# whitherbone.net
KiCad netlist of a schematic drawn in EAGLE
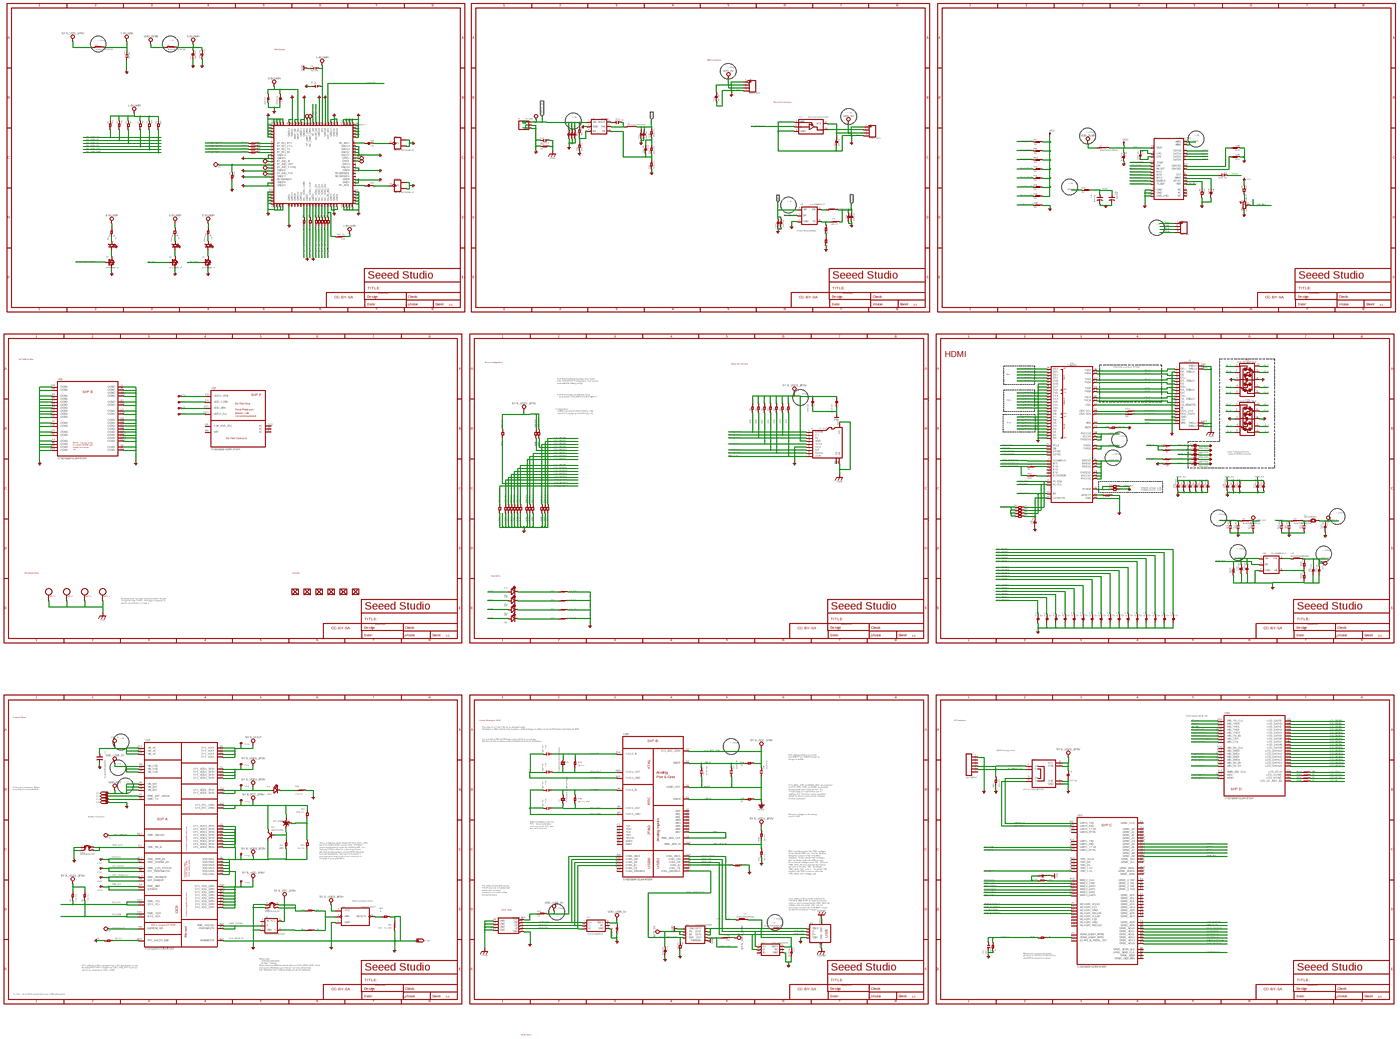
[diagram p0: schematic, sheet 1, overview]
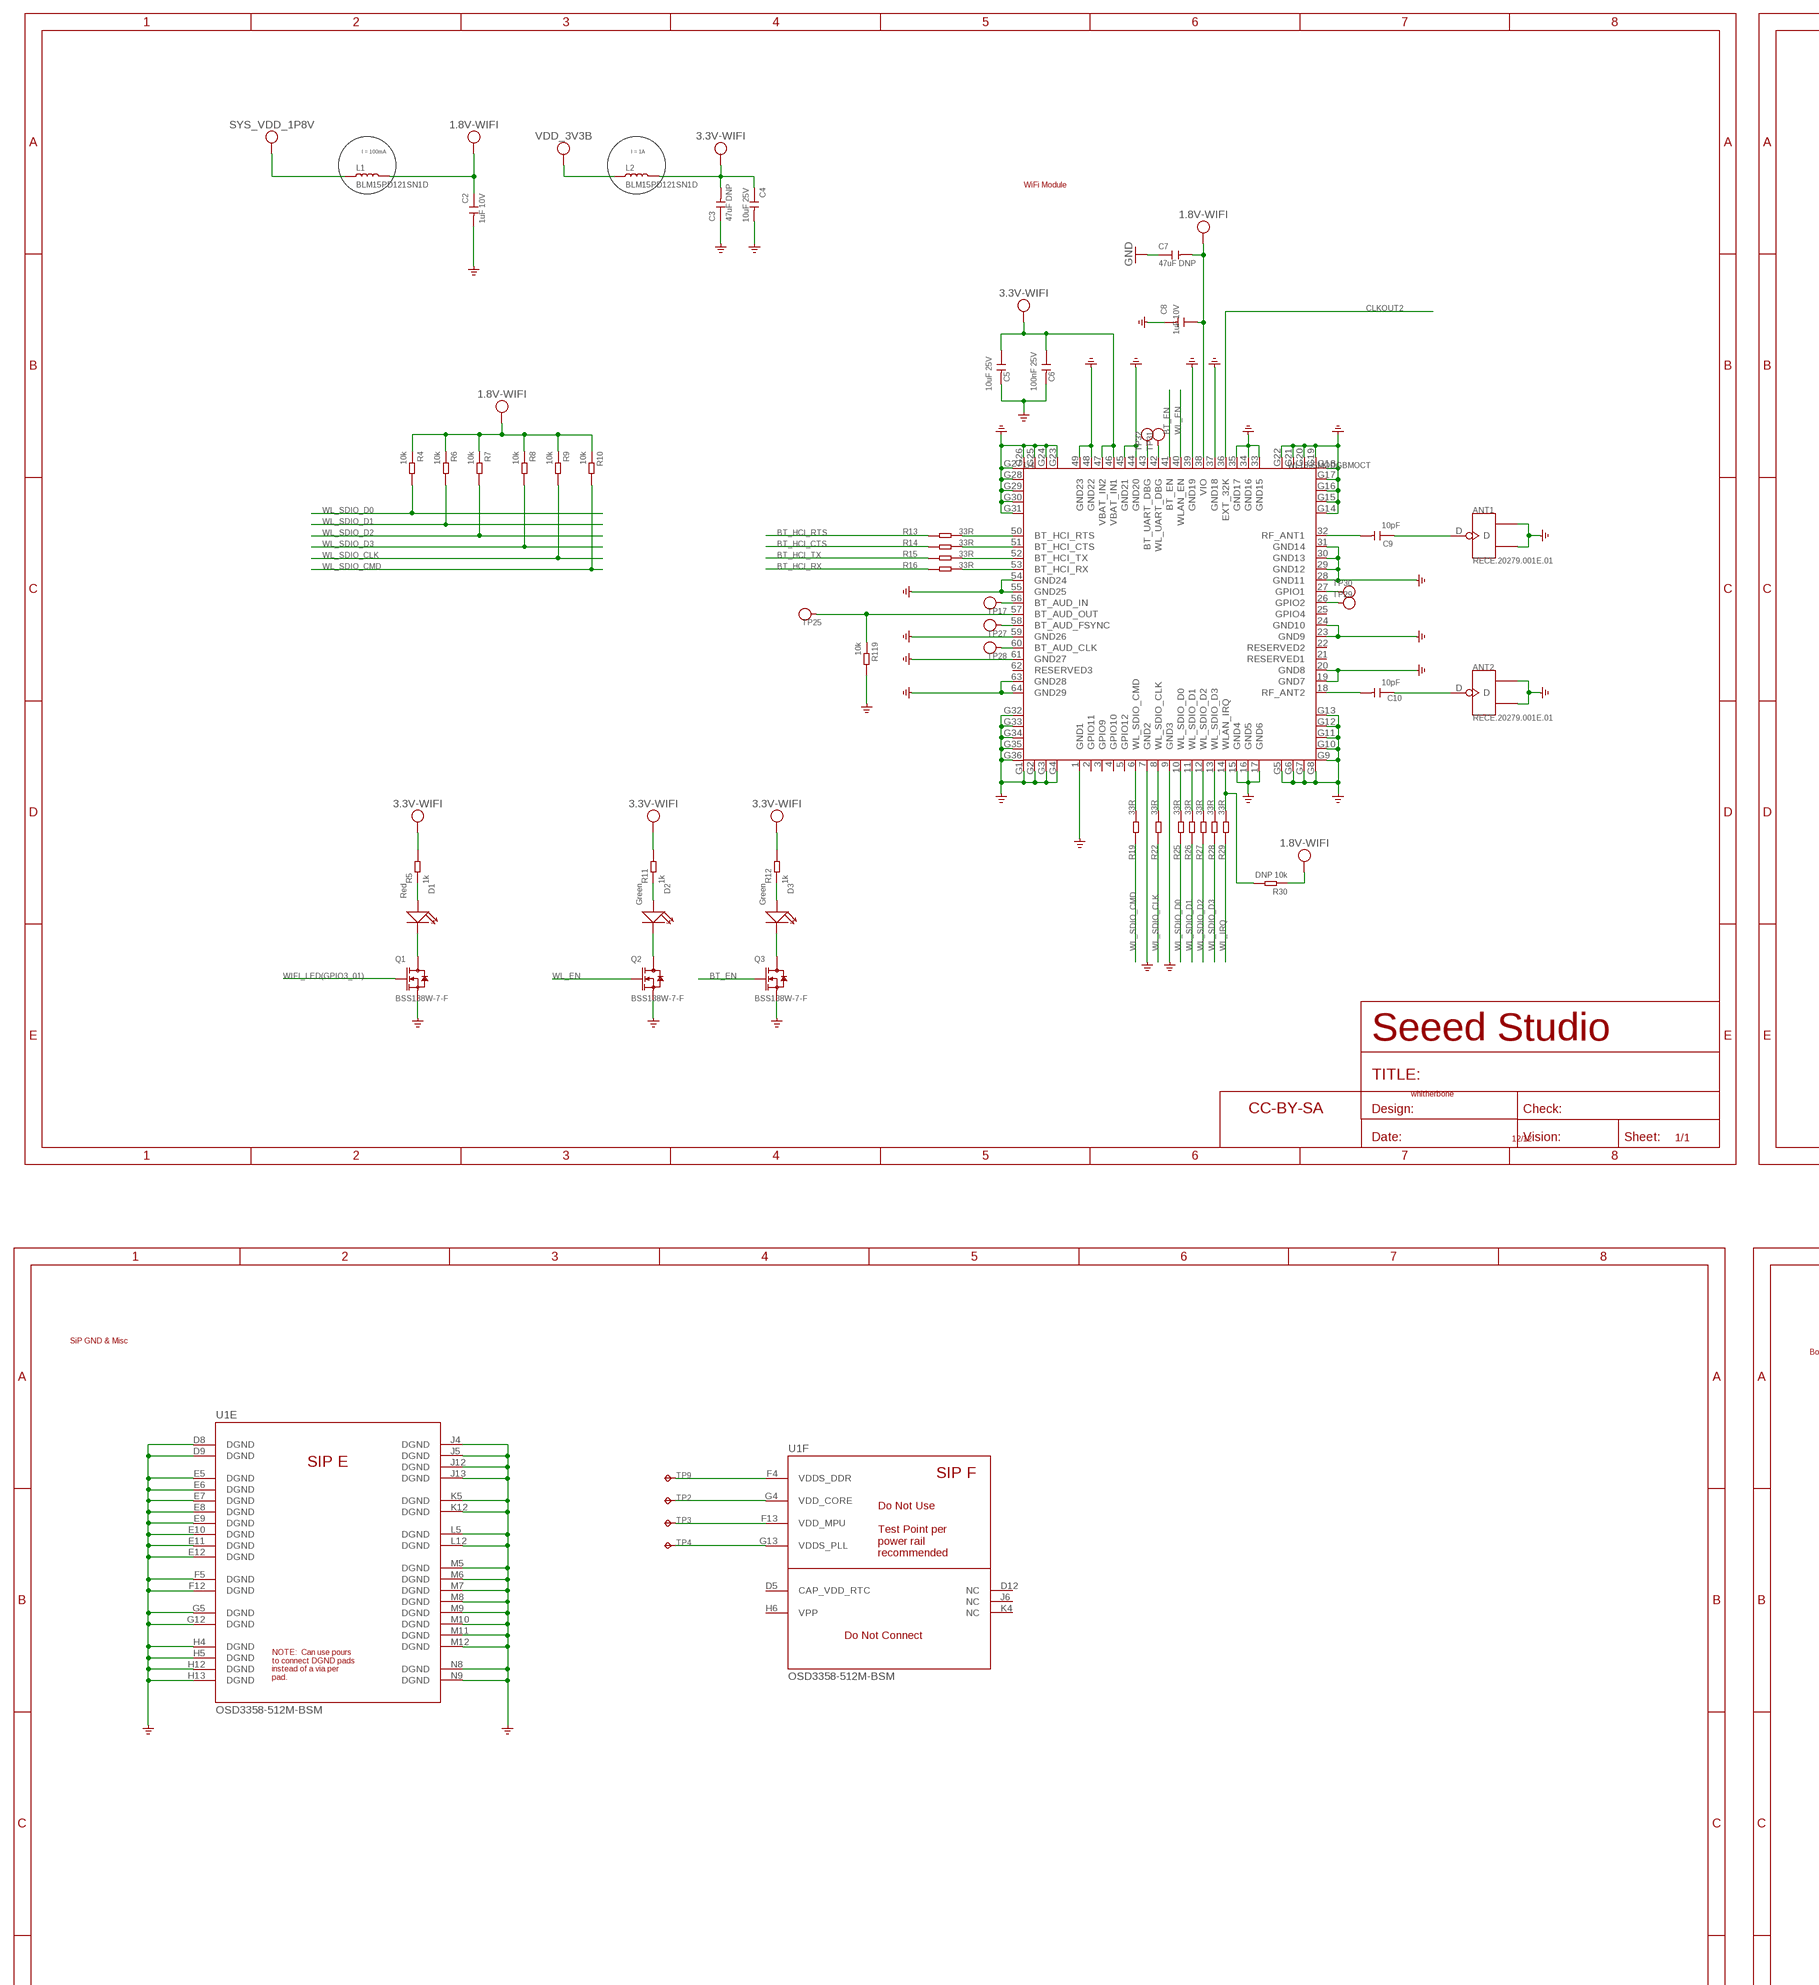
[diagram p1: schematic, sheet 1, part 1 of 8]
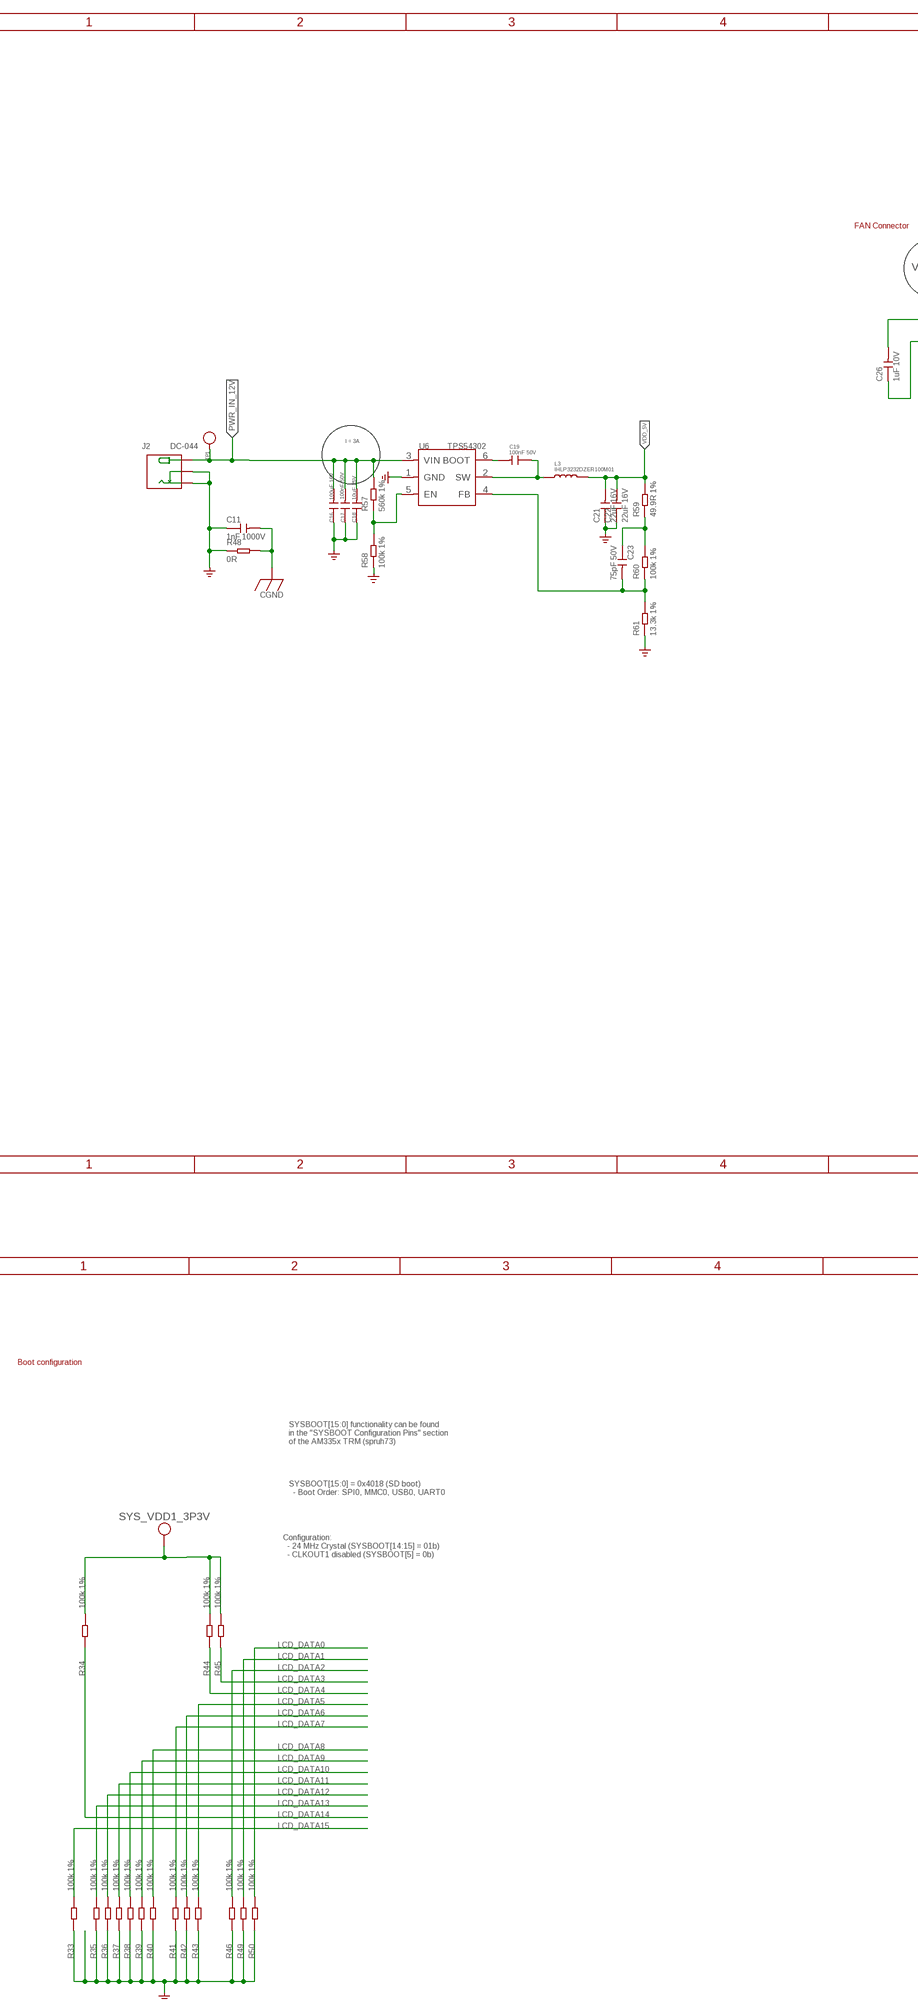
[diagram p2: schematic, sheet 1, part 2 of 8]
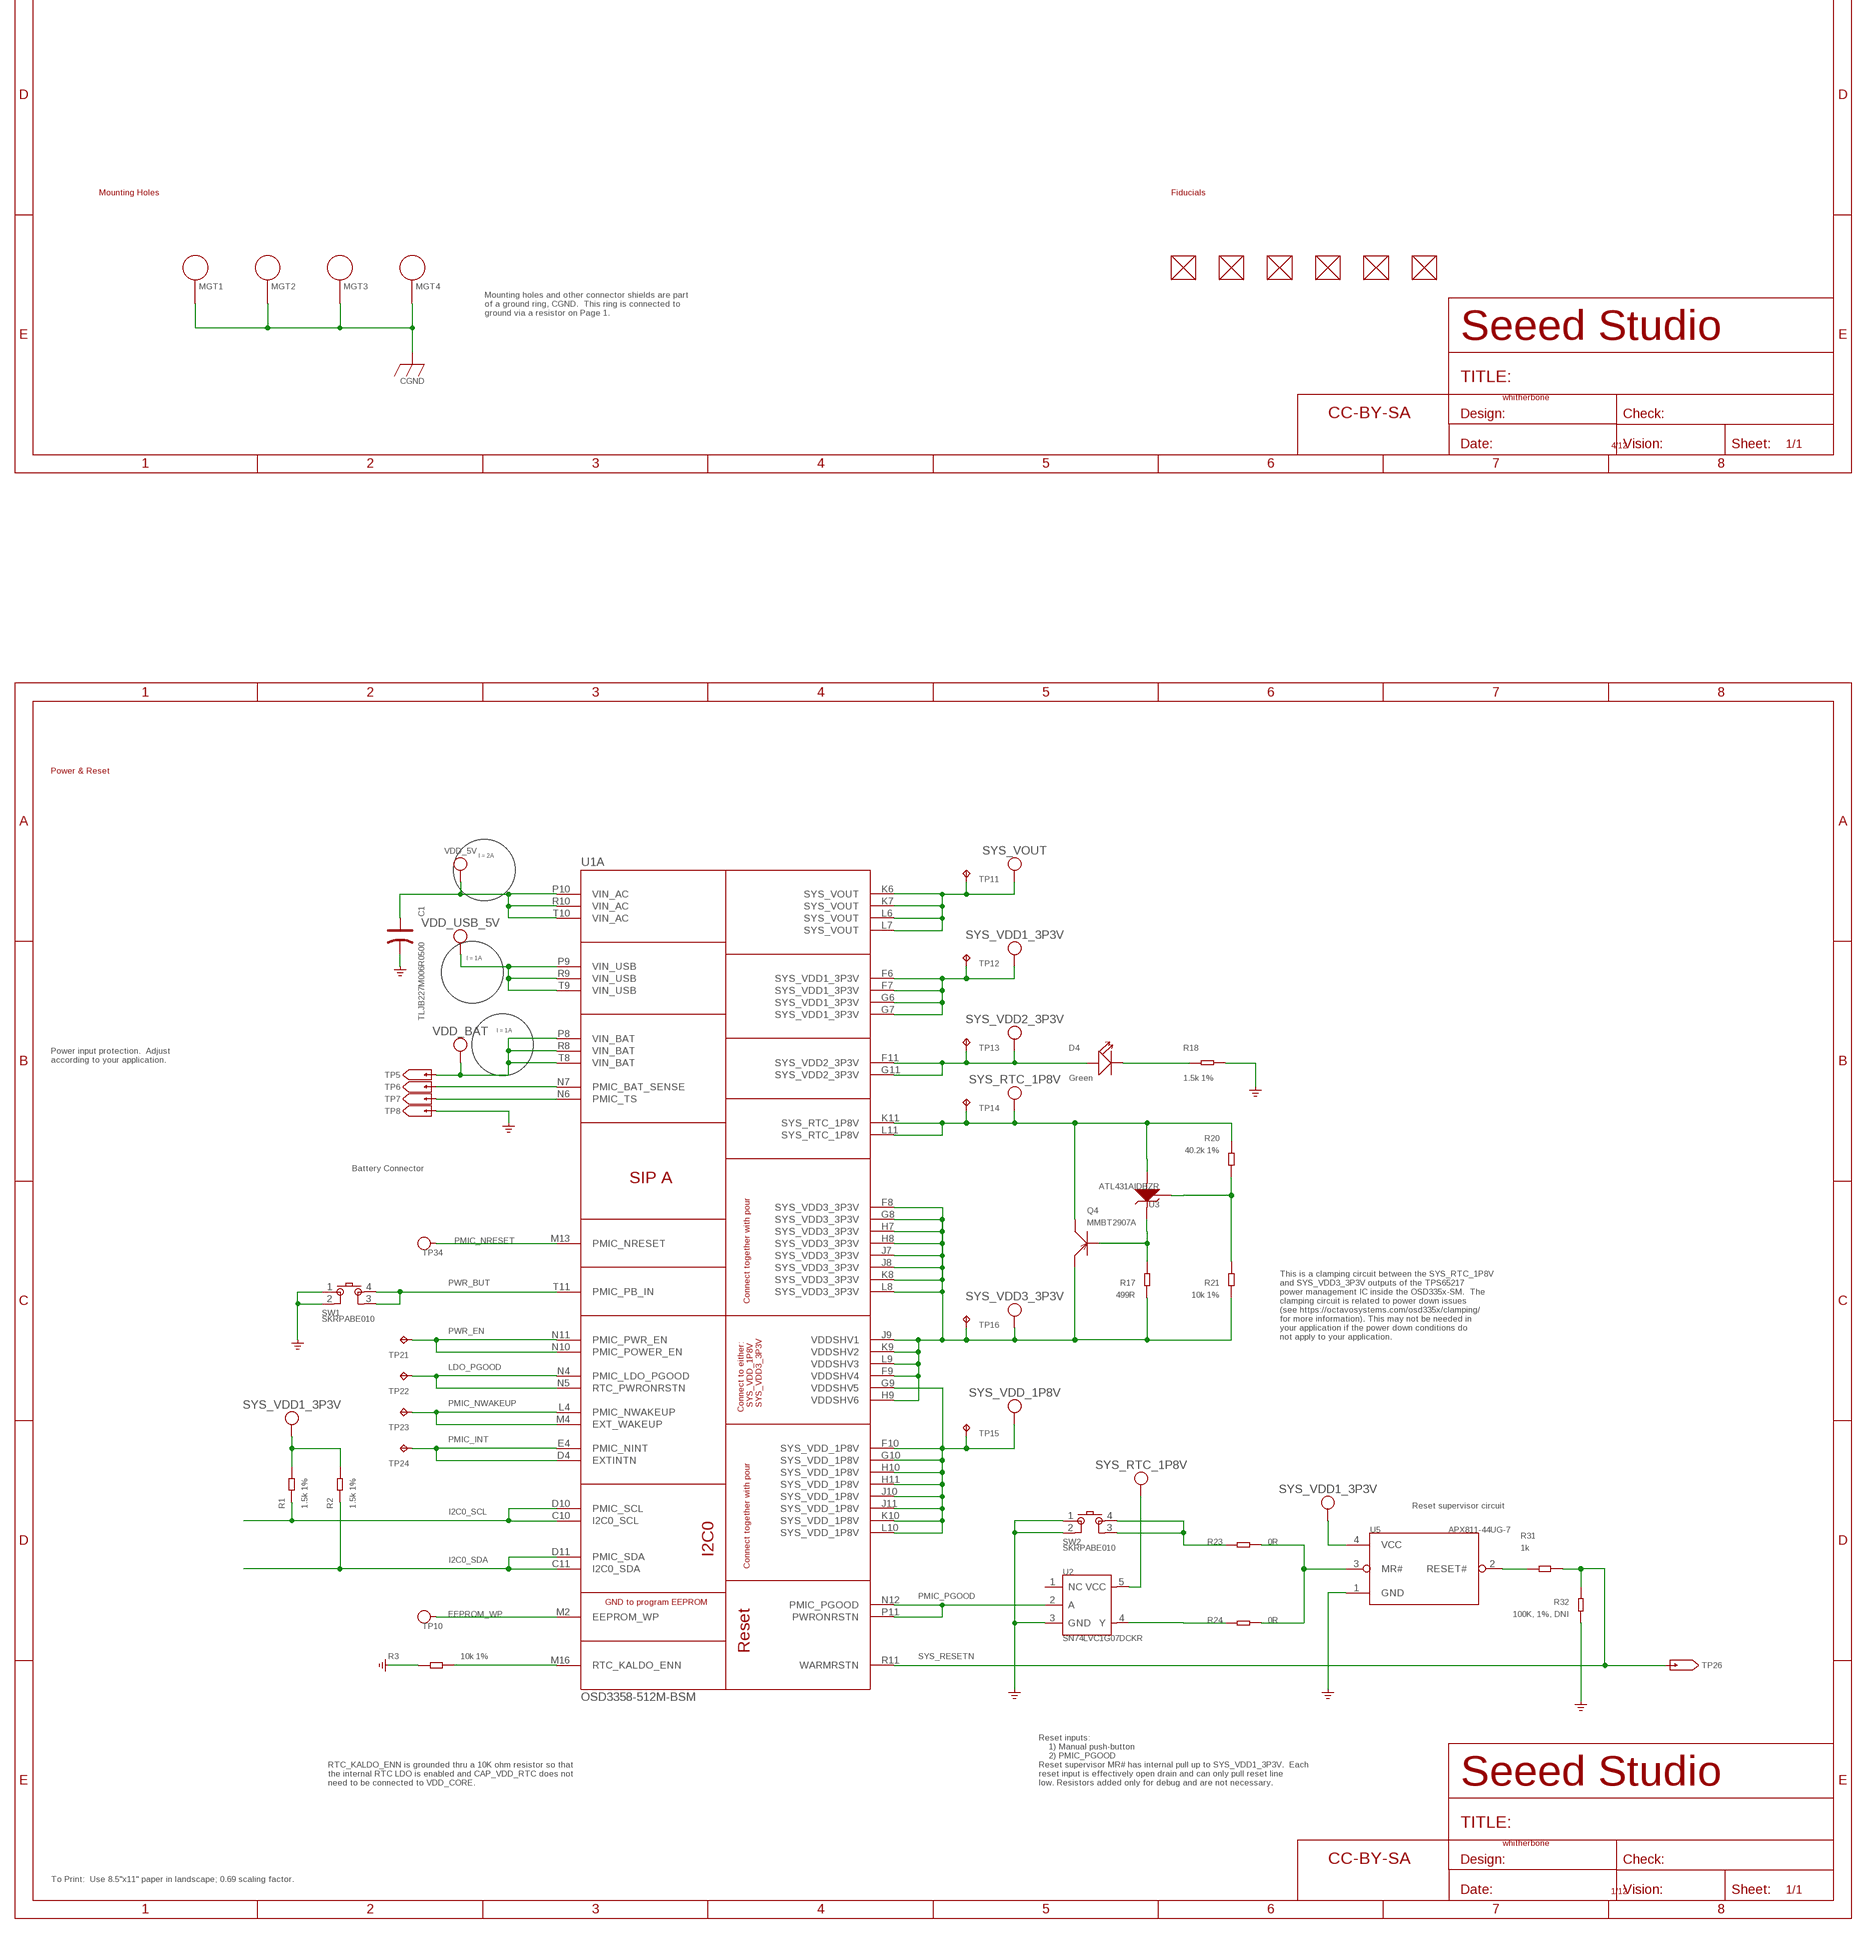
[diagram p3: schematic, sheet 1, part 3 of 8]
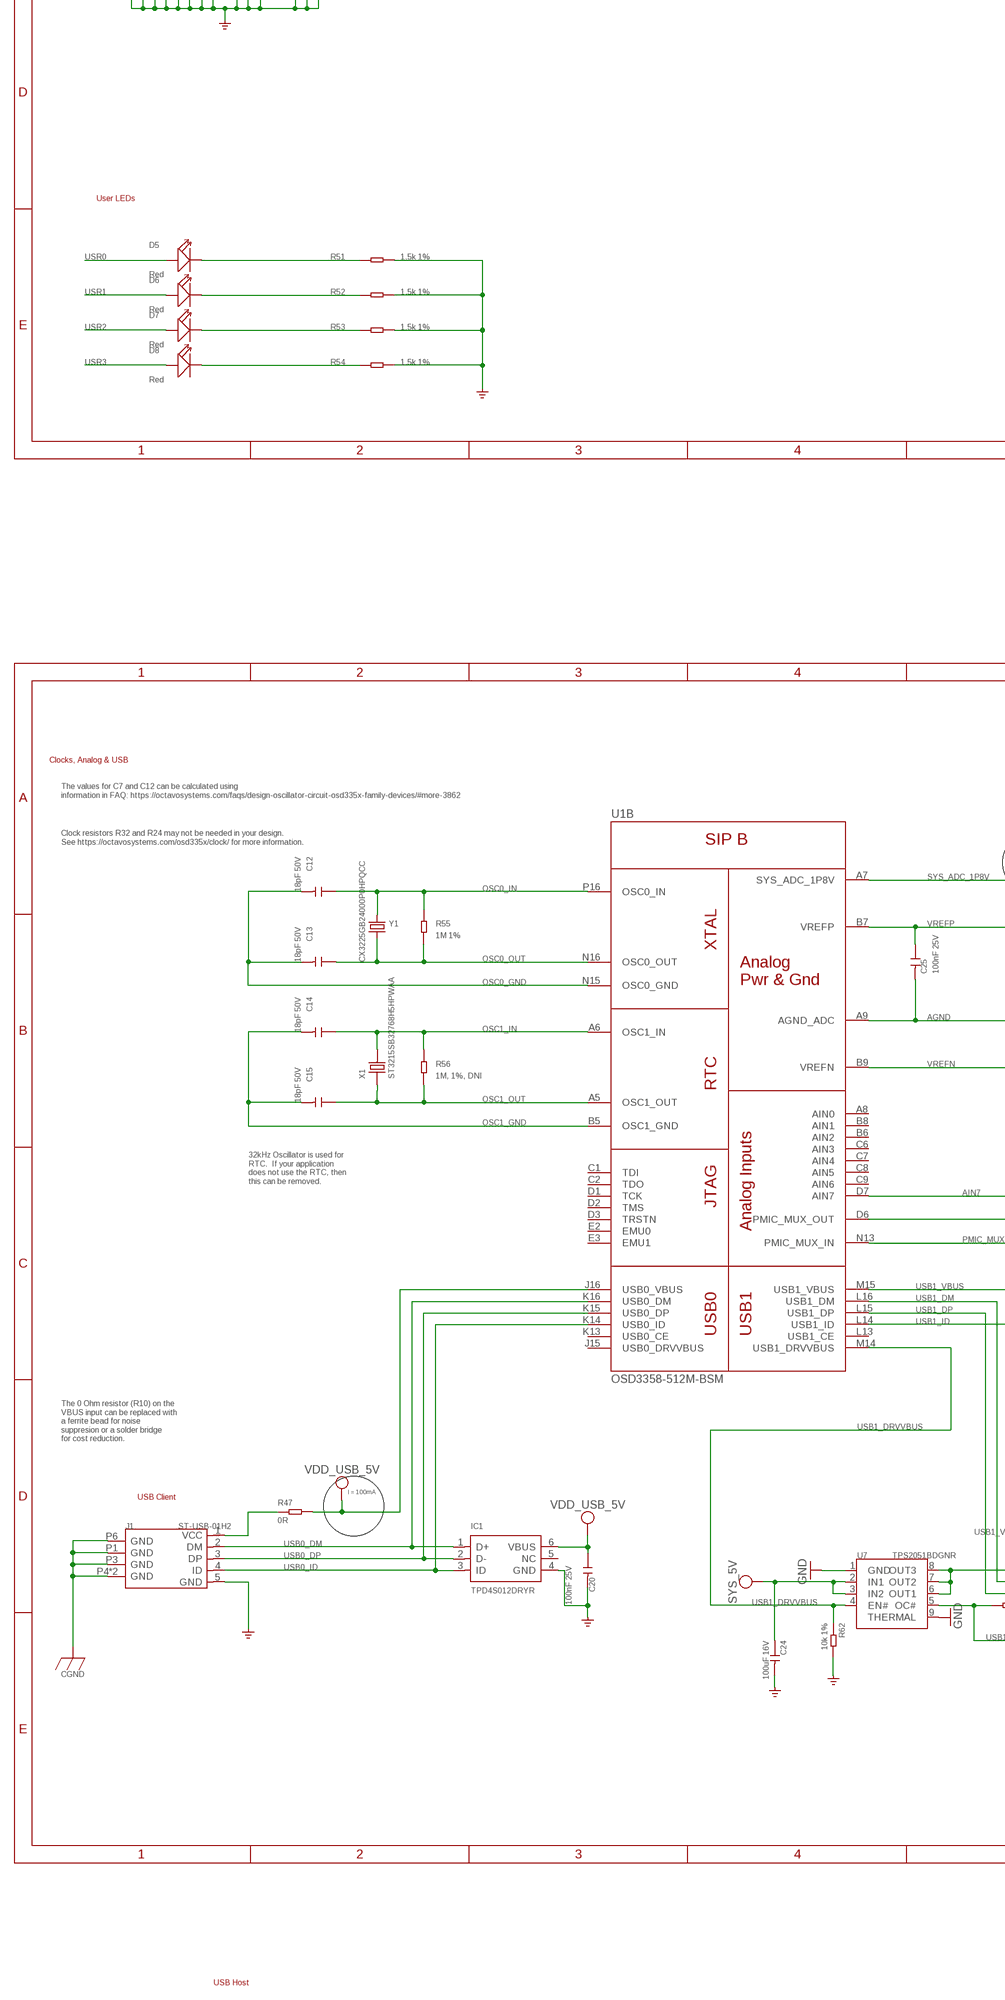
[diagram p4: schematic, sheet 1, part 4 of 8]
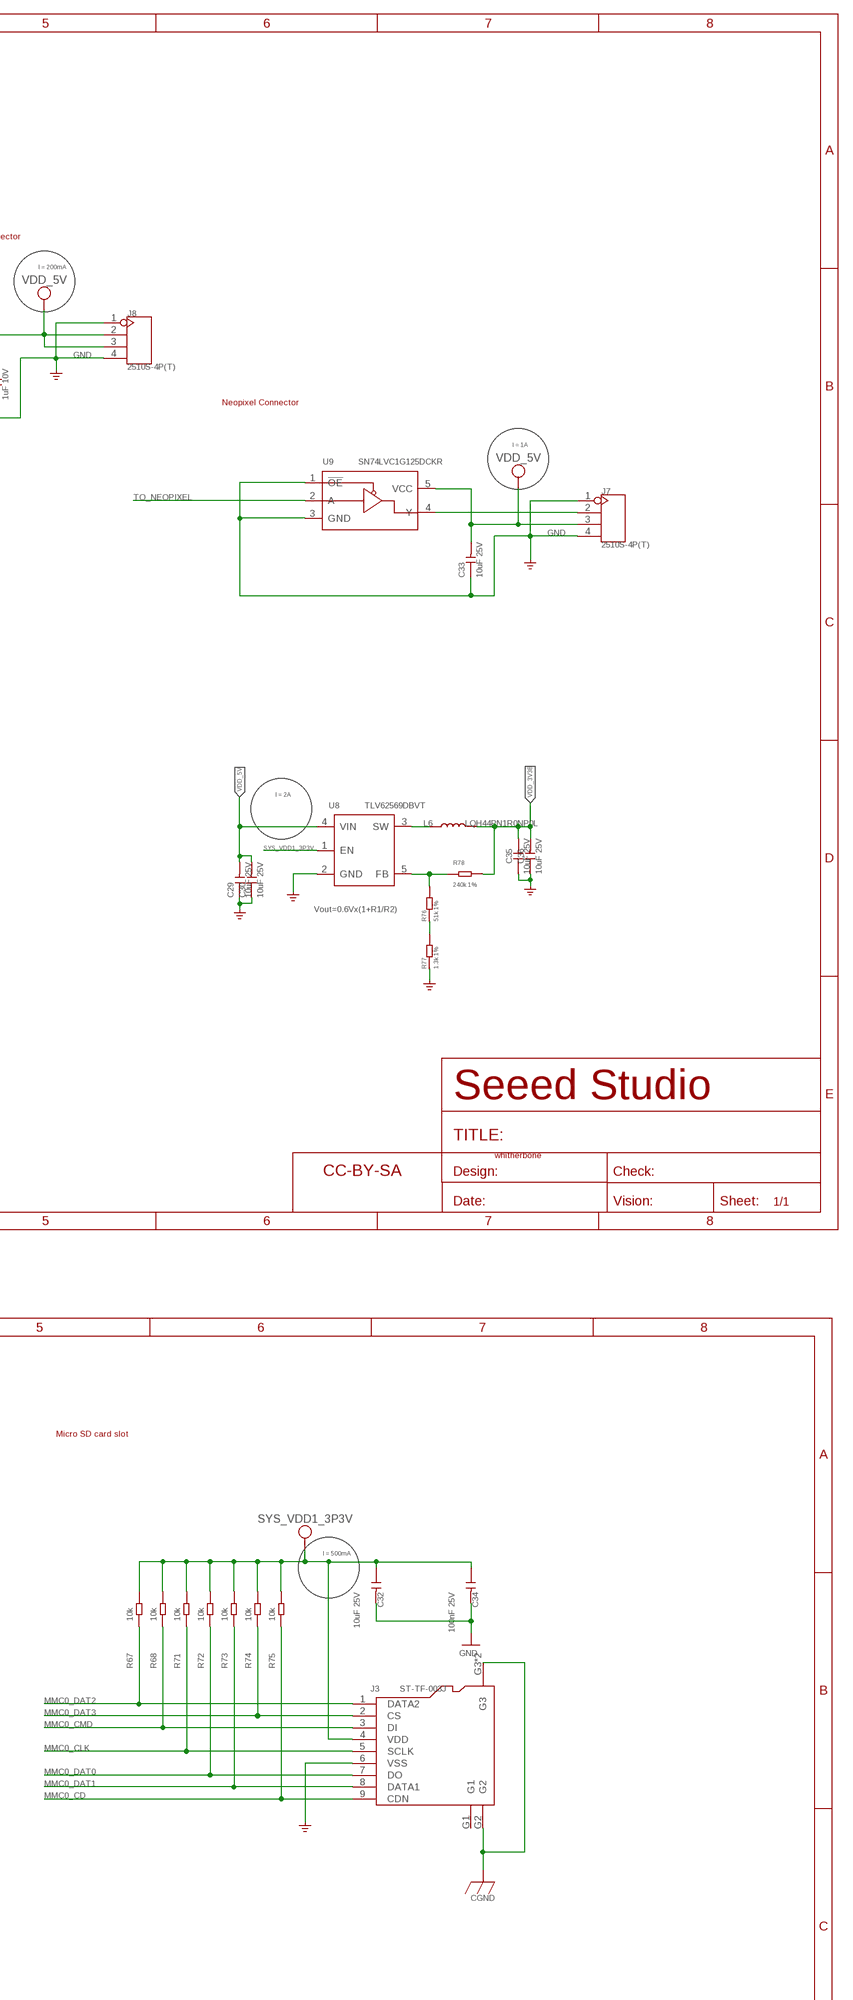
[diagram p5: schematic, sheet 1, part 5 of 8]
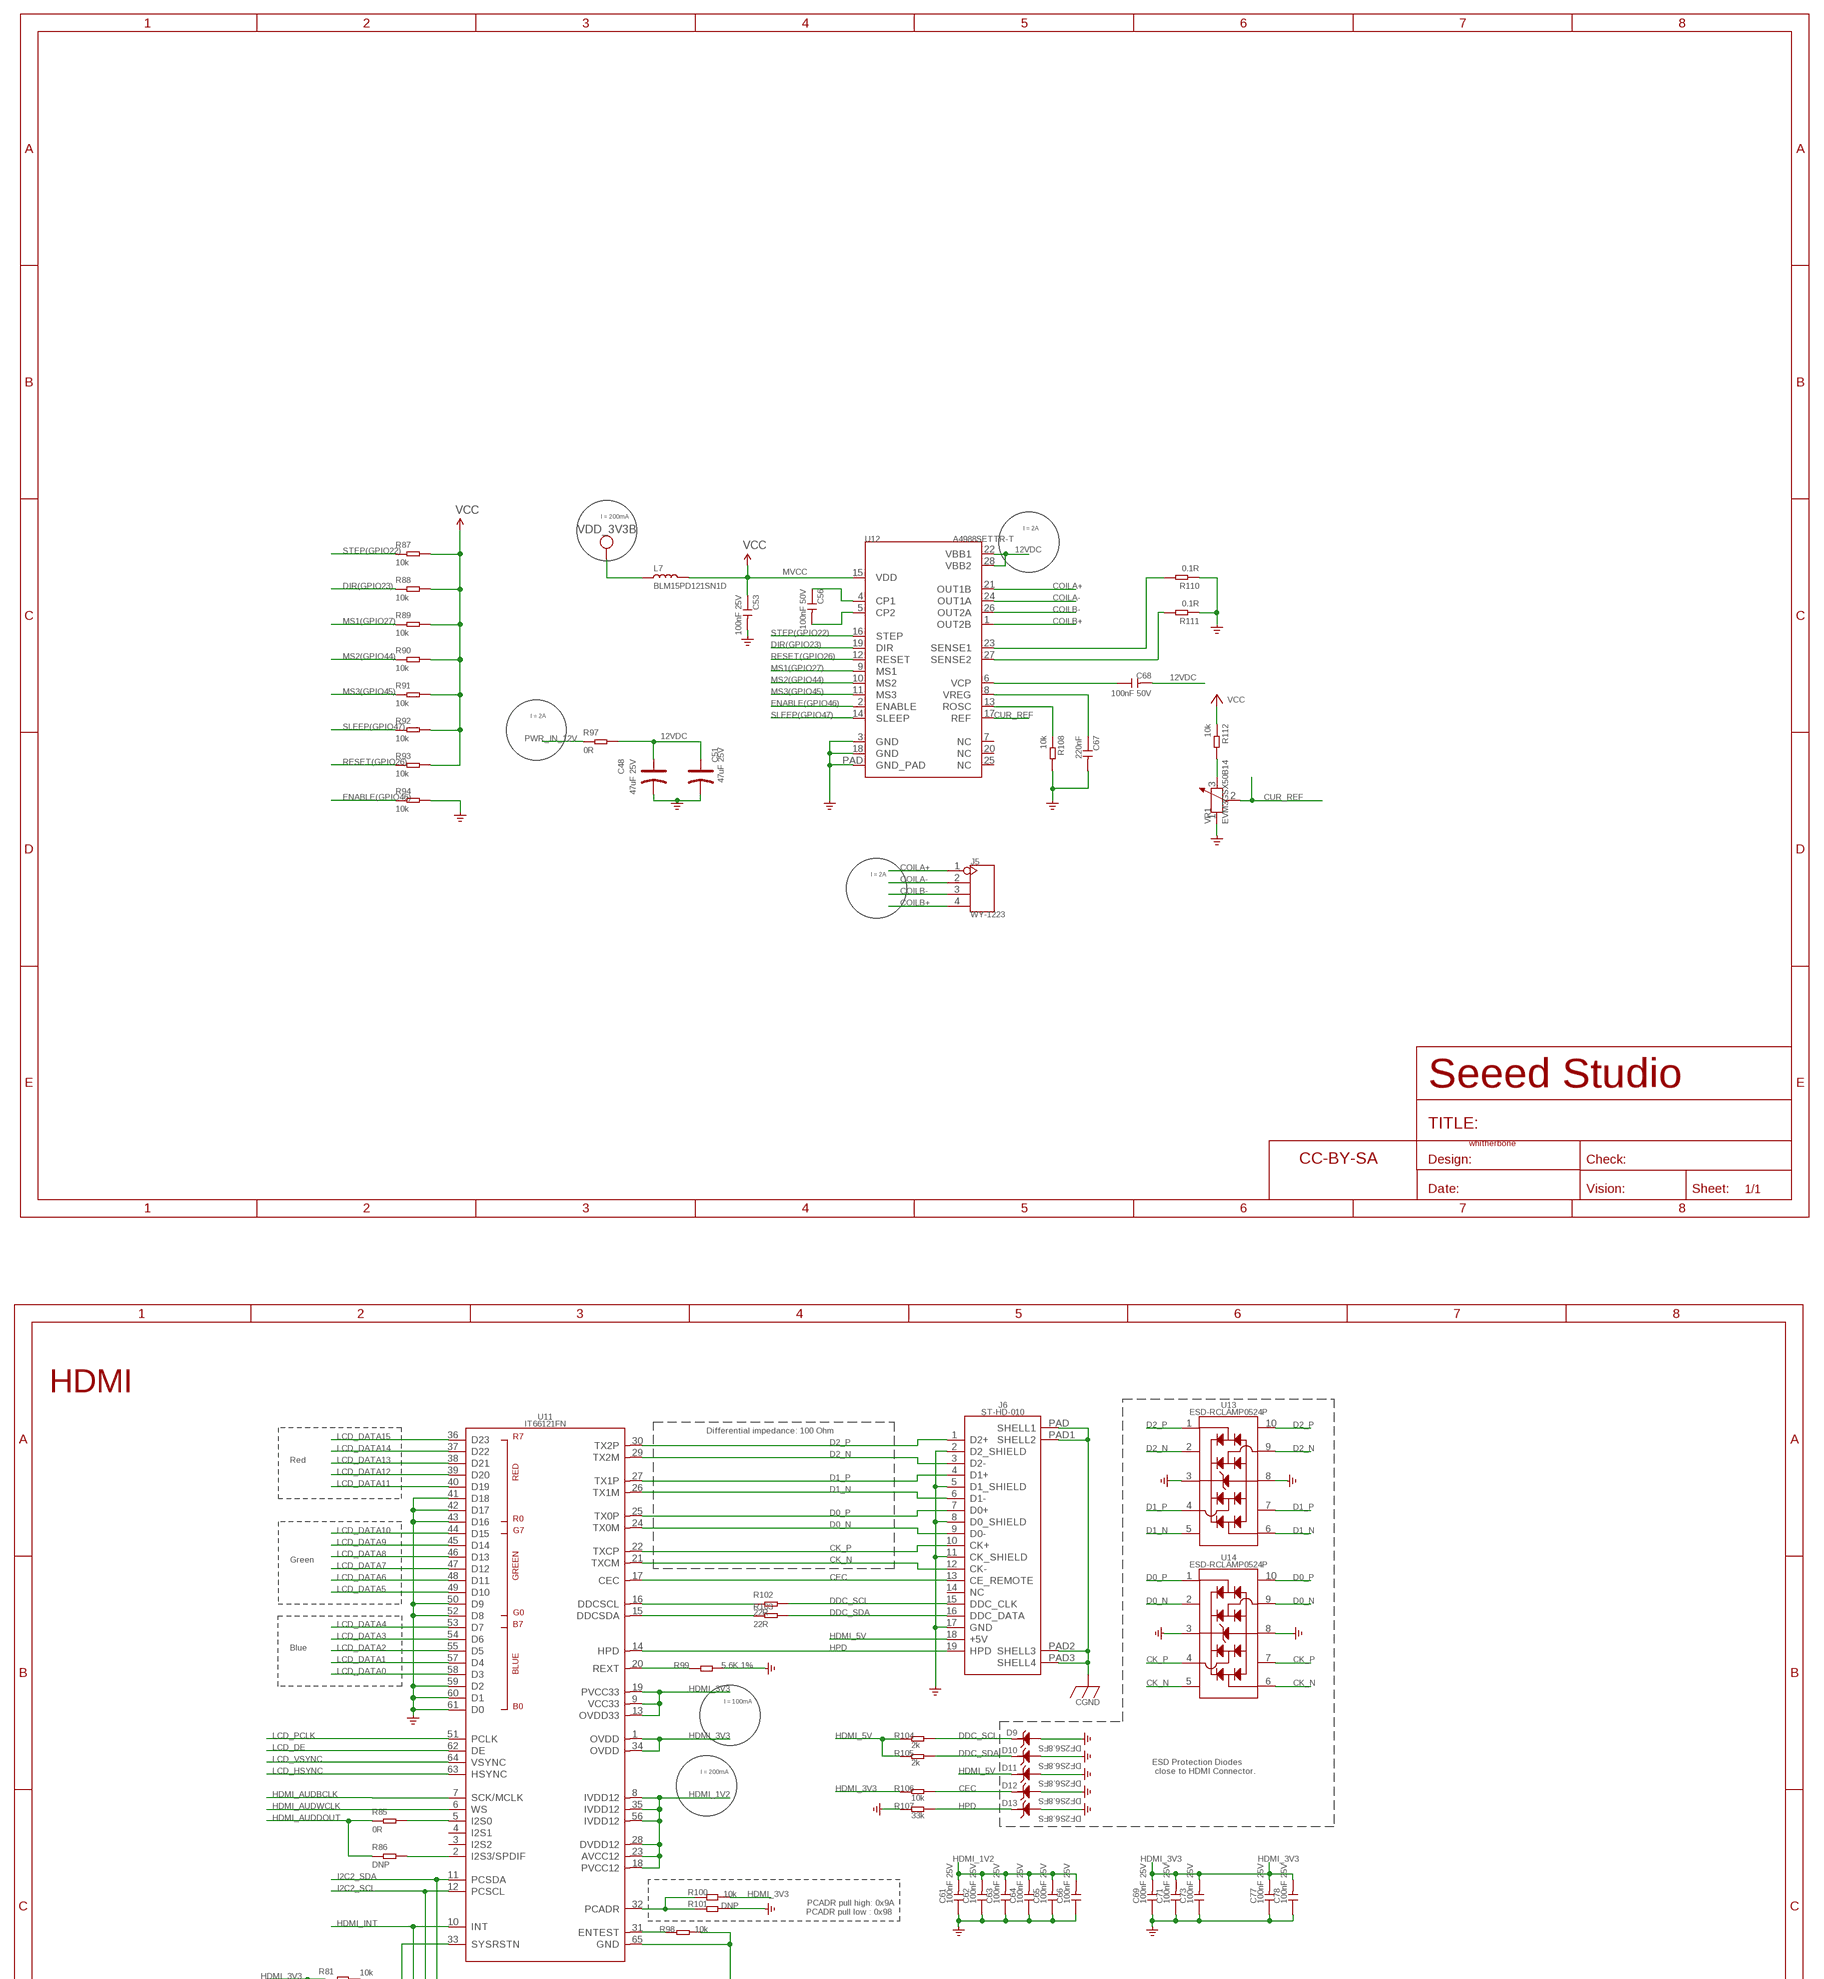
[diagram p6: schematic, sheet 1, part 6 of 8]
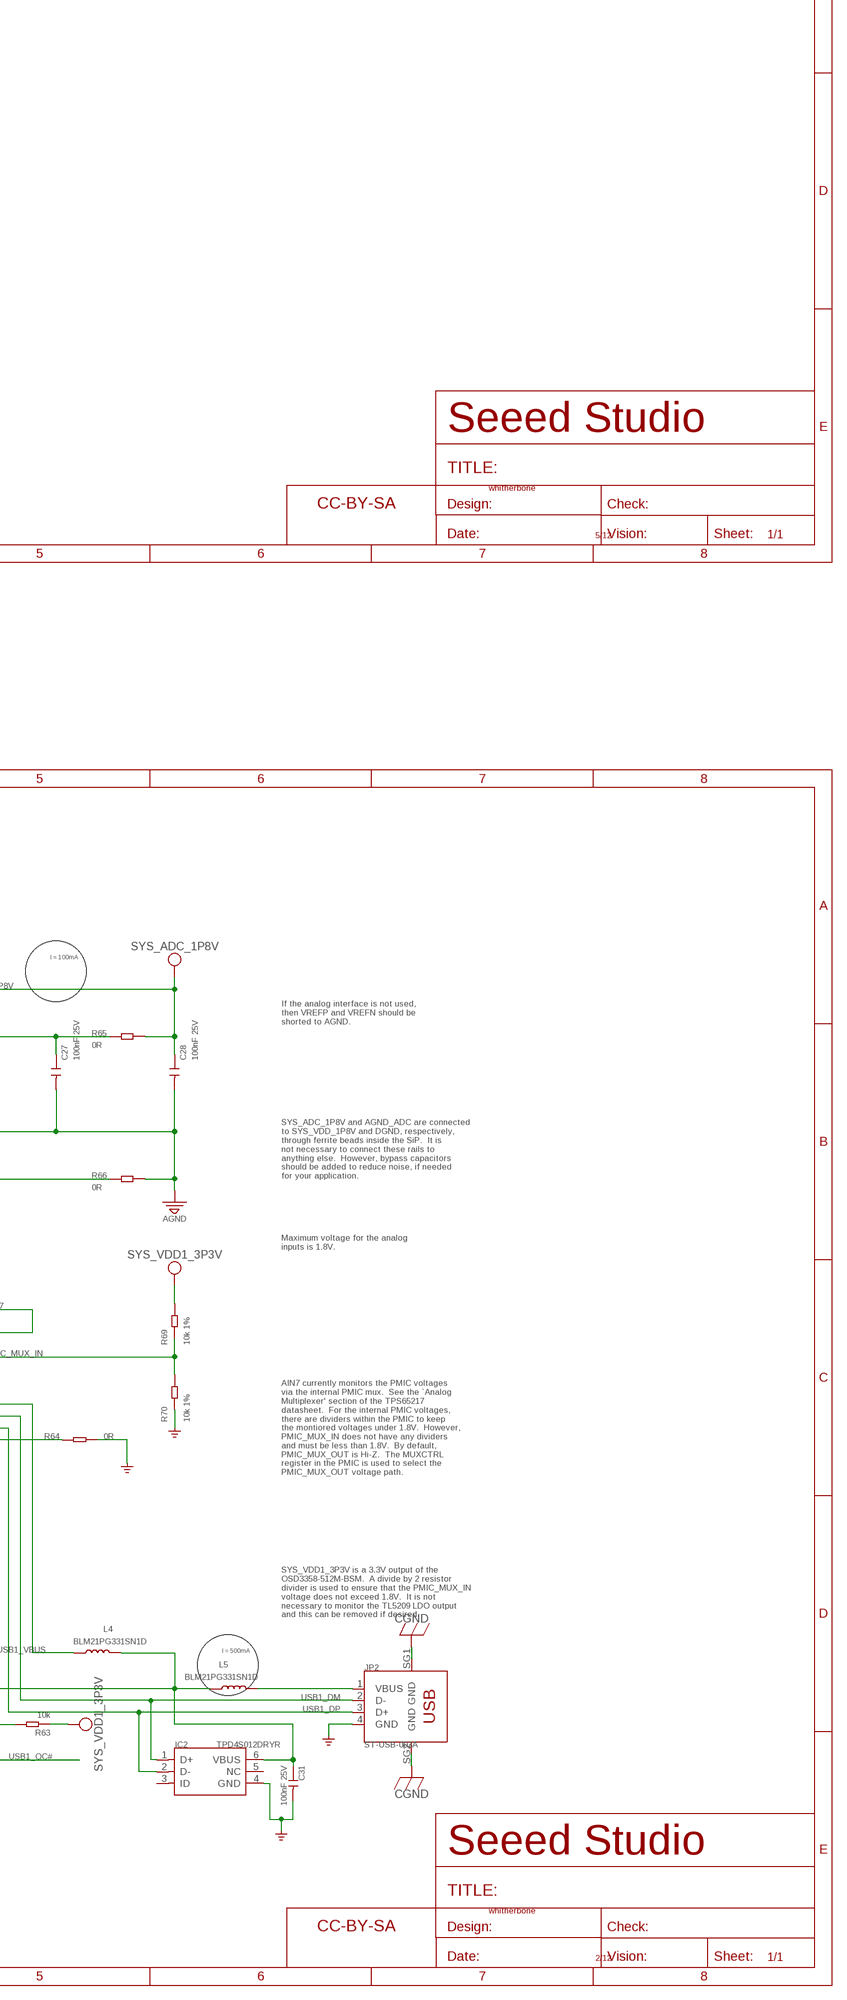
[diagram p7: schematic, sheet 1, part 7 of 8]
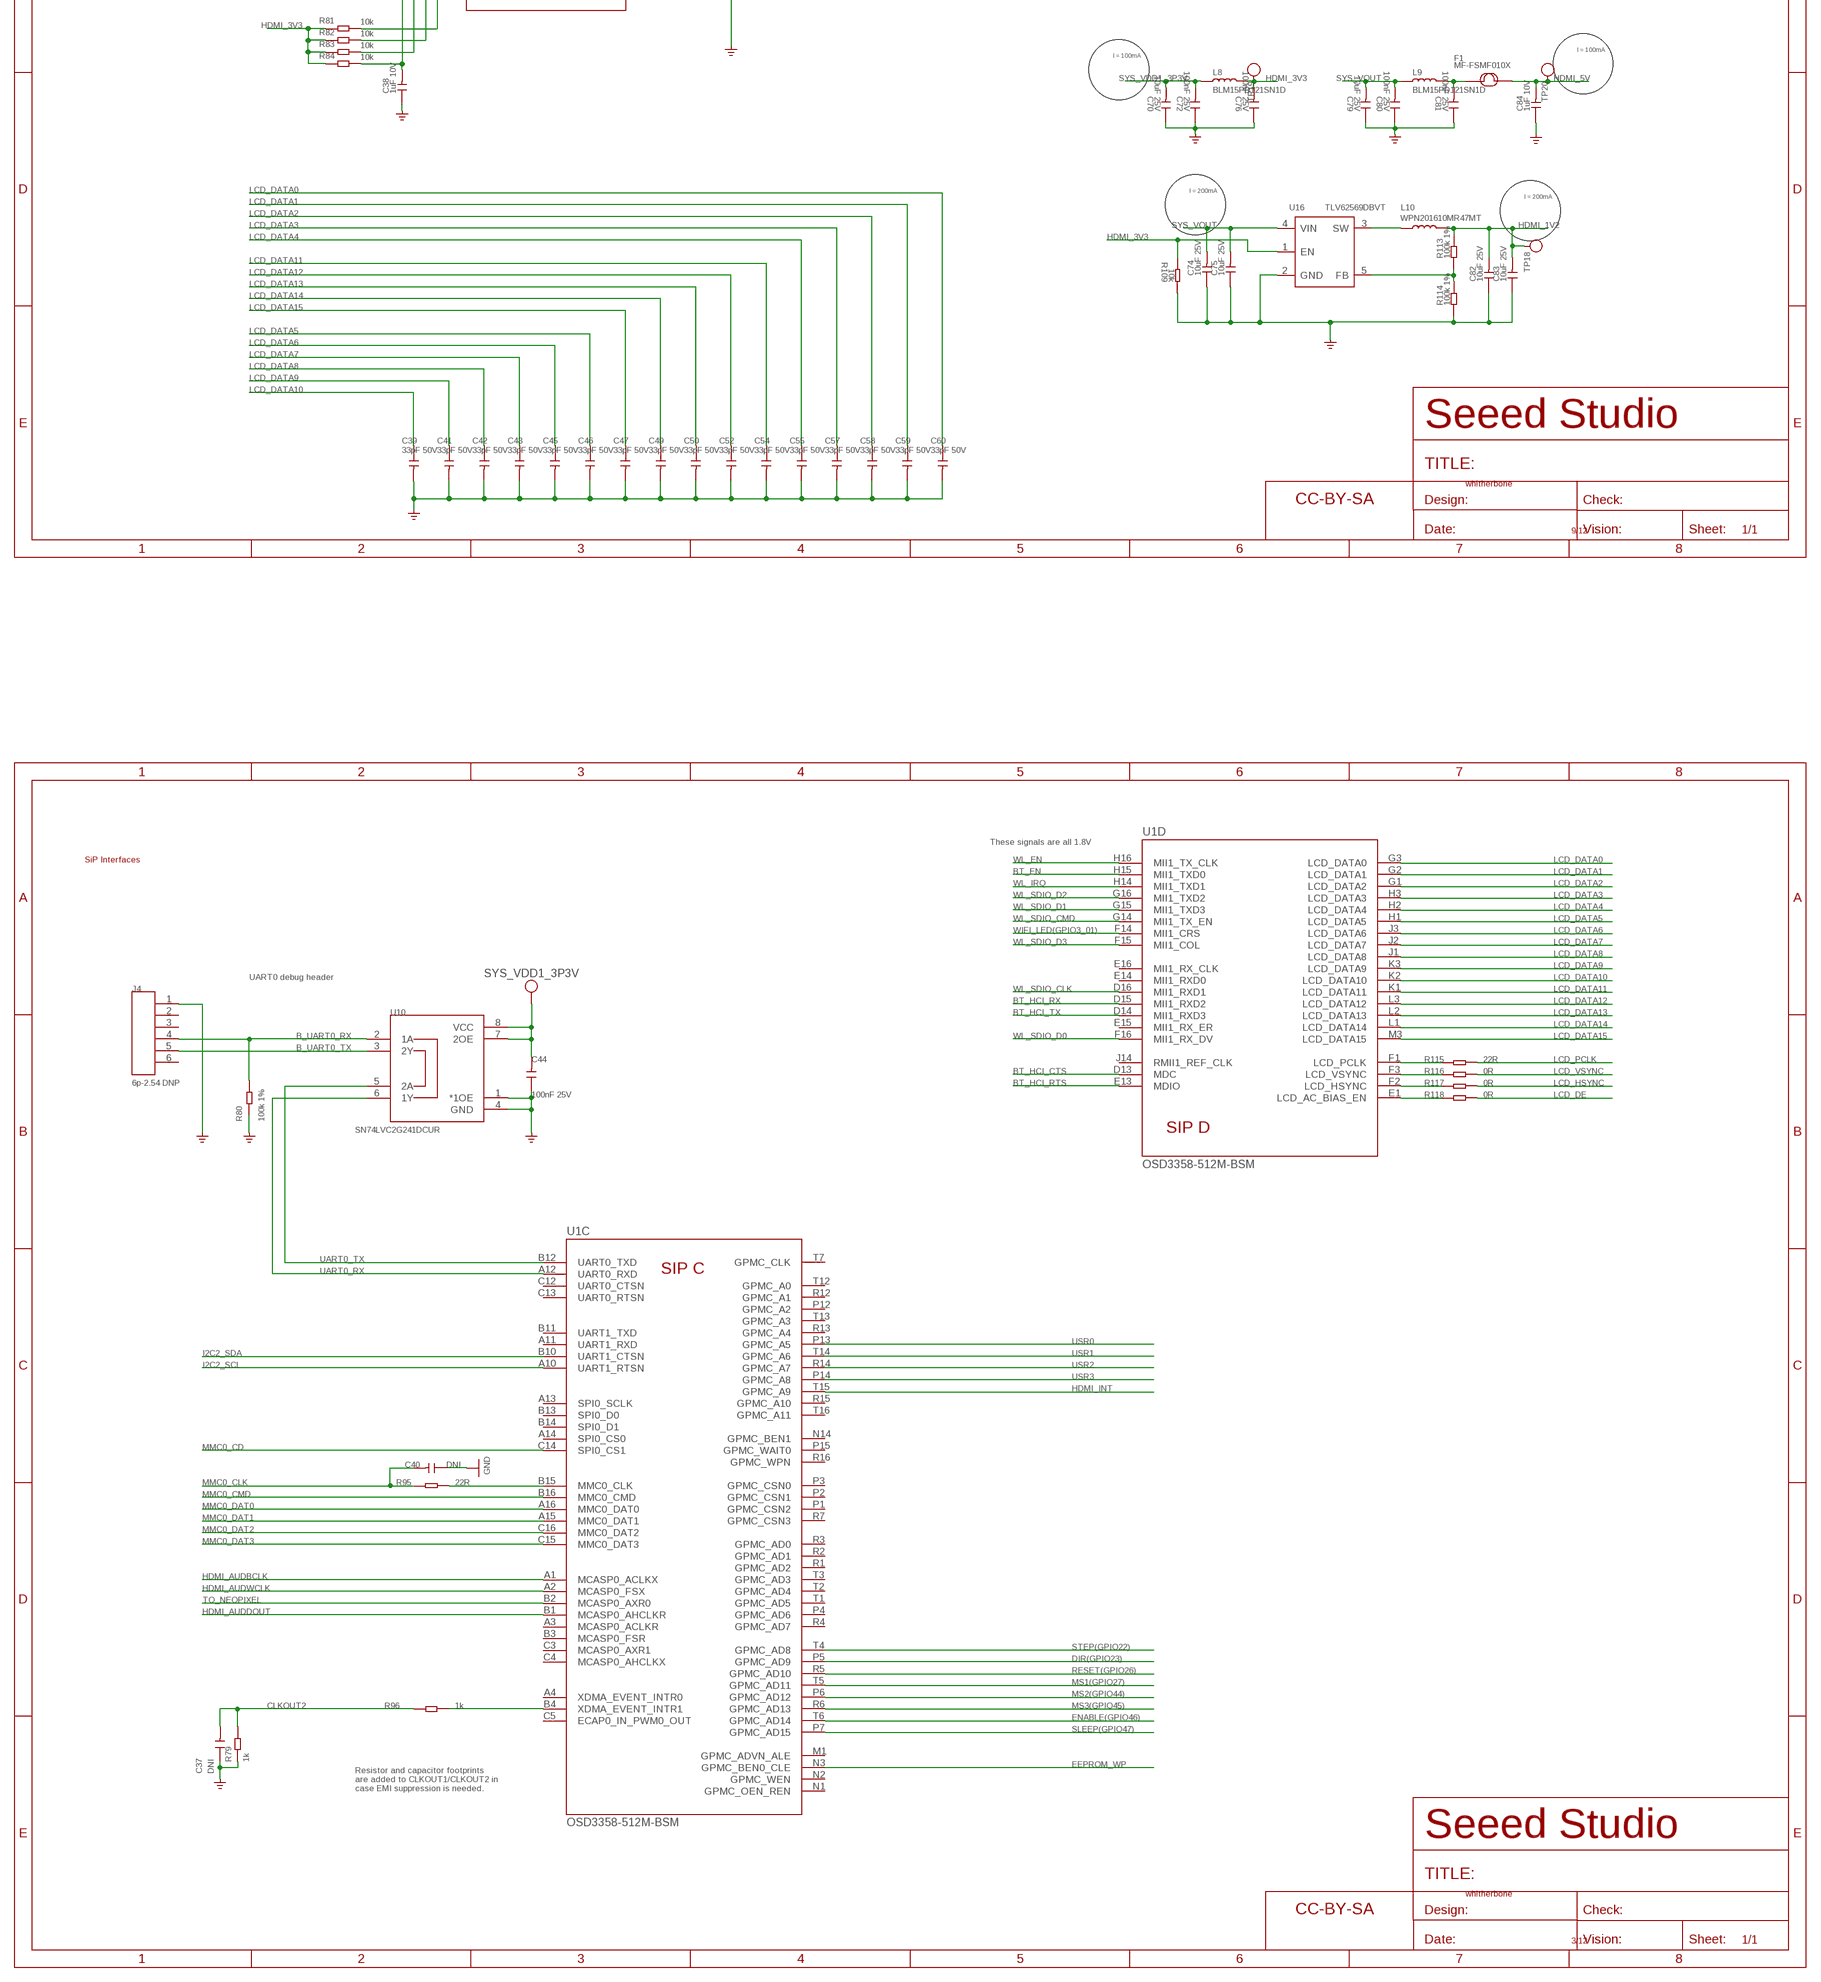
[diagram p8: schematic, sheet 1, part 8 of 8]

(export (version "E")
  (design (tool "Eeschema 10.0.6"))
  (components
    (comp (ref "ANT1")
      (value "RECE.20279.001E.01")
      (footprint "eagle-import:U-FL3P-SMD-2.6X2.6X1.0MM")
      (libsource (lib "eagle-import") (part "ANTENNA-U-FL-2.6X2.6"))
    )
    (comp (ref "ANT2")
      (value "RECE.20279.001E.01")
      (footprint "eagle-import:U-FL3P-SMD-2.6X2.6X1.0MM")
      (libsource (lib "eagle-import") (part "ANTENNA-U-FL-2.6X2.6"))
    )
    (comp (ref "C1")
      (value "TLJB227M006R0500")
      (footprint "eagle-import:AVX-B")
      (libsource (lib "eagle-import") (part "CAP-POLAR-AVX-B"))
    )
    (comp (ref "C2")
      (value "1uF 10V")
      (footprint "eagle-import:C0402")
      (libsource (lib "eagle-import") (part "CAP-0402"))
    )
    (comp (ref "C3")
      (value "47uF DNP")
      (footprint "eagle-import:C1206")
      (libsource (lib "eagle-import") (part "CAP-1206"))
    )
    (comp (ref "C4")
      (value "10uF 25V")
      (footprint "eagle-import:C0805")
      (libsource (lib "eagle-import") (part "CAP-0805"))
    )
    (comp (ref "C5")
      (value "10uF 25V")
      (footprint "eagle-import:C0805")
      (libsource (lib "eagle-import") (part "CAP-0805"))
    )
    (comp (ref "C6")
      (value "100nF 25V")
      (footprint "eagle-import:C0402")
      (libsource (lib "eagle-import") (part "CAP-0402"))
    )
    (comp (ref "C7")
      (value "47uF DNP")
      (footprint "eagle-import:C1206")
      (libsource (lib "eagle-import") (part "CAP-1206"))
    )
    (comp (ref "C8")
      (value "1uF 10V")
      (footprint "eagle-import:C0402")
      (libsource (lib "eagle-import") (part "CAP-0402"))
    )
    (comp (ref "C9")
      (value "10pF")
      (footprint "eagle-import:C0402")
      (libsource (lib "eagle-import") (part "CAP-0402"))
    )
    (comp (ref "C10")
      (value "10pF")
      (footprint "eagle-import:C0402")
      (libsource (lib "eagle-import") (part "CAP-0402"))
    )
    (comp (ref "C11")
      (value "1nF 1000V")
      (footprint "eagle-import:C1206")
      (libsource (lib "eagle-import") (part "CAP-1206"))
    )
    (comp (ref "C12")
      (value "18pF 50V")
      (footprint "eagle-import:C0402")
      (libsource (lib "eagle-import") (part "CAP-0402"))
    )
    (comp (ref "C13")
      (value "18pF 50V")
      (footprint "eagle-import:C0402")
      (libsource (lib "eagle-import") (part "CAP-0402"))
    )
    (comp (ref "C14")
      (value "18pF 50V")
      (footprint "eagle-import:C0402")
      (libsource (lib "eagle-import") (part "CAP-0402"))
    )
    (comp (ref "C15")
      (value "18pF 50V")
      (footprint "eagle-import:C0402")
      (libsource (lib "eagle-import") (part "CAP-0402"))
    )
    (comp (ref "C16")
      (value "100uF 16V")
      (footprint "eagle-import:C1210")
      (libsource (lib "eagle-import") (part "CAP-1210"))
    )
    (comp (ref "C17")
      (value "100nF 50V")
      (footprint "eagle-import:C0805")
      (libsource (lib "eagle-import") (part "CAP-0805"))
    )
    (comp (ref "C18")
      (value "10uF 25V")
      (footprint "eagle-import:C0805")
      (libsource (lib "eagle-import") (part "CAP-0805"))
    )
    (comp (ref "C19")
      (value "100nF 50V")
      (footprint "eagle-import:C0805")
      (libsource (lib "eagle-import") (part "CAP-0805"))
    )
    (comp (ref "C20")
      (value "100nF 25V")
      (footprint "eagle-import:C0402")
      (libsource (lib "eagle-import") (part "CAP-0402"))
    )
    (comp (ref "C21")
      (value "22uF 16V")
      (footprint "eagle-import:C1206")
      (libsource (lib "eagle-import") (part "CAP-1206"))
    )
    (comp (ref "C22")
      (value "22uF 16V")
      (footprint "eagle-import:C1206")
      (libsource (lib "eagle-import") (part "CAP-1206"))
    )
    (comp (ref "C23")
      (value "75pF 50V")
      (footprint "eagle-import:C0402")
      (libsource (lib "eagle-import") (part "CAP-0402"))
    )
    (comp (ref "C24")
      (value "100uF 16V")
      (footprint "eagle-import:C1210")
      (libsource (lib "eagle-import") (part "CAP-1210"))
    )
    (comp (ref "C25")
      (value "100nF 25V")
      (footprint "eagle-import:C0402")
      (libsource (lib "eagle-import") (part "CAP-0402"))
    )
    (comp (ref "C26")
      (value "1uF 10V")
      (footprint "eagle-import:C0402")
      (libsource (lib "eagle-import") (part "CAP-0402"))
    )
    (comp (ref "C27")
      (value "100nF 25V")
      (footprint "eagle-import:C0402")
      (libsource (lib "eagle-import") (part "CAP-0402"))
    )
    (comp (ref "C28")
      (value "100nF 25V")
      (footprint "eagle-import:C0402")
      (libsource (lib "eagle-import") (part "CAP-0402"))
    )
    (comp (ref "C29")
      (value "10uF 25V")
      (footprint "eagle-import:C0805")
      (libsource (lib "eagle-import") (part "CAP-0805"))
    )
    (comp (ref "C30")
      (value "10uF 25V")
      (footprint "eagle-import:C0805")
      (libsource (lib "eagle-import") (part "CAP-0805"))
    )
    (comp (ref "C31")
      (value "100nF 25V")
      (footprint "eagle-import:C0402")
      (libsource (lib "eagle-import") (part "CAP-0402"))
    )
    (comp (ref "C32")
      (value "10uF 25V")
      (footprint "eagle-import:C0805")
      (libsource (lib "eagle-import") (part "CAP-0805"))
    )
    (comp (ref "C33")
      (value "10uF 25V")
      (footprint "eagle-import:C0805")
      (libsource (lib "eagle-import") (part "CAP-0805"))
    )
    (comp (ref "C34")
      (value "100nF 25V")
      (footprint "eagle-import:C0402")
      (libsource (lib "eagle-import") (part "CAP-0402"))
    )
    (comp (ref "C35")
      (value "10uF 25V")
      (footprint "eagle-import:C0805")
      (libsource (lib "eagle-import") (part "CAP-0805"))
    )
    (comp (ref "C36")
      (value "10uF 25V")
      (footprint "eagle-import:C0805")
      (libsource (lib "eagle-import") (part "CAP-0805"))
    )
    (comp (ref "C37")
      (value "DNI")
      (footprint "eagle-import:C0402")
      (libsource (lib "eagle-import") (part "CAP-0402"))
    )
    (comp (ref "C38")
      (value "1uF 10V")
      (footprint "eagle-import:C0402")
      (libsource (lib "eagle-import") (part "CAP-0402"))
    )
    (comp (ref "C39")
      (value "33pF 50V")
      (footprint "eagle-import:C0402")
      (libsource (lib "eagle-import") (part "CAP-0402"))
    )
    (comp (ref "C40")
      (value "DNI")
      (footprint "eagle-import:C0402")
      (libsource (lib "eagle-import") (part "CAP-0402"))
    )
    (comp (ref "C41")
      (value "33pF 50V")
      (footprint "eagle-import:C0402")
      (libsource (lib "eagle-import") (part "CAP-0402"))
    )
    (comp (ref "C42")
      (value "33pF 50V")
      (footprint "eagle-import:C0402")
      (libsource (lib "eagle-import") (part "CAP-0402"))
    )
    (comp (ref "C43")
      (value "33pF 50V")
      (footprint "eagle-import:C0402")
      (libsource (lib "eagle-import") (part "CAP-0402"))
    )
    (comp (ref "C44")
      (value "100nF 25V")
      (footprint "eagle-import:C0402")
      (libsource (lib "eagle-import") (part "CAP-0402"))
    )
    (comp (ref "C45")
      (value "33pF 50V")
      (footprint "eagle-import:C0402")
      (libsource (lib "eagle-import") (part "CAP-0402"))
    )
    (comp (ref "C46")
      (value "33pF 50V")
      (footprint "eagle-import:C0402")
      (libsource (lib "eagle-import") (part "CAP-0402"))
    )
    (comp (ref "C47")
      (value "33pF 50V")
      (footprint "eagle-import:C0402")
      (libsource (lib "eagle-import") (part "CAP-0402"))
    )
    (comp (ref "C48")
      (value "47uF 25V")
      (footprint "eagle-import:ELECTRO-SMD-C-6MM")
      (libsource (lib "eagle-import") (part "CAP-POLAR-ELECTRO-C"))
    )
    (comp (ref "C49")
      (value "33pF 50V")
      (footprint "eagle-import:C0402")
      (libsource (lib "eagle-import") (part "CAP-0402"))
    )
    (comp (ref "C50")
      (value "33pF 50V")
      (footprint "eagle-import:C0402")
      (libsource (lib "eagle-import") (part "CAP-0402"))
    )
    (comp (ref "C51")
      (value "47uF 25V")
      (footprint "eagle-import:ELECTRO-SMD-C-6MM")
      (libsource (lib "eagle-import") (part "CAP-POLAR-ELECTRO-C"))
    )
    (comp (ref "C52")
      (value "33pF 50V")
      (footprint "eagle-import:C0402")
      (libsource (lib "eagle-import") (part "CAP-0402"))
    )
    (comp (ref "C53")
      (value "100nF 25V")
      (footprint "eagle-import:C0402")
      (libsource (lib "eagle-import") (part "CAP-0402"))
    )
    (comp (ref "C54")
      (value "33pF 50V")
      (footprint "eagle-import:C0402")
      (libsource (lib "eagle-import") (part "CAP-0402"))
    )
    (comp (ref "C55")
      (value "33pF 50V")
      (footprint "eagle-import:C0402")
      (libsource (lib "eagle-import") (part "CAP-0402"))
    )
    (comp (ref "C56")
      (value "100nF 50V")
      (footprint "eagle-import:C0805")
      (libsource (lib "eagle-import") (part "CAP-0805"))
    )
    (comp (ref "C57")
      (value "33pF 50V")
      (footprint "eagle-import:C0402")
      (libsource (lib "eagle-import") (part "CAP-0402"))
    )
    (comp (ref "C58")
      (value "33pF 50V")
      (footprint "eagle-import:C0402")
      (libsource (lib "eagle-import") (part "CAP-0402"))
    )
    (comp (ref "C59")
      (value "33pF 50V")
      (footprint "eagle-import:C0402")
      (libsource (lib "eagle-import") (part "CAP-0402"))
    )
    (comp (ref "C60")
      (value "33pF 50V")
      (footprint "eagle-import:C0402")
      (libsource (lib "eagle-import") (part "CAP-0402"))
    )
    (comp (ref "C61")
      (value "100nF 25V")
      (footprint "eagle-import:C0402")
      (libsource (lib "eagle-import") (part "CAP-0402"))
    )
    (comp (ref "C62")
      (value "100nF 25V")
      (footprint "eagle-import:C0402")
      (libsource (lib "eagle-import") (part "CAP-0402"))
    )
    (comp (ref "C63")
      (value "100nF 25V")
      (footprint "eagle-import:C0402")
      (libsource (lib "eagle-import") (part "CAP-0402"))
    )
    (comp (ref "C64")
      (value "100nF 25V")
      (footprint "eagle-import:C0402")
      (libsource (lib "eagle-import") (part "CAP-0402"))
    )
    (comp (ref "C65")
      (value "100nF 25V")
      (footprint "eagle-import:C0402")
      (libsource (lib "eagle-import") (part "CAP-0402"))
    )
    (comp (ref "C66")
      (value "100nF 25V")
      (footprint "eagle-import:C0402")
      (libsource (lib "eagle-import") (part "CAP-0402"))
    )
    (comp (ref "C67")
      (value "220nF")
      (footprint "eagle-import:C0402")
      (libsource (lib "eagle-import") (part "CAP-0402"))
    )
    (comp (ref "C68")
      (value "100nF 50V")
      (footprint "eagle-import:C0805")
      (libsource (lib "eagle-import") (part "CAP-0805"))
    )
    (comp (ref "C69")
      (value "100nF 25V")
      (footprint "eagle-import:C0402")
      (libsource (lib "eagle-import") (part "CAP-0402"))
    )
    (comp (ref "C70")
      (value "10uF 25V")
      (footprint "eagle-import:C0805")
      (libsource (lib "eagle-import") (part "CAP-0805"))
    )
    (comp (ref "C71")
      (value "100nF 25V")
      (footprint "eagle-import:C0402")
      (libsource (lib "eagle-import") (part "CAP-0402"))
    )
    (comp (ref "C72")
      (value "100nF 25V")
      (footprint "eagle-import:C0402")
      (libsource (lib "eagle-import") (part "CAP-0402"))
    )
    (comp (ref "C73")
      (value "100nF 25V")
      (footprint "eagle-import:C0402")
      (libsource (lib "eagle-import") (part "CAP-0402"))
    )
    (comp (ref "C74")
      (value "10uF 25V")
      (footprint "eagle-import:C0805")
      (libsource (lib "eagle-import") (part "CAP-0805"))
    )
    (comp (ref "C75")
      (value "10uF 25V")
      (footprint "eagle-import:C0805")
      (libsource (lib "eagle-import") (part "CAP-0805"))
    )
    (comp (ref "C76")
      (value "100nF 25V")
      (footprint "eagle-import:C0402")
      (libsource (lib "eagle-import") (part "CAP-0402"))
    )
    (comp (ref "C77")
      (value "100nF 25V")
      (footprint "eagle-import:C0402")
      (libsource (lib "eagle-import") (part "CAP-0402"))
    )
    (comp (ref "C78")
      (value "100nF 25V")
      (footprint "eagle-import:C0402")
      (libsource (lib "eagle-import") (part "CAP-0402"))
    )
    (comp (ref "C79")
      (value "10uF 25V")
      (footprint "eagle-import:C0805")
      (libsource (lib "eagle-import") (part "CAP-0805"))
    )
    (comp (ref "C80")
      (value "100nF 25V")
      (footprint "eagle-import:C0402")
      (libsource (lib "eagle-import") (part "CAP-0402"))
    )
    (comp (ref "C81")
      (value "100nF 25V")
      (footprint "eagle-import:C0402")
      (libsource (lib "eagle-import") (part "CAP-0402"))
    )
    (comp (ref "C82")
      (value "10uF 25V")
      (footprint "eagle-import:C0805")
      (libsource (lib "eagle-import") (part "CAP-0805"))
    )
    (comp (ref "C83")
      (value "10uF 25V")
      (footprint "eagle-import:C0805")
      (libsource (lib "eagle-import") (part "CAP-0805"))
    )
    (comp (ref "C84")
      (value "1uF 10V")
      (footprint "eagle-import:C0402")
      (libsource (lib "eagle-import") (part "CAP-0402"))
    )
    (comp (ref "D1")
      (value "Red")
      (footprint "eagle-import:LED-0603")
      (libsource (lib "eagle-import") (part "LED'0603'"))
    )
    (comp (ref "D2")
      (value "Green")
      (footprint "eagle-import:LED-0603")
      (libsource (lib "eagle-import") (part "LED'0603'"))
    )
    (comp (ref "D3")
      (value "Green")
      (footprint "eagle-import:LED-0603")
      (libsource (lib "eagle-import") (part "LED'0603'"))
    )
    (comp (ref "D4")
      (value "Green")
      (footprint "eagle-import:LED-0603")
      (libsource (lib "eagle-import") (part "LED'0603'"))
    )
    (comp (ref "D5")
      (value "Red")
      (footprint "eagle-import:LED-0603")
      (libsource (lib "eagle-import") (part "LED'0603'"))
    )
    (comp (ref "D6")
      (value "Red")
      (footprint "eagle-import:LED-0603")
      (libsource (lib "eagle-import") (part "LED'0603'"))
    )
    (comp (ref "D7")
      (value "Red")
      (footprint "eagle-import:LED-0603")
      (libsource (lib "eagle-import") (part "LED'0603'"))
    )
    (comp (ref "D8")
      (value "Red")
      (footprint "eagle-import:LED-0603")
      (libsource (lib "eagle-import") (part "LED'0603'"))
    )
    (comp (ref "D9")
      (value "DF2S6.8FS")
      (footprint "eagle-import:SOD-923")
      (libsource (lib "eagle-import") (part "D-ESD-2P'DF2S6.8FS'"))
    )
    (comp (ref "D10")
      (value "DF2S6.8FS")
      (footprint "eagle-import:SOD-923")
      (libsource (lib "eagle-import") (part "D-ESD-2P'DF2S6.8FS'"))
    )
    (comp (ref "D11")
      (value "DF2S6.8FS")
      (footprint "eagle-import:SOD-923")
      (libsource (lib "eagle-import") (part "D-ESD-2P'DF2S6.8FS'"))
    )
    (comp (ref "D12")
      (value "DF2S6.8FS")
      (footprint "eagle-import:SOD-923")
      (libsource (lib "eagle-import") (part "D-ESD-2P'DF2S6.8FS'"))
    )
    (comp (ref "D13")
      (value "DF2S6.8FS")
      (footprint "eagle-import:SOD-923")
      (libsource (lib "eagle-import") (part "D-ESD-2P'DF2S6.8FS'"))
    )
    (comp (ref "F1")
      (value "MF-FSMF010X")
      (footprint "eagle-import:F0603")
      (libsource (lib "eagle-import") (part "FUSE0603"))
    )
    (comp (ref "FUD1")
      (value "FIDUCIAL")
      (footprint "eagle-import:FIDUCIAL_40MIL")
      (libsource (lib "eagle-import") (part "FIDUCIAL"))
    )
    (comp (ref "FUD2")
      (value "FIDUCIAL")
      (footprint "eagle-import:FIDUCIAL_40MIL")
      (libsource (lib "eagle-import") (part "FIDUCIAL"))
    )
    (comp (ref "FUD3")
      (value "FIDUCIAL")
      (footprint "eagle-import:FIDUCIAL_40MIL")
      (libsource (lib "eagle-import") (part "FIDUCIAL"))
    )
    (comp (ref "FUD4")
      (value "FIDUCIAL")
      (footprint "eagle-import:FIDUCIAL_40MIL")
      (libsource (lib "eagle-import") (part "FIDUCIAL"))
    )
    (comp (ref "FUD5")
      (value "FIDUCIAL")
      (footprint "eagle-import:FIDUCIAL_40MIL")
      (libsource (lib "eagle-import") (part "FIDUCIAL"))
    )
    (comp (ref "FUD6")
      (value "FIDUCIAL")
      (footprint "eagle-import:FIDUCIAL_40MIL")
      (libsource (lib "eagle-import") (part "FIDUCIAL"))
    )
    (comp (ref "IC1")
      (value "TPD4S012DRYR")
      (footprint "eagle-import:SON6-0.5-1.45X1X0.55MM")
      (libsource (lib "eagle-import") (part "TVS-TPD4S012DRYR"))
    )
    (comp (ref "IC2")
      (value "TPD4S012DRYR")
      (footprint "eagle-import:SON6-0.5-1.45X1X0.55MM")
      (libsource (lib "eagle-import") (part "TVS-TPD4S012DRYR"))
    )
    (comp (ref "J1")
      (value "ST-USB-01H2")
      (footprint "eagle-import:MICRO-USB5+5P-SMD-0.65-7.2X5.06MM")
      (libsource (lib "eagle-import") (part "MICRO-USB5+4P-320010050"))
    )
    (comp (ref "J2")
      (value "DC-044")
      (footprint "eagle-import:DCJ3P-11.6X9.6X7.0MM")
      (libsource (lib "eagle-import") (part "POWER-JACK-DC'DC-044'"))
    )
    (comp (ref "J3")
      (value "ST-TF-003J")
      (footprint "eagle-import:MICRO-SD9+4P-SMD-16.1X14.5X1.85MM")
      (libsource (lib "eagle-import") (part "MICRO-SD-CARD-HOLDER-9P'MICROSD-9P'"))
    )
    (comp (ref "J4")
      (value "6p-2.54 DNP")
      (footprint "eagle-import:H6-2.54")
      (fields (field (name "MPN") "P125-1106A1BS116A1"))
      (libsource (lib "eagle-import") (part "826646-6"))
    )
    (comp (ref "J5")
      (value "WY-1223")
      (footprint "eagle-import:H4-2.54-10.2X5.6MM")
      (libsource (lib "eagle-import") (part "HEADER-4P-2.54MM"))
    )
    (comp (ref "J6")
      (value "ST-HD-010")
      (footprint "eagle-import:HDMI19P-0.5-15X12.15X6.18MM")
      (libsource (lib "eagle-import") (part "CONNECTOR-HDMI-19P"))
    )
    (comp (ref "J7")
      (value "2510S-4P(T)")
      (footprint "eagle-import:H4-2.54")
      (libsource (lib "eagle-import") (part "HEADER-4P-65/35MIL"))
    )
    (comp (ref "J8")
      (value "2510S-4P(T)")
      (footprint "eagle-import:H4-2.54")
      (libsource (lib "eagle-import") (part "HEADER-4P-65/35MIL"))
    )
    (comp (ref "JP2")
      (value "ST-USB-003A")
      (footprint "eagle-import:USB4+2-2.0-90D")
      (libsource (lib "eagle-import") (part "USB4+2P-320010007"))
    )
    (comp (ref "L1")
      (value "BLM15PD121SN1D")
      (footprint "eagle-import:L0402")
      (libsource (lib "eagle-import") (part "INDUCTOR/FERRITE-BEAD'0402'"))
    )
    (comp (ref "L2")
      (value "BLM15PD121SN1D")
      (footprint "eagle-import:L0402")
      (libsource (lib "eagle-import") (part "INDUCTOR/FERRITE-BEAD'0402'"))
    )
    (comp (ref "L3")
      (value "IHLP3232DZER100M01")
      (footprint "eagle-import:INT2-7.268-8.64X8.18X4MM")
      (libsource (lib "eagle-import") (part "INDUCTOR/FERRITE-BEAD-IHLP3232DZER100M01"))
    )
    (comp (ref "L4")
      (value "BLM21PG331SN1D")
      (footprint "eagle-import:L0805")
      (libsource (lib "eagle-import") (part "INDUCTOR/FERRITE-BEAD'0805'"))
    )
    (comp (ref "L5")
      (value "BLM21PG331SN1D")
      (footprint "eagle-import:L0805")
      (libsource (lib "eagle-import") (part "INDUCTOR/FERRITE-BEAD'0805'"))
    )
    (comp (ref "L6")
      (value "LQH44PN1R0NP0L")
      (footprint "eagle-import:L4.4X3.0MM")
      (libsource (lib "eagle-import") (part "L"))
    )
    (comp (ref "L7")
      (value "BLM15PD121SN1D")
      (footprint "eagle-import:L0402")
      (libsource (lib "eagle-import") (part "INDUCTOR/FERRITE-BEAD'0402'"))
    )
    (comp (ref "L8")
      (value "BLM15PD121SN1D")
      (footprint "eagle-import:L0402")
      (libsource (lib "eagle-import") (part "INDUCTOR/FERRITE-BEAD'0402'"))
    )
    (comp (ref "L9")
      (value "BLM15PD121SN1D")
      (footprint "eagle-import:L0402")
      (libsource (lib "eagle-import") (part "INDUCTOR/FERRITE-BEAD'0402'"))
    )
    (comp (ref "L10")
      (value "WPN201610MR47MT")
      (footprint "eagle-import:L201610")
      (libsource (lib "eagle-import") (part "L-MPM201610SR33_T"))
    )
    (comp (ref "MGT1")
      (value "MOUNTING_HOLE")
      (footprint "eagle-import:MOUNTING_HOLE")
      (libsource (lib "eagle-import") (part "MOUNTING_HOLE"))
    )
    (comp (ref "MGT2")
      (value "MOUNTING_HOLE")
      (footprint "eagle-import:MOUNTING_HOLE")
      (libsource (lib "eagle-import") (part "MOUNTING_HOLE"))
    )
    (comp (ref "MGT3")
      (value "MOUNTING_HOLE")
      (footprint "eagle-import:MOUNTING_HOLE")
      (libsource (lib "eagle-import") (part "MOUNTING_HOLE"))
    )
    (comp (ref "MGT4")
      (value "MOUNTING_HOLE")
      (footprint "eagle-import:MOUNTING_HOLE")
      (libsource (lib "eagle-import") (part "MOUNTING_HOLE"))
    )
    (comp (ref "Q1")
      (value "BSS138W-7-F")
      (footprint "eagle-import:SOT-323")
      (libsource (lib "eagle-import") (part "MOSFET-N'SI1304BDL'"))
    )
    (comp (ref "Q2")
      (value "BSS138W-7-F")
      (footprint "eagle-import:SOT-323")
      (libsource (lib "eagle-import") (part "MOSFET-N'SI1304BDL'"))
    )
    (comp (ref "Q3")
      (value "BSS138W-7-F")
      (footprint "eagle-import:SOT-323")
      (libsource (lib "eagle-import") (part "MOSFET-N'SI1304BDL'"))
    )
    (comp (ref "Q4")
      (value "MMBT2907A")
      (footprint "eagle-import:SOT-323")
      (libsource (lib "eagle-import") (part "TRANSISTOR-PNP"))
    )
    (comp (ref "R1")
      (value "1.5k 1%")
      (footprint "eagle-import:R0402")
      (libsource (lib "eagle-import") (part "RES-0402"))
    )
    (comp (ref "R2")
      (value "1.5k 1%")
      (footprint "eagle-import:R0402")
      (libsource (lib "eagle-import") (part "RES-0402"))
    )
    (comp (ref "R3")
      (value "10k 1%")
      (footprint "eagle-import:R0402")
      (libsource (lib "eagle-import") (part "RES-0402"))
    )
    (comp (ref "R4")
      (value "10k")
      (footprint "eagle-import:R0402")
      (libsource (lib "eagle-import") (part "RES-0402"))
    )
    (comp (ref "R5")
      (value "1k")
      (footprint "eagle-import:R0402")
      (libsource (lib "eagle-import") (part "RES-0402"))
    )
    (comp (ref "R6")
      (value "10k")
      (footprint "eagle-import:R0402")
      (libsource (lib "eagle-import") (part "RES-0402"))
    )
    (comp (ref "R7")
      (value "10k")
      (footprint "eagle-import:R0402")
      (libsource (lib "eagle-import") (part "RES-0402"))
    )
    (comp (ref "R8")
      (value "10k")
      (footprint "eagle-import:R0402")
      (libsource (lib "eagle-import") (part "RES-0402"))
    )
    (comp (ref "R9")
      (value "10k")
      (footprint "eagle-import:R0402")
      (libsource (lib "eagle-import") (part "RES-0402"))
    )
    (comp (ref "R10")
      (value "10k")
      (footprint "eagle-import:R0402")
      (libsource (lib "eagle-import") (part "RES-0402"))
    )
    (comp (ref "R11")
      (value "1k")
      (footprint "eagle-import:R0402")
      (libsource (lib "eagle-import") (part "RES-0402"))
    )
    (comp (ref "R12")
      (value "1k")
      (footprint "eagle-import:R0402")
      (libsource (lib "eagle-import") (part "RES-0402"))
    )
    (comp (ref "R13")
      (value "33R")
      (footprint "eagle-import:R0402")
      (libsource (lib "eagle-import") (part "RES-0402"))
    )
    (comp (ref "R14")
      (value "33R")
      (footprint "eagle-import:R0402")
      (libsource (lib "eagle-import") (part "RES-0402"))
    )
    (comp (ref "R15")
      (value "33R")
      (footprint "eagle-import:R0402")
      (libsource (lib "eagle-import") (part "RES-0402"))
    )
    (comp (ref "R16")
      (value "33R")
      (footprint "eagle-import:R0402")
      (libsource (lib "eagle-import") (part "RES-0402"))
    )
    (comp (ref "R17")
      (value "499R")
      (footprint "eagle-import:R0402")
      (libsource (lib "eagle-import") (part "RES-0402"))
    )
    (comp (ref "R18")
      (value "1.5k 1%")
      (footprint "eagle-import:R0402")
      (libsource (lib "eagle-import") (part "RES-0402"))
    )
    (comp (ref "R19")
      (value "33R")
      (footprint "eagle-import:R0402")
      (libsource (lib "eagle-import") (part "RES-0402"))
    )
    (comp (ref "R20")
      (value "40.2k 1%")
      (footprint "eagle-import:R0402")
      (libsource (lib "eagle-import") (part "RES-0402"))
    )
    (comp (ref "R21")
      (value "10k 1%")
      (footprint "eagle-import:R0402")
      (libsource (lib "eagle-import") (part "RES-0402"))
    )
    (comp (ref "R22")
      (value "33R")
      (footprint "eagle-import:R0402")
      (libsource (lib "eagle-import") (part "RES-0402"))
    )
    (comp (ref "R23")
      (value "0R")
      (footprint "eagle-import:R0402")
      (libsource (lib "eagle-import") (part "RES-0402"))
    )
    (comp (ref "R24")
      (value "0R")
      (footprint "eagle-import:R0402")
      (libsource (lib "eagle-import") (part "RES-0402"))
    )
    (comp (ref "R25")
      (value "33R")
      (footprint "eagle-import:R0402")
      (libsource (lib "eagle-import") (part "RES-0402"))
    )
    (comp (ref "R26")
      (value "33R")
      (footprint "eagle-import:R0402")
      (libsource (lib "eagle-import") (part "RES-0402"))
    )
    (comp (ref "R27")
      (value "33R")
      (footprint "eagle-import:R0402")
      (libsource (lib "eagle-import") (part "RES-0402"))
    )
    (comp (ref "R28")
      (value "33R")
      (footprint "eagle-import:R0402")
      (libsource (lib "eagle-import") (part "RES-0402"))
    )
    (comp (ref "R29")
      (value "33R")
      (footprint "eagle-import:R0402")
      (libsource (lib "eagle-import") (part "RES-0402"))
    )
    (comp (ref "R30")
      (value "DNP 10k")
      (footprint "eagle-import:R0402")
      (libsource (lib "eagle-import") (part "RES-0402"))
    )
    (comp (ref "R31")
      (value "1k")
      (footprint "eagle-import:R0402")
      (libsource (lib "eagle-import") (part "RES-0402"))
    )
    (comp (ref "R32")
      (value "100K, 1%, DNI")
      (footprint "eagle-import:R0402")
      (libsource (lib "eagle-import") (part "RES-0402"))
    )
    (comp (ref "R33")
      (value "100k 1%")
      (footprint "eagle-import:R0402")
      (libsource (lib "eagle-import") (part "RES-0402"))
    )
    (comp (ref "R34")
      (value "100k 1%")
      (footprint "eagle-import:R0402")
      (libsource (lib "eagle-import") (part "RES-0402"))
    )
    (comp (ref "R35")
      (value "100k 1%")
      (footprint "eagle-import:R0402")
      (libsource (lib "eagle-import") (part "RES-0402"))
    )
    (comp (ref "R36")
      (value "100k 1%")
      (footprint "eagle-import:R0402")
      (libsource (lib "eagle-import") (part "RES-0402"))
    )
    (comp (ref "R37")
      (value "100k 1%")
      (footprint "eagle-import:R0402")
      (libsource (lib "eagle-import") (part "RES-0402"))
    )
    (comp (ref "R38")
      (value "100k 1%")
      (footprint "eagle-import:R0402")
      (libsource (lib "eagle-import") (part "RES-0402"))
    )
    (comp (ref "R39")
      (value "100k 1%")
      (footprint "eagle-import:R0402")
      (libsource (lib "eagle-import") (part "RES-0402"))
    )
    (comp (ref "R40")
      (value "100k 1%")
      (footprint "eagle-import:R0402")
      (libsource (lib "eagle-import") (part "RES-0402"))
    )
    (comp (ref "R41")
      (value "100k 1%")
      (footprint "eagle-import:R0402")
      (libsource (lib "eagle-import") (part "RES-0402"))
    )
    (comp (ref "R42")
      (value "100k 1%")
      (footprint "eagle-import:R0402")
      (libsource (lib "eagle-import") (part "RES-0402"))
    )
    (comp (ref "R43")
      (value "100k 1%")
      (footprint "eagle-import:R0402")
      (libsource (lib "eagle-import") (part "RES-0402"))
    )
    (comp (ref "R44")
      (value "100k 1%")
      (footprint "eagle-import:R0402")
      (libsource (lib "eagle-import") (part "RES-0402"))
    )
    (comp (ref "R45")
      (value "100k 1%")
      (footprint "eagle-import:R0402")
      (libsource (lib "eagle-import") (part "RES-0402"))
    )
    (comp (ref "R46")
      (value "100k 1%")
      (footprint "eagle-import:R0402")
      (libsource (lib "eagle-import") (part "RES-0402"))
    )
    (comp (ref "R47")
      (value "0R")
      (footprint "eagle-import:R0402")
      (libsource (lib "eagle-import") (part "RES-0402"))
    )
    (comp (ref "R48")
      (value "0R")
      (footprint "eagle-import:R1206")
      (libsource (lib "eagle-import") (part "RES-1206"))
    )
    (comp (ref "R49")
      (value "100k 1%")
      (footprint "eagle-import:R0402")
      (libsource (lib "eagle-import") (part "RES-0402"))
    )
    (comp (ref "R50")
      (value "100k 1%")
      (footprint "eagle-import:R0402")
      (libsource (lib "eagle-import") (part "RES-0402"))
    )
    (comp (ref "R51")
      (value "1.5k 1%")
      (footprint "eagle-import:R0402")
      (libsource (lib "eagle-import") (part "RES-0402"))
    )
    (comp (ref "R52")
      (value "1.5k 1%")
      (footprint "eagle-import:R0402")
      (libsource (lib "eagle-import") (part "RES-0402"))
    )
    (comp (ref "R53")
      (value "1.5k 1%")
      (footprint "eagle-import:R0402")
      (libsource (lib "eagle-import") (part "RES-0402"))
    )
    (comp (ref "R54")
      (value "1.5k 1%")
      (footprint "eagle-import:R0402")
      (libsource (lib "eagle-import") (part "RES-0402"))
    )
    (comp (ref "R55")
      (value "1M 1%")
      (footprint "eagle-import:R0402")
      (libsource (lib "eagle-import") (part "RES-0402"))
    )
    (comp (ref "R56")
      (value "1M, 1%, DNI")
      (footprint "eagle-import:R0402")
      (libsource (lib "eagle-import") (part "RES-0402"))
    )
    (comp (ref "R57")
      (value "560k 1%")
      (footprint "eagle-import:R0402")
      (libsource (lib "eagle-import") (part "RES-0402"))
    )
    (comp (ref "R58")
      (value "100k 1%")
      (footprint "eagle-import:R0402")
      (libsource (lib "eagle-import") (part "RES-0402"))
    )
    (comp (ref "R59")
      (value "49.9R 1%")
      (footprint "eagle-import:R0402")
      (libsource (lib "eagle-import") (part "RES-0402"))
    )
    (comp (ref "R60")
      (value "100k 1%")
      (footprint "eagle-import:R0402")
      (libsource (lib "eagle-import") (part "RES-0402"))
    )
    (comp (ref "R61")
      (value "13.3k 1%")
      (footprint "eagle-import:R0402")
      (libsource (lib "eagle-import") (part "RES-0402"))
    )
    (comp (ref "R62")
      (value "10k 1%")
      (footprint "eagle-import:R0402")
      (libsource (lib "eagle-import") (part "RES-0402"))
    )
    (comp (ref "R63")
      (value "10k")
      (footprint "eagle-import:R0402")
      (libsource (lib "eagle-import") (part "RES-0402"))
    )
    (comp (ref "R64")
      (value "0R")
      (footprint "eagle-import:R0402")
      (libsource (lib "eagle-import") (part "RES-0402"))
    )
    (comp (ref "R65")
      (value "0R")
      (footprint "eagle-import:R0402")
      (libsource (lib "eagle-import") (part "RES-0402"))
    )
    (comp (ref "R66")
      (value "0R")
      (footprint "eagle-import:R0402")
      (libsource (lib "eagle-import") (part "RES-0402"))
    )
    (comp (ref "R67")
      (value "10k")
      (footprint "eagle-import:R0402")
      (libsource (lib "eagle-import") (part "RES-0402"))
    )
    (comp (ref "R68")
      (value "10k")
      (footprint "eagle-import:R0402")
      (libsource (lib "eagle-import") (part "RES-0402"))
    )
    (comp (ref "R69")
      (value "10k 1%")
      (footprint "eagle-import:R0402")
      (libsource (lib "eagle-import") (part "RES-0402"))
    )
    (comp (ref "R70")
      (value "10k 1%")
      (footprint "eagle-import:R0402")
      (libsource (lib "eagle-import") (part "RES-0402"))
    )
    (comp (ref "R71")
      (value "10k")
      (footprint "eagle-import:R0402")
      (libsource (lib "eagle-import") (part "RES-0402"))
    )
    (comp (ref "R72")
      (value "10k")
      (footprint "eagle-import:R0402")
      (libsource (lib "eagle-import") (part "RES-0402"))
    )
    (comp (ref "R73")
      (value "10k")
      (footprint "eagle-import:R0402")
      (libsource (lib "eagle-import") (part "RES-0402"))
    )
    (comp (ref "R74")
      (value "10k")
      (footprint "eagle-import:R0402")
      (libsource (lib "eagle-import") (part "RES-0402"))
    )
    (comp (ref "R75")
      (value "10k")
      (footprint "eagle-import:R0402")
      (libsource (lib "eagle-import") (part "RES-0402"))
    )
    (comp (ref "R76")
      (value "51k 1%")
      (footprint "eagle-import:R0402")
      (libsource (lib "eagle-import") (part "RES-0402"))
    )
    (comp (ref "R77")
      (value "1.3k 1%")
      (footprint "eagle-import:R0402")
      (libsource (lib "eagle-import") (part "RES-0402"))
    )
    (comp (ref "R78")
      (value "240k 1%")
      (footprint "eagle-import:R0402")
      (libsource (lib "eagle-import") (part "RES-0402"))
    )
    (comp (ref "R79")
      (value "1k")
      (footprint "eagle-import:R0402")
      (libsource (lib "eagle-import") (part "RES-0402"))
    )
    (comp (ref "R80")
      (value "100k 1%")
      (footprint "eagle-import:R0402")
      (libsource (lib "eagle-import") (part "RES-0402"))
    )
    (comp (ref "R81")
      (value "10k")
      (footprint "eagle-import:R0402")
      (libsource (lib "eagle-import") (part "RES-0402"))
    )
    (comp (ref "R82")
      (value "10k")
      (footprint "eagle-import:R0402")
      (libsource (lib "eagle-import") (part "RES-0402"))
    )
    (comp (ref "R83")
      (value "10k")
      (footprint "eagle-import:R0402")
      (libsource (lib "eagle-import") (part "RES-0402"))
    )
    (comp (ref "R84")
      (value "10k")
      (footprint "eagle-import:R0402")
      (libsource (lib "eagle-import") (part "RES-0402"))
    )
    (comp (ref "R85")
      (value "0R")
      (footprint "eagle-import:R0402")
      (libsource (lib "eagle-import") (part "RES-0402"))
    )
    (comp (ref "R86")
      (value "DNP")
      (footprint "eagle-import:R0402")
      (libsource (lib "eagle-import") (part "RES-0402"))
    )
    (comp (ref "R87")
      (value "10k")
      (footprint "eagle-import:R0402")
      (libsource (lib "eagle-import") (part "RES-0402"))
    )
    (comp (ref "R88")
      (value "10k")
      (footprint "eagle-import:R0402")
      (libsource (lib "eagle-import") (part "RES-0402"))
    )
    (comp (ref "R89")
      (value "10k")
      (footprint "eagle-import:R0402")
      (libsource (lib "eagle-import") (part "RES-0402"))
    )
    (comp (ref "R90")
      (value "10k")
      (footprint "eagle-import:R0402")
      (libsource (lib "eagle-import") (part "RES-0402"))
    )
    (comp (ref "R91")
      (value "10k")
      (footprint "eagle-import:R0402")
      (libsource (lib "eagle-import") (part "RES-0402"))
    )
    (comp (ref "R92")
      (value "10k")
      (footprint "eagle-import:R0402")
      (libsource (lib "eagle-import") (part "RES-0402"))
    )
    (comp (ref "R93")
      (value "10k")
      (footprint "eagle-import:R0402")
      (libsource (lib "eagle-import") (part "RES-0402"))
    )
    (comp (ref "R94")
      (value "10k")
      (footprint "eagle-import:R0402")
      (libsource (lib "eagle-import") (part "RES-0402"))
    )
    (comp (ref "R95")
      (value "22R")
      (footprint "eagle-import:R0402")
      (libsource (lib "eagle-import") (part "RES-0402"))
    )
    (comp (ref "R96")
      (value "1k")
      (footprint "eagle-import:R0402")
      (libsource (lib "eagle-import") (part "RES-0402"))
    )
    (comp (ref "R97")
      (value "0R")
      (footprint "eagle-import:R1206")
      (libsource (lib "eagle-import") (part "RES-1206"))
    )
    (comp (ref "R98")
      (value "10k")
      (footprint "eagle-import:R0402")
      (libsource (lib "eagle-import") (part "RES-0402"))
    )
    (comp (ref "R99")
      (value "5.6K 1%")
      (footprint "eagle-import:R0402")
      (libsource (lib "eagle-import") (part "RES-0402"))
    )
    (comp (ref "R100")
      (value "10k")
      (footprint "eagle-import:R0402")
      (libsource (lib "eagle-import") (part "RES-0402"))
    )
    (comp (ref "R101")
      (value "DNP")
      (footprint "eagle-import:R0402")
      (libsource (lib "eagle-import") (part "RES-0402"))
    )
    (comp (ref "R102")
      (value "22R")
      (footprint "eagle-import:R0402")
      (libsource (lib "eagle-import") (part "RES-0402"))
    )
    (comp (ref "R103")
      (value "22R")
      (footprint "eagle-import:R0402")
      (libsource (lib "eagle-import") (part "RES-0402"))
    )
    (comp (ref "R104")
      (value "2k")
      (footprint "eagle-import:R0402")
      (libsource (lib "eagle-import") (part "RES-0402"))
    )
    (comp (ref "R105")
      (value "2k")
      (footprint "eagle-import:R0402")
      (libsource (lib "eagle-import") (part "RES-0402"))
    )
    (comp (ref "R106")
      (value "10k")
      (footprint "eagle-import:R0402")
      (libsource (lib "eagle-import") (part "RES-0402"))
    )
    (comp (ref "R107")
      (value "33k")
      (footprint "eagle-import:R0402")
      (libsource (lib "eagle-import") (part "RES-0402"))
    )
    (comp (ref "R108")
      (value "10k")
      (footprint "eagle-import:R0402")
      (libsource (lib "eagle-import") (part "RES-0402"))
    )
    (comp (ref "R109")
      (value "10k")
      (footprint "eagle-import:R0402")
      (libsource (lib "eagle-import") (part "RES-0402"))
    )
    (comp (ref "R110")
      (value "0.1R")
      (footprint "eagle-import:R1206")
      (libsource (lib "eagle-import") (part "RES-1206"))
    )
    (comp (ref "R111")
      (value "0.1R")
      (footprint "eagle-import:R1206")
      (libsource (lib "eagle-import") (part "RES-1206"))
    )
    (comp (ref "R112")
      (value "10k")
      (footprint "eagle-import:R0402")
      (libsource (lib "eagle-import") (part "RES-0402"))
    )
    (comp (ref "R113")
      (value "100k 1%")
      (footprint "eagle-import:R0402")
      (libsource (lib "eagle-import") (part "RES-0402"))
    )
    (comp (ref "R114")
      (value "100k 1%")
      (footprint "eagle-import:R0402")
      (libsource (lib "eagle-import") (part "RES-0402"))
    )
    (comp (ref "R115")
      (value "22R")
      (footprint "eagle-import:R0402")
      (libsource (lib "eagle-import") (part "RES-0402"))
    )
    (comp (ref "R116")
      (value "0R")
      (footprint "eagle-import:R0402")
      (libsource (lib "eagle-import") (part "RES-0402"))
    )
    (comp (ref "R117")
      (value "0R")
      (footprint "eagle-import:R0402")
      (libsource (lib "eagle-import") (part "RES-0402"))
    )
    (comp (ref "R118")
      (value "0R")
      (footprint "eagle-import:R0402")
      (libsource (lib "eagle-import") (part "RES-0402"))
    )
    (comp (ref "R119")
      (value "10k")
      (footprint "eagle-import:R0402")
      (libsource (lib "eagle-import") (part "RES-0402"))
    )
    (comp (ref "SW1")
      (value "SKRPABE010")
      (footprint "eagle-import:BUTTON4P-SMD-4.5X3.2X2.5MM")
      (libsource (lib "eagle-import") (part "BUTTON-4P+"))
    )
    (comp (ref "SW2")
      (value "SKRPABE010")
      (footprint "eagle-import:BUTTON4P-SMD-4.5X3.2X2.5MM")
      (libsource (lib "eagle-import") (part "BUTTON-4P+"))
    )
    (comp (ref "TP1")
      (value "PAD-TEST-POINT'4545'")
      (footprint "eagle-import:TP_4545")
      (fields (field (name "PARTNO") "DNP"))
      (libsource (lib "eagle-import") (part "PAD-TEST-POINT'4545'"))
    )
    (comp (ref "TP2")
      (value "TPB0,65")
      (footprint "eagle-import:TP_B0,65")
      (libsource (lib "eagle-import") (part "TPB0,65"))
    )
    (comp (ref "TP3")
      (value "TPB0,65")
      (footprint "eagle-import:TP_B0,65")
      (libsource (lib "eagle-import") (part "TPB0,65"))
    )
    (comp (ref "TP4")
      (value "TPB0,65")
      (footprint "eagle-import:TP_B0,65")
      (libsource (lib "eagle-import") (part "TPB0,65"))
    )
    (comp (ref "TP5")
      (value "TESTPAD/W_HOLE_1X1")
      (footprint "eagle-import:TESTPAD_W_HOLE_1X1")
      (libsource (lib "eagle-import") (part "TESTPAD/W_HOLE_1X1"))
    )
    (comp (ref "TP6")
      (value "TESTPAD/W_HOLE_1X1")
      (footprint "eagle-import:TESTPAD_W_HOLE_1X1")
      (libsource (lib "eagle-import") (part "TESTPAD/W_HOLE_1X1"))
    )
    (comp (ref "TP7")
      (value "TESTPAD/W_HOLE_1X1")
      (footprint "eagle-import:TESTPAD_W_HOLE_1X1")
      (libsource (lib "eagle-import") (part "TESTPAD/W_HOLE_1X1"))
    )
    (comp (ref "TP8")
      (value "TESTPAD/W_HOLE_1X1")
      (footprint "eagle-import:TESTPAD_W_HOLE_1X1")
      (libsource (lib "eagle-import") (part "TESTPAD/W_HOLE_1X1"))
    )
    (comp (ref "TP9")
      (value "TPB0,65")
      (footprint "eagle-import:TP_B0,65")
      (libsource (lib "eagle-import") (part "TPB0,65"))
    )
    (comp (ref "TP10")
      (value "TEST-POINT-D65/35")
      (footprint "eagle-import:TP-D65_35MIL")
      (libsource (lib "eagle-import") (part "TEST-POINT-D65/35"))
    )
    (comp (ref "TP11")
      (value "TPB0,65")
      (footprint "eagle-import:TP_B0,65")
      (libsource (lib "eagle-import") (part "TPB0,65"))
    )
    (comp (ref "TP12")
      (value "TPB0,65")
      (footprint "eagle-import:TP_B0,65")
      (libsource (lib "eagle-import") (part "TPB0,65"))
    )
    (comp (ref "TP13")
      (value "TPB0,65")
      (footprint "eagle-import:TP_B0,65")
      (libsource (lib "eagle-import") (part "TPB0,65"))
    )
    (comp (ref "TP14")
      (value "TPB0,65")
      (footprint "eagle-import:TP_B0,65")
      (libsource (lib "eagle-import") (part "TPB0,65"))
    )
    (comp (ref "TP15")
      (value "TPB0,65")
      (footprint "eagle-import:TP_B0,65")
      (libsource (lib "eagle-import") (part "TPB0,65"))
    )
    (comp (ref "TP16")
      (value "TPB0,65")
      (footprint "eagle-import:TP_B0,65")
      (libsource (lib "eagle-import") (part "TPB0,65"))
    )
    (comp (ref "TP17")
      (value "TEST-POINT'4545'")
      (footprint "eagle-import:TP-D45MIL")
      (fields (field (name "PARTNO") "DNP"))
      (libsource (lib "eagle-import") (part "TEST-POINT'4545'"))
    )
    (comp (ref "TP18")
      (value "TEST-POINT'4545'")
      (footprint "eagle-import:TP-D45MIL")
      (fields (field (name "PARTNO") "DNP"))
      (libsource (lib "eagle-import") (part "TEST-POINT'4545'"))
    )
    (comp (ref "TP19")
      (value "TEST-POINT'4545'")
      (footprint "eagle-import:TP-D45MIL")
      (fields (field (name "PARTNO") "DNP"))
      (libsource (lib "eagle-import") (part "TEST-POINT'4545'"))
    )
    (comp (ref "TP20")
      (value "TEST-POINT'4545'")
      (footprint "eagle-import:TP-D45MIL")
      (fields (field (name "PARTNO") "DNP"))
      (libsource (lib "eagle-import") (part "TEST-POINT'4545'"))
    )
    (comp (ref "TP21")
      (value "TPB0,65")
      (footprint "eagle-import:TP_B0,65")
      (libsource (lib "eagle-import") (part "TPB0,65"))
    )
    (comp (ref "TP22")
      (value "TPB0,65")
      (footprint "eagle-import:TP_B0,65")
      (libsource (lib "eagle-import") (part "TPB0,65"))
    )
    (comp (ref "TP23")
      (value "TPB0,65")
      (footprint "eagle-import:TP_B0,65")
      (libsource (lib "eagle-import") (part "TPB0,65"))
    )
    (comp (ref "TP24")
      (value "TPB0,65")
      (footprint "eagle-import:TP_B0,65")
      (libsource (lib "eagle-import") (part "TPB0,65"))
    )
    (comp (ref "TP25")
      (value "TEST-POINT'4545'")
      (footprint "eagle-import:TP-D45MIL")
      (fields (field (name "PARTNO") "DNP"))
      (libsource (lib "eagle-import") (part "TEST-POINT'4545'"))
    )
    (comp (ref "TP26")
      (value "TESTPAD/W_HOLE_1X1")
      (footprint "eagle-import:TESTPAD_W_HOLE_1X1")
      (libsource (lib "eagle-import") (part "TESTPAD/W_HOLE_1X1"))
    )
    (comp (ref "TP27")
      (value "TEST-POINT'4545'")
      (footprint "eagle-import:TP-D45MIL")
      (fields (field (name "PARTNO") "DNP"))
      (libsource (lib "eagle-import") (part "TEST-POINT'4545'"))
    )
    (comp (ref "TP28")
      (value "TEST-POINT'4545'")
      (footprint "eagle-import:TP-D45MIL")
      (fields (field (name "PARTNO") "DNP"))
      (libsource (lib "eagle-import") (part "TEST-POINT'4545'"))
    )
    (comp (ref "TP29")
      (value "TEST-POINT'4545'")
      (footprint "eagle-import:TP-D45MIL")
      (fields (field (name "PARTNO") "DNP"))
      (libsource (lib "eagle-import") (part "TEST-POINT'4545'"))
    )
    (comp (ref "TP30")
      (value "TEST-POINT'4545'")
      (footprint "eagle-import:TP-D45MIL")
      (fields (field (name "PARTNO") "DNP"))
      (libsource (lib "eagle-import") (part "TEST-POINT'4545'"))
    )
    (comp (ref "TP31")
      (value "TEST-POINT'4545'")
      (footprint "eagle-import:TP-D45MIL")
      (fields (field (name "PARTNO") "DNP"))
      (libsource (lib "eagle-import") (part "TEST-POINT'4545'"))
    )
    (comp (ref "TP32")
      (value "TEST-POINT'4545'")
      (footprint "eagle-import:TP-D45MIL")
      (fields (field (name "PARTNO") "DNP"))
      (libsource (lib "eagle-import") (part "TEST-POINT'4545'"))
    )
    (comp (ref "TP34")
      (value "TEST-POINT-D65/35")
      (footprint "eagle-import:TP-D65_35MIL")
      (libsource (lib "eagle-import") (part "TEST-POINT-D65/35"))
    )
    (comp (ref "U1")
      (value "OSD3358-512M-BSM")
      (footprint "eagle-import:BGA256-1.27-21X21MM")
      (libsource (lib "eagle-import") (part "MPU-OSD3358-512M-BSM"))
    )
    (comp (ref "U2")
      (value "SN74LVC1G07DCKR")
      (footprint "eagle-import:5P-SMD-2X1.2X1MM")
      (libsource (lib "eagle-import") (part "LOGIC-SN74LVC1G07-DCK"))
    )
    (comp (ref "U3")
      (value "ATL431AIDBZR")
      (footprint "eagle-import:SOT-23")
      (libsource (lib "eagle-import") (part "PMIC-CJ432'CJ432'"))
    )
    (comp (ref "U4")
      (value "WL1835MODGBMOCT")
      (footprint "eagle-import:MODULE100P-0.7-13.5X13.2MM")
      (libsource (lib "eagle-import") (part "MODULE-RF-WL1835MOD"))
    )
    (comp (ref "U5")
      (value "APX811-44UG-7")
      (footprint "eagle-import:SOT143-R")
      (libsource (lib "eagle-import") (part "SUPERVISOR-APX811-31UGSOT"))
    )
    (comp (ref "U6")
      (value "TPS54302")
      (footprint "eagle-import:SOT-23-6")
      (libsource (lib "eagle-import") (part "PMIC-TPS54302"))
    )
    (comp (ref "U7")
      (value "TPS2051BDGNR")
      (footprint "eagle-import:MSOP8-0.65-3X3MM")
      (libsource (lib "eagle-import") (part "SWITCH-TPS2051B"))
    )
    (comp (ref "U8")
      (value "TLV62569DBVT")
      (footprint "eagle-import:SOT-23-5")
      (libsource (lib "eagle-import") (part "PMIC-TLV62569'DBVT'"))
    )
    (comp (ref "U9")
      (value "SN74LVC1G125DCKR")
      (footprint "eagle-import:SOT-353")
      (libsource (lib "eagle-import") (part "LOGIC-SN74AUP1G125'DCK'"))
    )
    (comp (ref "U10")
      (value "SN74LVC2G241DCUR")
      (footprint "eagle-import:DCU8")
      (libsource (lib "eagle-import") (part "LOGIC-SN74LVC2G241"))
    )
    (comp (ref "U11")
      (value "IT66121FN")
      (footprint "eagle-import:QFN64-0.5-9X9MM")
      (libsource (lib "eagle-import") (part "TRANSFER_IT66121FN-9"))
    )
    (comp (ref "U12")
      (value "A4988SETTR-T")
      (footprint "eagle-import:QFN-28-5MM")
      (libsource (lib "eagle-import") (part "TRANSLATOR-A4983"))
    )
    (comp (ref "U13")
      (value "ESD-RCLAMP0524P")
      (footprint "eagle-import:ESD10P-0.5-2.5X1X0.58MM")
      (libsource (lib "eagle-import") (part "ESD-RCLAMP0524P"))
    )
    (comp (ref "U14")
      (value "ESD-RCLAMP0524P")
      (footprint "eagle-import:ESD10P-0.5-2.5X1X0.58MM")
      (libsource (lib "eagle-import") (part "ESD-RCLAMP0524P"))
    )
    (comp (ref "U16")
      (value "TLV62569DBVT")
      (footprint "eagle-import:SOT-23-5")
      (libsource (lib "eagle-import") (part "PMIC-TLV62569'DBVT'"))
    )
    (comp (ref "VR1")
      (value "EVM3GSX50B14")
      (footprint "eagle-import:ADJR3-SMD-3.6X3.3MM")
      (libsource (lib "eagle-import") (part "RES-ADJ-SMD"))
    )
    (comp (ref "X1")
      (value "ST3215SB32768H5HPWAA")
      (footprint "eagle-import:X2-SMD-3.2X1.5X0.55MM")
      (libsource (lib "eagle-import") (part "CRYSTAL-2P-3215"))
    )
    (comp (ref "Y1")
      (value "CX3225GB24000P0HPQCC")
      (footprint "eagle-import:CRYSTAL-TXC-7A")
      (libsource (lib "eagle-import") (part "7A-24.000MAAJ-T"))
    )
  )
  (nets
    (net (code "1") (name "/12VDC") (class "Default")
      (node (ref "C48") (pin "+") (pinfunction "+_+") (pintype "passive"))
      (node (ref "C51") (pin "+") (pinfunction "+_+") (pintype "passive"))
      (node (ref "C68") (pin "2") (pinfunction "2_2") (pintype "passive"))
      (node (ref "R97") (pin "2") (pinfunction "2_2") (pintype "passive"))
      (node (ref "U12") (pin "22") (pinfunction "VBB1_22") (pintype "bidirectional"))
      (node (ref "U12") (pin "28") (pinfunction "VBB2_28") (pintype "bidirectional"))
    )
    (net (code "2") (name "/AIN7") (class "Default")
      (node (ref "U1") (pin "D6") (pinfunction "PMIC_MUX_OUT_D6") (pintype "bidirectional"))
      (node (ref "U1") (pin "D7") (pinfunction "AIN7_D7") (pintype "bidirectional"))
    )
    (net (code "3") (name "/BT_EN") (class "Default")
      (node (ref "Q3") (pin "1") (pinfunction "G_1") (pintype "passive"))
      (node (ref "U1") (pin "H15") (pinfunction "MII1_TXD0_H15") (pintype "bidirectional"))
      (node (ref "U4") (pin "41") (pinfunction "BT_EN_41") (pintype "bidirectional"))
    )
    (net (code "4") (name "/BT_HCI_CTS") (class "Default")
      (node (ref "R14") (pin "2") (pinfunction "2_2") (pintype "passive"))
      (node (ref "U1") (pin "D13") (pinfunction "MDC_D13") (pintype "bidirectional"))
    )
    (net (code "5") (name "/BT_HCI_RTS") (class "Default")
      (node (ref "R13") (pin "2") (pinfunction "2_2") (pintype "passive"))
      (node (ref "U1") (pin "E13") (pinfunction "MDIO_E13") (pintype "bidirectional"))
    )
    (net (code "6") (name "/BT_HCI_RX") (class "Default")
      (node (ref "R16") (pin "2") (pinfunction "2_2") (pintype "passive"))
      (node (ref "U1") (pin "D15") (pinfunction "MII1_RXD2_D15") (pintype "bidirectional"))
    )
    (net (code "7") (name "/BT_HCI_TX") (class "Default")
      (node (ref "R15") (pin "2") (pinfunction "2_2") (pintype "passive"))
      (node (ref "U1") (pin "D14") (pinfunction "MII1_RXD3_D14") (pintype "bidirectional"))
    )
    (net (code "8") (name "/B_UART0_RX") (class "Default")
      (node (ref "J4") (pin "4") (pinfunction "4_4") (pintype "bidirectional"))
      (node (ref "R80") (pin "2") (pinfunction "2_2") (pintype "passive"))
      (node (ref "U10") (pin "2") (pinfunction "1A_2") (pintype "input"))
    )
    (net (code "9") (name "/B_UART0_TX") (class "Default")
      (node (ref "J4") (pin "5") (pinfunction "5_5") (pintype "bidirectional"))
      (node (ref "U10") (pin "3") (pinfunction "2Y_3") (pintype "output"))
    )
    (net (code "10") (name "/CEC") (class "Default")
      (node (ref "D12") (pin "1") (pinfunction "2_1") (pintype "bidirectional"))
      (node (ref "J6") (pin "13") (pinfunction "CE_REMOTE_13") (pintype "bidirectional"))
      (node (ref "R106") (pin "2") (pinfunction "2_2") (pintype "passive"))
      (node (ref "U11") (pin "17") (pinfunction "CEC_17") (pintype "bidirectional"))
    )
    (net (code "11") (name "/CK_N") (class "Default")
      (node (ref "J6") (pin "12") (pinfunction "CK-_12") (pintype "bidirectional"))
      (node (ref "U11") (pin "21") (pinfunction "TXCM_21") (pintype "bidirectional"))
      (node (ref "U14") (pin "5") (pinfunction "5_5") (pintype "bidirectional"))
      (node (ref "U14") (pin "6") (pinfunction "6_6") (pintype "bidirectional"))
    )
    (net (code "12") (name "/CK_P") (class "Default")
      (node (ref "J6") (pin "10") (pinfunction "CK+_10") (pintype "bidirectional"))
      (node (ref "U11") (pin "22") (pinfunction "TXCP_22") (pintype "bidirectional"))
      (node (ref "U14") (pin "4") (pinfunction "4_4") (pintype "bidirectional"))
      (node (ref "U14") (pin "7") (pinfunction "7_7") (pintype "bidirectional"))
    )
    (net (code "13") (name "/CLKOUT2") (class "Default")
      (node (ref "C37") (pin "2") (pinfunction "2_2") (pintype "passive"))
      (node (ref "R79") (pin "2") (pinfunction "2_2") (pintype "passive"))
      (node (ref "R96") (pin "2") (pinfunction "2_2") (pintype "passive"))
      (node (ref "U4") (pin "36") (pinfunction "EXT_32K_36") (pintype "bidirectional"))
    )
    (net (code "14") (name "/COILA+") (class "Default")
      (node (ref "J5") (pin "1") (pinfunction "P$1_1") (pintype "bidirectional"))
      (node (ref "U12") (pin "21") (pinfunction "OUT1B_21") (pintype "bidirectional"))
    )
    (net (code "15") (name "/COILA-") (class "Default")
      (node (ref "J5") (pin "2") (pinfunction "P$2_2") (pintype "bidirectional"))
      (node (ref "U12") (pin "24") (pinfunction "OUT1A_24") (pintype "bidirectional"))
    )
    (net (code "16") (name "/COILB+") (class "Default")
      (node (ref "J5") (pin "4") (pinfunction "P$4_4") (pintype "bidirectional"))
      (node (ref "U12") (pin "1") (pinfunction "OUT2B_1") (pintype "bidirectional"))
    )
    (net (code "17") (name "/COILB-") (class "Default")
      (node (ref "J5") (pin "3") (pinfunction "P$3_3") (pintype "bidirectional"))
      (node (ref "U12") (pin "26") (pinfunction "OUT2A_26") (pintype "bidirectional"))
    )
    (net (code "18") (name "/CUR_REF") (class "Default")
      (node (ref "U12") (pin "17") (pinfunction "REF_17") (pintype "bidirectional"))
      (node (ref "VR1") (pin "2") (pinfunction "3_2") (pintype "passive"))
    )
    (net (code "19") (name "/D0_N") (class "Default")
      (node (ref "J6") (pin "9") (pinfunction "D0-_9") (pintype "bidirectional"))
      (node (ref "U11") (pin "24") (pinfunction "TX0M_24") (pintype "bidirectional"))
      (node (ref "U14") (pin "2") (pinfunction "2_2") (pintype "bidirectional"))
      (node (ref "U14") (pin "9") (pinfunction "9_9") (pintype "bidirectional"))
    )
    (net (code "20") (name "/D0_P") (class "Default")
      (node (ref "J6") (pin "7") (pinfunction "D0+_7") (pintype "bidirectional"))
      (node (ref "U11") (pin "25") (pinfunction "TX0P_25") (pintype "bidirectional"))
      (node (ref "U14") (pin "1") (pinfunction "1_1") (pintype "bidirectional"))
      (node (ref "U14") (pin "10") (pinfunction "10_10") (pintype "bidirectional"))
    )
    (net (code "21") (name "/D1_N") (class "Default")
      (node (ref "J6") (pin "6") (pinfunction "D1-_6") (pintype "bidirectional"))
      (node (ref "U11") (pin "26") (pinfunction "TX1M_26") (pintype "bidirectional"))
      (node (ref "U13") (pin "5") (pinfunction "5_5") (pintype "bidirectional"))
      (node (ref "U13") (pin "6") (pinfunction "6_6") (pintype "bidirectional"))
    )
    (net (code "22") (name "/D1_P") (class "Default")
      (node (ref "J6") (pin "4") (pinfunction "D1+_4") (pintype "bidirectional"))
      (node (ref "U11") (pin "27") (pinfunction "TX1P_27") (pintype "bidirectional"))
      (node (ref "U13") (pin "4") (pinfunction "4_4") (pintype "bidirectional"))
      (node (ref "U13") (pin "7") (pinfunction "7_7") (pintype "bidirectional"))
    )
    (net (code "23") (name "/D2_N") (class "Default")
      (node (ref "J6") (pin "3") (pinfunction "D2-_3") (pintype "bidirectional"))
      (node (ref "U11") (pin "29") (pinfunction "TX2M_29") (pintype "bidirectional"))
      (node (ref "U13") (pin "2") (pinfunction "2_2") (pintype "bidirectional"))
      (node (ref "U13") (pin "9") (pinfunction "9_9") (pintype "bidirectional"))
    )
    (net (code "24") (name "/D2_P") (class "Default")
      (node (ref "J6") (pin "1") (pinfunction "D2+_1") (pintype "bidirectional"))
      (node (ref "U11") (pin "30") (pinfunction "TX2P_30") (pintype "bidirectional"))
      (node (ref "U13") (pin "1") (pinfunction "1_1") (pintype "bidirectional"))
      (node (ref "U13") (pin "10") (pinfunction "10_10") (pintype "bidirectional"))
    )
    (net (code "25") (name "/DDC_SCL") (class "Default")
      (node (ref "D9") (pin "1") (pinfunction "2_1") (pintype "bidirectional"))
      (node (ref "J6") (pin "15") (pinfunction "DDC_CLK_15") (pintype "bidirectional"))
      (node (ref "R102") (pin "2") (pinfunction "2_2") (pintype "passive"))
      (node (ref "R104") (pin "2") (pinfunction "2_2") (pintype "passive"))
    )
    (net (code "26") (name "/DDC_SDA") (class "Default")
      (node (ref "D10") (pin "1") (pinfunction "2_1") (pintype "bidirectional"))
      (node (ref "J6") (pin "16") (pinfunction "DDC_DATA_16") (pintype "bidirectional"))
      (node (ref "R103") (pin "2") (pinfunction "2_2") (pintype "passive"))
      (node (ref "R105") (pin "2") (pinfunction "2_2") (pintype "passive"))
    )
    (net (code "27") (name "/DIR(GPIO23)") (class "Default")
      (node (ref "R88") (pin "1") (pinfunction "1_1") (pintype "passive"))
      (node (ref "U1") (pin "P5") (pinfunction "GPMC_AD9_P5") (pintype "bidirectional"))
      (node (ref "U12") (pin "19") (pinfunction "DIR_19") (pintype "input"))
    )
    (net (code "28") (name "/EEPROM_WP") (class "Default")
      (node (ref "TP10") (pin "P1") (pinfunction "T_P1") (pintype "bidirectional"))
      (node (ref "U1") (pin "M2") (pinfunction "EEPROM_WP_M2") (pintype "bidirectional"))
      (node (ref "U1") (pin "N3") (pinfunction "GPMC_BEN0_CLE_N3") (pintype "bidirectional"))
    )
    (net (code "29") (name "/ENABLE(GPIO46)") (class "Default")
      (node (ref "R94") (pin "1") (pinfunction "1_1") (pintype "passive"))
      (node (ref "U1") (pin "T6") (pinfunction "GPMC_AD14_T6") (pintype "bidirectional"))
      (node (ref "U12") (pin "2") (pinfunction "ENABLE_2") (pintype "input"))
    )
    (net (code "30") (name "/HDMI_1V2") (class "Default")
      (node (ref "C61") (pin "2") (pinfunction "2_2") (pintype "passive"))
      (node (ref "C62") (pin "2") (pinfunction "2_2") (pintype "passive"))
      (node (ref "C63") (pin "2") (pinfunction "2_2") (pintype "passive"))
      (node (ref "C64") (pin "2") (pinfunction "2_2") (pintype "passive"))
      (node (ref "C65") (pin "2") (pinfunction "2_2") (pintype "passive"))
      (node (ref "C66") (pin "2") (pinfunction "2_2") (pintype "passive"))
      (node (ref "C82") (pin "2") (pinfunction "2_2") (pintype "passive"))
      (node (ref "C83") (pin "2") (pinfunction "2_2") (pintype "passive"))
      (node (ref "L10") (pin "2") (pinfunction "2_2") (pintype "passive"))
      (node (ref "R113") (pin "2") (pinfunction "2_2") (pintype "passive"))
      (node (ref "TP18") (pin "T") (pinfunction "T_T") (pintype "bidirectional"))
      (node (ref "U11") (pin "18") (pinfunction "PVCC12_18") (pintype "bidirectional"))
      (node (ref "U11") (pin "23") (pinfunction "AVCC12_23") (pintype "bidirectional"))
      (node (ref "U11") (pin "28") (pinfunction "DVDD12_28") (pintype "bidirectional"))
      (node (ref "U11") (pin "35") (pinfunction "IVDD12_35") (pintype "bidirectional"))
      (node (ref "U11") (pin "56") (pinfunction "IVDD12_56") (pintype "bidirectional"))
      (node (ref "U11") (pin "8") (pinfunction "IVDD12_8") (pintype "bidirectional"))
    )
    (net (code "31") (name "/HDMI_3V3") (class "Default")
      (node (ref "C69") (pin "2") (pinfunction "2_2") (pintype "passive"))
      (node (ref "C71") (pin "2") (pinfunction "2_2") (pintype "passive"))
      (node (ref "C73") (pin "2") (pinfunction "2_2") (pintype "passive"))
      (node (ref "C76") (pin "2") (pinfunction "2_2") (pintype "passive"))
      (node (ref "C77") (pin "2") (pinfunction "2_2") (pintype "passive"))
      (node (ref "C78") (pin "2") (pinfunction "2_2") (pintype "passive"))
      (node (ref "L8") (pin "2") (pinfunction "2_2") (pintype "passive"))
      (node (ref "R100") (pin "1") (pinfunction "1_1") (pintype "passive"))
      (node (ref "R106") (pin "1") (pinfunction "1_1") (pintype "passive"))
      (node (ref "R109") (pin "2") (pinfunction "2_2") (pintype "passive"))
      (node (ref "R81") (pin "1") (pinfunction "1_1") (pintype "passive"))
      (node (ref "R82") (pin "1") (pinfunction "1_1") (pintype "passive"))
      (node (ref "R83") (pin "1") (pinfunction "1_1") (pintype "passive"))
      (node (ref "R84") (pin "1") (pinfunction "1_1") (pintype "passive"))
      (node (ref "TP19") (pin "T") (pinfunction "T_T") (pintype "bidirectional"))
      (node (ref "U11") (pin "1") (pinfunction "OVDD_1") (pintype "bidirectional"))
      (node (ref "U11") (pin "13") (pinfunction "OVDD33_13") (pintype "bidirectional"))
      (node (ref "U11") (pin "19") (pinfunction "PVCC33_19") (pintype "bidirectional"))
      (node (ref "U11") (pin "34") (pinfunction "OVDD_34") (pintype "bidirectional"))
      (node (ref "U11") (pin "9") (pinfunction "VCC33_9") (pintype "bidirectional"))
      (node (ref "U16") (pin "1") (pinfunction "EN_1") (pintype "bidirectional"))
    )
    (net (code "32") (name "/HDMI_5V") (class "Default")
      (node (ref "C84") (pin "2") (pinfunction "2_2") (pintype "passive"))
      (node (ref "D11") (pin "1") (pinfunction "2_1") (pintype "bidirectional"))
      (node (ref "F1") (pin "2") (pinfunction "2_2") (pintype "bidirectional"))
      (node (ref "J6") (pin "18") (pinfunction "+5V_18") (pintype "bidirectional"))
      (node (ref "R104") (pin "1") (pinfunction "1_1") (pintype "passive"))
      (node (ref "R105") (pin "1") (pinfunction "1_1") (pintype "passive"))
      (node (ref "TP20") (pin "T") (pinfunction "T_T") (pintype "bidirectional"))
    )
    (net (code "33") (name "/HDMI_AUDBCLK") (class "Default")
      (node (ref "U1") (pin "A1") (pinfunction "MCASP0_ACLKX_A1") (pintype "bidirectional"))
      (node (ref "U11") (pin "7") (pinfunction "SCK/MCLK_7") (pintype "bidirectional"))
    )
    (net (code "34") (name "/HDMI_AUDDOUT") (class "Default")
      (node (ref "R85") (pin "1") (pinfunction "1_1") (pintype "passive"))
      (node (ref "R86") (pin "1") (pinfunction "1_1") (pintype "passive"))
      (node (ref "U1") (pin "B1") (pinfunction "MCASP0_AHCLKR_B1") (pintype "bidirectional"))
    )
    (net (code "35") (name "/HDMI_AUDWCLK") (class "Default")
      (node (ref "U1") (pin "A2") (pinfunction "MCASP0_FSX_A2") (pintype "bidirectional"))
      (node (ref "U11") (pin "6") (pinfunction "WS_6") (pintype "bidirectional"))
    )
    (net (code "36") (name "/HDMI_INT") (class "Default")
      (node (ref "R83") (pin "2") (pinfunction "2_2") (pintype "passive"))
      (node (ref "U1") (pin "T15") (pinfunction "GPMC_A9_T15") (pintype "bidirectional"))
      (node (ref "U11") (pin "10") (pinfunction "INT_10") (pintype "bidirectional"))
    )
    (net (code "37") (name "/HPD") (class "Default")
      (node (ref "D13") (pin "1") (pinfunction "2_1") (pintype "bidirectional"))
      (node (ref "J6") (pin "19") (pinfunction "HPD_19") (pintype "bidirectional"))
      (node (ref "R107") (pin "2") (pinfunction "2_2") (pintype "passive"))
      (node (ref "U11") (pin "14") (pinfunction "HPD_14") (pintype "bidirectional"))
    )
    (net (code "38") (name "/I2C0_SCL") (class "Default")
      (node (ref "R1") (pin "1") (pinfunction "1_1") (pintype "passive"))
      (node (ref "U1") (pin "C10") (pinfunction "I2C0_SCL_C10") (pintype "bidirectional"))
      (node (ref "U1") (pin "D10") (pinfunction "PMIC_SCL_D10") (pintype "bidirectional"))
    )
    (net (code "39") (name "/I2C0_SDA") (class "Default")
      (node (ref "R2") (pin "1") (pinfunction "1_1") (pintype "passive"))
      (node (ref "U1") (pin "C11") (pinfunction "I2C0_SDA_C11") (pintype "bidirectional"))
      (node (ref "U1") (pin "D11") (pinfunction "PMIC_SDA_D11") (pintype "bidirectional"))
    )
    (net (code "40") (name "/I2C2_SCL") (class "Default")
      (node (ref "R82") (pin "2") (pinfunction "2_2") (pintype "passive"))
      (node (ref "U1") (pin "A10") (pinfunction "UART1_RTSN_A10") (pintype "bidirectional"))
      (node (ref "U11") (pin "12") (pinfunction "PCSCL_12") (pintype "bidirectional"))
    )
    (net (code "41") (name "/I2C2_SDA") (class "Default")
      (node (ref "R81") (pin "2") (pinfunction "2_2") (pintype "passive"))
      (node (ref "U1") (pin "B10") (pinfunction "UART1_CTSN_B10") (pintype "bidirectional"))
      (node (ref "U11") (pin "11") (pinfunction "PCSDA_11") (pintype "bidirectional"))
    )
    (net (code "42") (name "/LCD_DATA0") (class "Default")
      (node (ref "C60") (pin "1") (pinfunction "1_1") (pintype "passive"))
      (node (ref "R50") (pin "2") (pinfunction "2_2") (pintype "passive"))
      (node (ref "U1") (pin "G3") (pinfunction "LCD_DATA0_G3") (pintype "bidirectional"))
      (node (ref "U11") (pin "58") (pinfunction "D3_58") (pintype "bidirectional"))
    )
    (net (code "43") (name "/LCD_DATA1") (class "Default")
      (node (ref "C59") (pin "1") (pinfunction "1_1") (pintype "passive"))
      (node (ref "R49") (pin "2") (pinfunction "2_2") (pintype "passive"))
      (node (ref "U1") (pin "G2") (pinfunction "LCD_DATA1_G2") (pintype "bidirectional"))
      (node (ref "U11") (pin "57") (pinfunction "D4_57") (pintype "bidirectional"))
    )
    (net (code "44") (name "/LCD_DATA2") (class "Default")
      (node (ref "C58") (pin "1") (pinfunction "1_1") (pintype "passive"))
      (node (ref "R46") (pin "2") (pinfunction "2_2") (pintype "passive"))
      (node (ref "U1") (pin "G1") (pinfunction "LCD_DATA2_G1") (pintype "bidirectional"))
      (node (ref "U11") (pin "55") (pinfunction "D5_55") (pintype "bidirectional"))
    )
    (net (code "45") (name "/LCD_DATA3") (class "Default")
      (node (ref "C57") (pin "1") (pinfunction "1_1") (pintype "passive"))
      (node (ref "R45") (pin "1") (pinfunction "1_1") (pintype "passive"))
      (node (ref "U1") (pin "H3") (pinfunction "LCD_DATA3_H3") (pintype "bidirectional"))
      (node (ref "U11") (pin "54") (pinfunction "D6_54") (pintype "bidirectional"))
    )
    (net (code "46") (name "/LCD_DATA4") (class "Default")
      (node (ref "C55") (pin "1") (pinfunction "1_1") (pintype "passive"))
      (node (ref "R44") (pin "1") (pinfunction "1_1") (pintype "passive"))
      (node (ref "U1") (pin "H2") (pinfunction "LCD_DATA4_H2") (pintype "bidirectional"))
      (node (ref "U11") (pin "53") (pinfunction "D7_53") (pintype "bidirectional"))
    )
    (net (code "47") (name "/LCD_DATA5") (class "Default")
      (node (ref "C46") (pin "1") (pinfunction "1_1") (pintype "passive"))
      (node (ref "R43") (pin "2") (pinfunction "2_2") (pintype "passive"))
      (node (ref "U1") (pin "H1") (pinfunction "LCD_DATA5_H1") (pintype "bidirectional"))
      (node (ref "U11") (pin "49") (pinfunction "D10_49") (pintype "bidirectional"))
    )
    (net (code "48") (name "/LCD_DATA6") (class "Default")
      (node (ref "C45") (pin "1") (pinfunction "1_1") (pintype "passive"))
      (node (ref "R42") (pin "2") (pinfunction "2_2") (pintype "passive"))
      (node (ref "U1") (pin "J3") (pinfunction "LCD_DATA6_J3") (pintype "bidirectional"))
      (node (ref "U11") (pin "48") (pinfunction "D11_48") (pintype "bidirectional"))
    )
    (net (code "49") (name "/LCD_DATA7") (class "Default")
      (node (ref "C43") (pin "1") (pinfunction "1_1") (pintype "passive"))
      (node (ref "R41") (pin "2") (pinfunction "2_2") (pintype "passive"))
      (node (ref "U1") (pin "J2") (pinfunction "LCD_DATA7_J2") (pintype "bidirectional"))
      (node (ref "U11") (pin "47") (pinfunction "D12_47") (pintype "bidirectional"))
    )
    (net (code "50") (name "/LCD_DATA8") (class "Default")
      (node (ref "C42") (pin "1") (pinfunction "1_1") (pintype "passive"))
      (node (ref "R40") (pin "2") (pinfunction "2_2") (pintype "passive"))
      (node (ref "U1") (pin "J1") (pinfunction "LCD_DATA8_J1") (pintype "bidirectional"))
      (node (ref "U11") (pin "46") (pinfunction "D13_46") (pintype "bidirectional"))
    )
    (net (code "51") (name "/LCD_DATA9") (class "Default")
      (node (ref "C41") (pin "1") (pinfunction "1_1") (pintype "passive"))
      (node (ref "R39") (pin "2") (pinfunction "2_2") (pintype "passive"))
      (node (ref "U1") (pin "K3") (pinfunction "LCD_DATA9_K3") (pintype "bidirectional"))
      (node (ref "U11") (pin "45") (pinfunction "D14_45") (pintype "bidirectional"))
    )
    (net (code "52") (name "/LCD_DATA10") (class "Default")
      (node (ref "C39") (pin "1") (pinfunction "1_1") (pintype "passive"))
      (node (ref "R38") (pin "2") (pinfunction "2_2") (pintype "passive"))
      (node (ref "U1") (pin "K2") (pinfunction "LCD_DATA10_K2") (pintype "bidirectional"))
      (node (ref "U11") (pin "44") (pinfunction "D15_44") (pintype "bidirectional"))
    )
    (net (code "53") (name "/LCD_DATA11") (class "Default")
      (node (ref "C54") (pin "1") (pinfunction "1_1") (pintype "passive"))
      (node (ref "R37") (pin "2") (pinfunction "2_2") (pintype "passive"))
      (node (ref "U1") (pin "K1") (pinfunction "LCD_DATA11_K1") (pintype "bidirectional"))
      (node (ref "U11") (pin "40") (pinfunction "D19_40") (pintype "bidirectional"))
    )
    (net (code "54") (name "/LCD_DATA12") (class "Default")
      (node (ref "C52") (pin "1") (pinfunction "1_1") (pintype "passive"))
      (node (ref "R36") (pin "2") (pinfunction "2_2") (pintype "passive"))
      (node (ref "U1") (pin "L3") (pinfunction "LCD_DATA12_L3") (pintype "bidirectional"))
      (node (ref "U11") (pin "39") (pinfunction "D20_39") (pintype "bidirectional"))
    )
    (net (code "55") (name "/LCD_DATA13") (class "Default")
      (node (ref "C50") (pin "1") (pinfunction "1_1") (pintype "passive"))
      (node (ref "R35") (pin "2") (pinfunction "2_2") (pintype "passive"))
      (node (ref "U1") (pin "L2") (pinfunction "LCD_DATA13_L2") (pintype "bidirectional"))
      (node (ref "U11") (pin "38") (pinfunction "D21_38") (pintype "bidirectional"))
    )
    (net (code "56") (name "/LCD_DATA14") (class "Default")
      (node (ref "C49") (pin "1") (pinfunction "1_1") (pintype "passive"))
      (node (ref "R34") (pin "1") (pinfunction "1_1") (pintype "passive"))
      (node (ref "U1") (pin "L1") (pinfunction "LCD_DATA14_L1") (pintype "bidirectional"))
      (node (ref "U11") (pin "37") (pinfunction "D22_37") (pintype "bidirectional"))
    )
    (net (code "57") (name "/LCD_DATA15") (class "Default")
      (node (ref "C47") (pin "1") (pinfunction "1_1") (pintype "passive"))
      (node (ref "R33") (pin "2") (pinfunction "2_2") (pintype "passive"))
      (node (ref "U1") (pin "M3") (pinfunction "LCD_DATA15_M3") (pintype "bidirectional"))
      (node (ref "U11") (pin "36") (pinfunction "D23_36") (pintype "bidirectional"))
    )
    (net (code "58") (name "/LCD_DE") (class "Default")
      (node (ref "R118") (pin "2") (pinfunction "2_2") (pintype "passive"))
      (node (ref "U11") (pin "62") (pinfunction "DE_62") (pintype "bidirectional"))
    )
    (net (code "59") (name "/LCD_HSYNC") (class "Default")
      (node (ref "R117") (pin "2") (pinfunction "2_2") (pintype "passive"))
      (node (ref "U11") (pin "63") (pinfunction "HSYNC_63") (pintype "bidirectional"))
    )
    (net (code "60") (name "/LCD_PCLK") (class "Default")
      (node (ref "R115") (pin "2") (pinfunction "2_2") (pintype "passive"))
      (node (ref "U11") (pin "51") (pinfunction "PCLK_51") (pintype "bidirectional"))
    )
    (net (code "61") (name "/LCD_VSYNC") (class "Default")
      (node (ref "R116") (pin "2") (pinfunction "2_2") (pintype "passive"))
      (node (ref "U11") (pin "64") (pinfunction "VSYNC_64") (pintype "bidirectional"))
    )
    (net (code "62") (name "/LDO_PGOOD") (class "Default")
      (node (ref "TP22") (pin "TP") (pinfunction "TP_TP") (pintype "input"))
      (node (ref "U1") (pin "N4") (pinfunction "PMIC_LDO_PGOOD_N4") (pintype "output"))
      (node (ref "U1") (pin "N5") (pinfunction "RTC_PWRONRSTN_N5") (pintype "bidirectional"))
    )
    (net (code "63") (name "/MMC0_CD") (class "Default")
      (node (ref "J3") (pin "9") (pinfunction "CDN_9") (pintype "bidirectional"))
      (node (ref "R75") (pin "1") (pinfunction "1_1") (pintype "passive"))
      (node (ref "U1") (pin "C14") (pinfunction "SPI0_CS1_C14") (pintype "bidirectional"))
    )
    (net (code "64") (name "/MMC0_CLK") (class "Default")
      (node (ref "C40") (pin "2") (pinfunction "2_2") (pintype "passive"))
      (node (ref "J3") (pin "5") (pinfunction "SCLK_5") (pintype "bidirectional"))
      (node (ref "R71") (pin "1") (pinfunction "1_1") (pintype "passive"))
      (node (ref "R95") (pin "1") (pinfunction "1_1") (pintype "passive"))
    )
    (net (code "65") (name "/MMC0_CMD") (class "Default")
      (node (ref "J3") (pin "3") (pinfunction "DI_3") (pintype "bidirectional"))
      (node (ref "R68") (pin "1") (pinfunction "1_1") (pintype "passive"))
      (node (ref "U1") (pin "B16") (pinfunction "MMC0_CMD_B16") (pintype "bidirectional"))
    )
    (net (code "66") (name "/MMC0_DAT0") (class "Default")
      (node (ref "J3") (pin "7") (pinfunction "DO_7") (pintype "bidirectional"))
      (node (ref "R72") (pin "1") (pinfunction "1_1") (pintype "passive"))
      (node (ref "U1") (pin "A16") (pinfunction "MMC0_DAT0_A16") (pintype "bidirectional"))
    )
    (net (code "67") (name "/MMC0_DAT1") (class "Default")
      (node (ref "J3") (pin "8") (pinfunction "DATA1_8") (pintype "bidirectional"))
      (node (ref "R73") (pin "1") (pinfunction "1_1") (pintype "passive"))
      (node (ref "U1") (pin "A15") (pinfunction "MMC0_DAT1_A15") (pintype "bidirectional"))
    )
    (net (code "68") (name "/MMC0_DAT2") (class "Default")
      (node (ref "J3") (pin "1") (pinfunction "DATA2_1") (pintype "bidirectional"))
      (node (ref "R67") (pin "1") (pinfunction "1_1") (pintype "passive"))
      (node (ref "U1") (pin "C16") (pinfunction "MMC0_DAT2_C16") (pintype "bidirectional"))
    )
    (net (code "69") (name "/MMC0_DAT3") (class "Default")
      (node (ref "J3") (pin "2") (pinfunction "CS_2") (pintype "bidirectional"))
      (node (ref "R74") (pin "1") (pinfunction "1_1") (pintype "passive"))
      (node (ref "U1") (pin "C15") (pinfunction "MMC0_DAT3_C15") (pintype "bidirectional"))
    )
    (net (code "70") (name "/MS1(GPIO27)") (class "Default")
      (node (ref "R89") (pin "1") (pinfunction "1_1") (pintype "passive"))
      (node (ref "U1") (pin "T5") (pinfunction "GPMC_AD11_T5") (pintype "bidirectional"))
      (node (ref "U12") (pin "9") (pinfunction "MS1_9") (pintype "input"))
    )
    (net (code "71") (name "/MS2(GPIO44)") (class "Default")
      (node (ref "R90") (pin "1") (pinfunction "1_1") (pintype "passive"))
      (node (ref "U1") (pin "P6") (pinfunction "GPMC_AD12_P6") (pintype "bidirectional"))
      (node (ref "U12") (pin "10") (pinfunction "MS2_10") (pintype "input"))
    )
    (net (code "72") (name "/MS3(GPIO45)") (class "Default")
      (node (ref "R91") (pin "1") (pinfunction "1_1") (pintype "passive"))
      (node (ref "U1") (pin "R6") (pinfunction "GPMC_AD13_R6") (pintype "bidirectional"))
      (node (ref "U12") (pin "11") (pinfunction "MS3_11") (pintype "input"))
    )
    (net (code "73") (name "/OSC0_GND") (class "Default")
      (node (ref "C12") (pin "2") (pinfunction "2_2") (pintype "passive"))
      (node (ref "C13") (pin "2") (pinfunction "2_2") (pintype "passive"))
      (node (ref "U1") (pin "N15") (pinfunction "OSC0_GND_N15") (pintype "bidirectional"))
    )
    (net (code "74") (name "/OSC0_IN") (class "Default")
      (node (ref "C12") (pin "1") (pinfunction "1_1") (pintype "passive"))
      (node (ref "R55") (pin "2") (pinfunction "2_2") (pintype "passive"))
      (node (ref "U1") (pin "P16") (pinfunction "OSC0_IN_P16") (pintype "bidirectional"))
      (node (ref "Y1") (pin "P$2") (pinfunction "2_P$2") (pintype "passive"))
    )
    (net (code "75") (name "/OSC0_OUT") (class "Default")
      (node (ref "C13") (pin "1") (pinfunction "1_1") (pintype "passive"))
      (node (ref "R55") (pin "1") (pinfunction "1_1") (pintype "passive"))
      (node (ref "U1") (pin "N16") (pinfunction "OSC0_OUT_N16") (pintype "bidirectional"))
      (node (ref "Y1") (pin "P$1") (pinfunction "1_P$1") (pintype "passive"))
    )
    (net (code "76") (name "/OSC1_GND") (class "Default")
      (node (ref "C14") (pin "2") (pinfunction "2_2") (pintype "passive"))
      (node (ref "C15") (pin "2") (pinfunction "2_2") (pintype "passive"))
      (node (ref "U1") (pin "B5") (pinfunction "OSC1_GND_B5") (pintype "bidirectional"))
    )
    (net (code "77") (name "/OSC1_IN") (class "Default")
      (node (ref "C14") (pin "1") (pinfunction "1_1") (pintype "passive"))
      (node (ref "R56") (pin "2") (pinfunction "2_2") (pintype "passive"))
      (node (ref "U1") (pin "A6") (pinfunction "OSC1_IN_A6") (pintype "bidirectional"))
      (node (ref "X1") (pin "2") (pinfunction "2_2") (pintype "passive"))
    )
    (net (code "78") (name "/OSC1_OUT") (class "Default")
      (node (ref "C15") (pin "1") (pinfunction "1_1") (pintype "passive"))
      (node (ref "R56") (pin "1") (pinfunction "1_1") (pintype "passive"))
      (node (ref "U1") (pin "A5") (pinfunction "OSC1_OUT_A5") (pintype "bidirectional"))
      (node (ref "X1") (pin "1") (pinfunction "1_1") (pintype "passive"))
    )
    (net (code "79") (name "/PMIC_INT") (class "Default")
      (node (ref "TP24") (pin "TP") (pinfunction "TP_TP") (pintype "input"))
      (node (ref "U1") (pin "D4") (pinfunction "EXTINTN_D4") (pintype "bidirectional"))
      (node (ref "U1") (pin "E4") (pinfunction "PMIC_NINT_E4") (pintype "output"))
    )
    (net (code "80") (name "/PMIC_MUX_IN") (class "Default")
      (node (ref "R69") (pin "1") (pinfunction "1_1") (pintype "passive"))
      (node (ref "R70") (pin "2") (pinfunction "2_2") (pintype "passive"))
      (node (ref "U1") (pin "N13") (pinfunction "PMIC_MUX_IN_N13") (pintype "bidirectional"))
    )
    (net (code "81") (name "/PMIC_NRESET") (class "Default")
      (node (ref "TP34") (pin "P1") (pinfunction "T_P1") (pintype "bidirectional"))
      (node (ref "U1") (pin "M13") (pinfunction "PMIC_NRESET_M13") (pintype "bidirectional"))
    )
    (net (code "82") (name "/PMIC_NWAKEUP") (class "Default")
      (node (ref "TP23") (pin "TP") (pinfunction "TP_TP") (pintype "input"))
      (node (ref "U1") (pin "L4") (pinfunction "PMIC_NWAKEUP_L4") (pintype "output"))
      (node (ref "U1") (pin "M4") (pinfunction "EXT_WAKEUP_M4") (pintype "bidirectional"))
    )
    (net (code "83") (name "/PMIC_PGOOD") (class "Default")
      (node (ref "U1") (pin "N12") (pinfunction "PMIC_PGOOD_N12") (pintype "output"))
      (node (ref "U1") (pin "P11") (pinfunction "PWRONRSTN_P11") (pintype "bidirectional"))
      (node (ref "U2") (pin "2") (pinfunction "A_2") (pintype "bidirectional"))
    )
    (net (code "84") (name "/PWR_BUT") (class "Default")
      (node (ref "SW1") (pin "3") (pinfunction "3_3") (pintype "bidirectional"))
      (node (ref "SW1") (pin "4") (pinfunction "4_4") (pintype "bidirectional"))
      (node (ref "U1") (pin "T11") (pinfunction "PMIC_PB_IN_T11") (pintype "bidirectional"))
    )
    (net (code "85") (name "/PWR_EN") (class "Default")
      (node (ref "TP21") (pin "TP") (pinfunction "TP_TP") (pintype "input"))
      (node (ref "U1") (pin "N10") (pinfunction "PMIC_POWER_EN_N10") (pintype "output"))
      (node (ref "U1") (pin "N11") (pinfunction "PMIC_PWR_EN_N11") (pintype "input"))
    )
    (net (code "86") (name "/RESET(GPIO26)") (class "Default")
      (node (ref "R93") (pin "1") (pinfunction "1_1") (pintype "passive"))
      (node (ref "U1") (pin "R5") (pinfunction "GPMC_AD10_R5") (pintype "bidirectional"))
      (node (ref "U12") (pin "12") (pinfunction "RESET_12") (pintype "input"))
    )
    (net (code "87") (name "/SLEEP(GPIO47)") (class "Default")
      (node (ref "R92") (pin "1") (pinfunction "1_1") (pintype "passive"))
      (node (ref "U1") (pin "P7") (pinfunction "GPMC_AD15_P7") (pintype "bidirectional"))
      (node (ref "U12") (pin "14") (pinfunction "SLEEP_14") (pintype "input"))
    )
    (net (code "88") (name "/STEP(GPIO22)") (class "Default")
      (node (ref "R87") (pin "1") (pinfunction "1_1") (pintype "passive"))
      (node (ref "U1") (pin "T4") (pinfunction "GPMC_AD8_T4") (pintype "bidirectional"))
      (node (ref "U12") (pin "16") (pinfunction "STEP_16") (pintype "input"))
    )
    (net (code "89") (name "/SYS_RESETN") (class "Default")
      (node (ref "R31") (pin "1") (pinfunction "1_1") (pintype "passive"))
      (node (ref "R32") (pin "2") (pinfunction "2_2") (pintype "passive"))
      (node (ref "TP26") (pin "P$1") (pinfunction "TP_P$1") (pintype "bidirectional"))
      (node (ref "U1") (pin "R11") (pinfunction "WARMRSTN_R11") (pintype "bidirectional"))
    )
    (net (code "90") (name "/TO_NEOPIXEL") (class "Default")
      (node (ref "U1") (pin "B2") (pinfunction "MCASP0_AXR0_B2") (pintype "bidirectional"))
      (node (ref "U9") (pin "2") (pinfunction "A_2") (pintype "bidirectional"))
    )
    (net (code "91") (name "/UART0_RX") (class "Default")
      (node (ref "U1") (pin "A12") (pinfunction "UART0_RXD_A12") (pintype "bidirectional"))
      (node (ref "U10") (pin "6") (pinfunction "1Y_6") (pintype "output"))
    )
    (net (code "92") (name "/UART0_TX") (class "Default")
      (node (ref "U1") (pin "B12") (pinfunction "UART0_TXD_B12") (pintype "bidirectional"))
      (node (ref "U10") (pin "5") (pinfunction "2A_5") (pintype "input"))
    )
    (net (code "93") (name "/USB0_DM") (class "Default")
      (node (ref "IC1") (pin "1") (pinfunction "D+_1") (pintype "bidirectional"))
      (node (ref "J1") (pin "2") (pinfunction "DM_2") (pintype "bidirectional"))
      (node (ref "U1") (pin "K16") (pinfunction "USB0_DM_K16") (pintype "bidirectional"))
    )
    (net (code "94") (name "/USB0_DP") (class "Default")
      (node (ref "IC1") (pin "2") (pinfunction "D-_2") (pintype "bidirectional"))
      (node (ref "J1") (pin "3") (pinfunction "DP_3") (pintype "bidirectional"))
      (node (ref "U1") (pin "K15") (pinfunction "USB0_DP_K15") (pintype "bidirectional"))
    )
    (net (code "95") (name "/USB0_ID") (class "Default")
      (node (ref "IC1") (pin "3") (pinfunction "ID_3") (pintype "bidirectional"))
      (node (ref "J1") (pin "4") (pinfunction "ID_4") (pintype "bidirectional"))
      (node (ref "U1") (pin "K14") (pinfunction "USB0_ID_K14") (pintype "bidirectional"))
    )
    (net (code "96") (name "/USB1_DM") (class "Default")
      (node (ref "IC2") (pin "1") (pinfunction "D+_1") (pintype "bidirectional"))
      (node (ref "JP2") (pin "2") (pinfunction "D-_2") (pintype "bidirectional"))
      (node (ref "U1") (pin "L16") (pinfunction "USB1_DM_L16") (pintype "bidirectional"))
    )
    (net (code "97") (name "/USB1_DP") (class "Default")
      (node (ref "IC2") (pin "2") (pinfunction "D-_2") (pintype "bidirectional"))
      (node (ref "JP2") (pin "3") (pinfunction "D+_3") (pintype "bidirectional"))
      (node (ref "U1") (pin "L15") (pinfunction "USB1_DP_L15") (pintype "bidirectional"))
    )
    (net (code "98") (name "/USB1_DRVVBUS") (class "Default")
      (node (ref "R62") (pin "1") (pinfunction "1_1") (pintype "passive"))
      (node (ref "U1") (pin "M14") (pinfunction "USB1_DRVVBUS_M14") (pintype "bidirectional"))
      (node (ref "U7") (pin "4") (pinfunction "EN#_4") (pintype "bidirectional"))
    )
    (net (code "99") (name "/USB1_ID") (class "Default")
      (node (ref "R64") (pin "2") (pinfunction "2_2") (pintype "passive"))
      (node (ref "U1") (pin "L14") (pinfunction "USB1_ID_L14") (pintype "bidirectional"))
    )
    (net (code "100") (name "/USB1_OC#") (class "Default")
      (node (ref "R63") (pin "2") (pinfunction "2_2") (pintype "passive"))
      (node (ref "U7") (pin "5") (pinfunction "OC#_5") (pintype "bidirectional"))
    )
    (net (code "101") (name "/USB1_VBUS") (class "Default")
      (node (ref "L4") (pin "2") (pinfunction "2_2") (pintype "passive"))
      (node (ref "U1") (pin "M15") (pinfunction "USB1_VBUS_M15") (pintype "bidirectional"))
    )
    (net (code "102") (name "/USR0") (class "Default")
      (node (ref "D5") (pin "+") (pinfunction "+_+") (pintype "passive"))
      (node (ref "U1") (pin "P13") (pinfunction "GPMC_A5_P13") (pintype "bidirectional"))
    )
    (net (code "103") (name "/USR1") (class "Default")
      (node (ref "D6") (pin "+") (pinfunction "+_+") (pintype "passive"))
      (node (ref "U1") (pin "T14") (pinfunction "GPMC_A6_T14") (pintype "bidirectional"))
    )
    (net (code "104") (name "/USR2") (class "Default")
      (node (ref "D7") (pin "+") (pinfunction "+_+") (pintype "passive"))
      (node (ref "U1") (pin "R14") (pinfunction "GPMC_A7_R14") (pintype "bidirectional"))
    )
    (net (code "105") (name "/USR3") (class "Default")
      (node (ref "D8") (pin "+") (pinfunction "+_+") (pintype "passive"))
      (node (ref "U1") (pin "P14") (pinfunction "GPMC_A8_P14") (pintype "bidirectional"))
    )
    (net (code "106") (name "/VREFN") (class "Default")
      (node (ref "R66") (pin "1") (pinfunction "1_1") (pintype "passive"))
      (node (ref "U1") (pin "B9") (pinfunction "VREFN_B9") (pintype "bidirectional"))
    )
    (net (code "107") (name "/VREFP") (class "Default")
      (node (ref "C25") (pin "1") (pinfunction "1_1") (pintype "passive"))
      (node (ref "C27") (pin "1") (pinfunction "1_1") (pintype "passive"))
      (node (ref "R65") (pin "1") (pinfunction "1_1") (pintype "passive"))
      (node (ref "U1") (pin "B7") (pinfunction "VREFP_B7") (pintype "bidirectional"))
    )
    (net (code "108") (name "/WIFI_LED(GPIO3_01)") (class "Default")
      (node (ref "Q1") (pin "1") (pinfunction "G_1") (pintype "passive"))
      (node (ref "U1") (pin "F14") (pinfunction "MII1_CRS_F14") (pintype "bidirectional"))
    )
    (net (code "109") (name "/WL_EN") (class "Default")
      (node (ref "Q2") (pin "1") (pinfunction "G_1") (pintype "passive"))
      (node (ref "U1") (pin "H16") (pinfunction "MII1_TX_CLK_H16") (pintype "bidirectional"))
      (node (ref "U4") (pin "40") (pinfunction "WLAN_EN_40") (pintype "bidirectional"))
    )
    (net (code "110") (name "/WL_IRQ") (class "Default")
      (node (ref "R29") (pin "2") (pinfunction "2_2") (pintype "passive"))
      (node (ref "U1") (pin "H14") (pinfunction "MII1_TXD1_H14") (pintype "bidirectional"))
    )
    (net (code "111") (name "/WL_SDIO_CLK") (class "Default")
      (node (ref "R22") (pin "2") (pinfunction "2_2") (pintype "passive"))
      (node (ref "R9") (pin "2") (pinfunction "2_2") (pintype "passive"))
      (node (ref "U1") (pin "D16") (pinfunction "MII1_RXD1_D16") (pintype "bidirectional"))
    )
    (net (code "112") (name "/WL_SDIO_CMD") (class "Default")
      (node (ref "R10") (pin "2") (pinfunction "2_2") (pintype "passive"))
      (node (ref "R19") (pin "2") (pinfunction "2_2") (pintype "passive"))
      (node (ref "U1") (pin "G14") (pinfunction "MII1_TX_EN_G14") (pintype "bidirectional"))
    )
    (net (code "113") (name "/WL_SDIO_D0") (class "Default")
      (node (ref "R25") (pin "2") (pinfunction "2_2") (pintype "passive"))
      (node (ref "R4") (pin "2") (pinfunction "2_2") (pintype "passive"))
      (node (ref "U1") (pin "F16") (pinfunction "MII1_RX_DV_F16") (pintype "bidirectional"))
    )
    (net (code "114") (name "/WL_SDIO_D1") (class "Default")
      (node (ref "R26") (pin "2") (pinfunction "2_2") (pintype "passive"))
      (node (ref "R6") (pin "2") (pinfunction "2_2") (pintype "passive"))
      (node (ref "U1") (pin "G15") (pinfunction "MII1_TXD3_G15") (pintype "bidirectional"))
    )
    (net (code "115") (name "/WL_SDIO_D2") (class "Default")
      (node (ref "R27") (pin "2") (pinfunction "2_2") (pintype "passive"))
      (node (ref "R7") (pin "2") (pinfunction "2_2") (pintype "passive"))
      (node (ref "U1") (pin "G16") (pinfunction "MII1_TXD2_G16") (pintype "bidirectional"))
    )
    (net (code "116") (name "/WL_SDIO_D3") (class "Default")
      (node (ref "R28") (pin "2") (pinfunction "2_2") (pintype "passive"))
      (node (ref "R8") (pin "2") (pinfunction "2_2") (pintype "passive"))
      (node (ref "U1") (pin "F15") (pinfunction "MII1_COL_F15") (pintype "bidirectional"))
    )
    (net (code "117") (name "1.8V-WIFI") (class "Default")
      (node (ref "C2") (pin "1") (pinfunction "1_1") (pintype "passive"))
      (node (ref "C7") (pin "2") (pinfunction "2_2") (pintype "passive"))
      (node (ref "C8") (pin "1") (pinfunction "1_1") (pintype "passive"))
      (node (ref "L1") (pin "2") (pinfunction "2_2") (pintype "passive"))
      (node (ref "R10") (pin "1") (pinfunction "1_1") (pintype "passive"))
      (node (ref "R30") (pin "1") (pinfunction "1_1") (pintype "passive"))
      (node (ref "R4") (pin "1") (pinfunction "1_1") (pintype "passive"))
      (node (ref "R6") (pin "1") (pinfunction "1_1") (pintype "passive"))
      (node (ref "R7") (pin "1") (pinfunction "1_1") (pintype "passive"))
      (node (ref "R8") (pin "1") (pinfunction "1_1") (pintype "passive"))
      (node (ref "R9") (pin "1") (pinfunction "1_1") (pintype "passive"))
      (node (ref "U4") (pin "38") (pinfunction "VIO_38") (pintype "bidirectional"))
    )
    (net (code "118") (name "3.3V-WIFI") (class "Default")
      (node (ref "C3") (pin "2") (pinfunction "2_2") (pintype "passive"))
      (node (ref "C4") (pin "1") (pinfunction "1_1") (pintype "passive"))
      (node (ref "C5") (pin "1") (pinfunction "1_1") (pintype "passive"))
      (node (ref "C6") (pin "1") (pinfunction "1_1") (pintype "passive"))
      (node (ref "L2") (pin "2") (pinfunction "2_2") (pintype "passive"))
      (node (ref "R11") (pin "2") (pinfunction "2_2") (pintype "passive"))
      (node (ref "R12") (pin "2") (pinfunction "2_2") (pintype "passive"))
      (node (ref "R5") (pin "2") (pinfunction "2_2") (pintype "passive"))
      (node (ref "U4") (pin "46") (pinfunction "VBAT_IN1_46") (pintype "bidirectional"))
      (node (ref "U4") (pin "47") (pinfunction "VBAT_IN2_47") (pintype "bidirectional"))
    )
    (net (code "119") (name "AGND") (class "Default")
      (node (ref "C25") (pin "2") (pinfunction "2_2") (pintype "passive"))
      (node (ref "C27") (pin "2") (pinfunction "2_2") (pintype "passive"))
      (node (ref "C28") (pin "2") (pinfunction "2_2") (pintype "passive"))
      (node (ref "R66") (pin "2") (pinfunction "2_2") (pintype "passive"))
      (node (ref "U1") (pin "A9") (pinfunction "AGND_ADC_A9") (pintype "bidirectional"))
    )
    (net (code "120") (name "CGND") (class "Default")
      (node (ref "C11") (pin "2") (pinfunction "2_2") (pintype "passive"))
      (node (ref "J1") (pin "P1") (pinfunction "GND_P1") (pintype "bidirectional"))
      (node (ref "J1") (pin "P3") (pinfunction "GND_P3") (pintype "bidirectional"))
      (node (ref "J1") (pin "P4") (pinfunction "GND_P4") (pintype "bidirectional"))
      (node (ref "J1") (pin "P5") (pinfunction "GND_P5") (pintype "bidirectional"))
      (node (ref "J1") (pin "P6") (pinfunction "GND_P6") (pintype "bidirectional"))
      (node (ref "J3") (pin "G2") (pinfunction "G2_G2") (pintype "bidirectional"))
      (node (ref "J3") (pin "G3") (pinfunction "G3_G3") (pintype "bidirectional"))
      (node (ref "J3") (pin "G4") (pinfunction "G3_G4") (pintype "bidirectional"))
      (node (ref "J6") (pin "PAD") (pinfunction "SHELL1_PAD") (pintype "bidirectional"))
      (node (ref "J6") (pin "PAD1") (pinfunction "SHELL2_PAD1") (pintype "bidirectional"))
      (node (ref "J6") (pin "PAD2") (pinfunction "SHELL3_PAD2") (pintype "bidirectional"))
      (node (ref "J6") (pin "PAD3") (pinfunction "SHELL4_PAD3") (pintype "bidirectional"))
      (node (ref "JP2") (pin "SG1") (pinfunction "GND_SG1") (pintype "bidirectional"))
      (node (ref "JP2") (pin "SG2") (pinfunction "GND_SG2") (pintype "bidirectional"))
      (node (ref "MGT1") (pin "P$1") (pinfunction "P$1_P$1") (pintype "bidirectional"))
      (node (ref "MGT2") (pin "P$1") (pinfunction "P$1_P$1") (pintype "bidirectional"))
      (node (ref "MGT3") (pin "P$1") (pinfunction "P$1_P$1") (pintype "bidirectional"))
      (node (ref "MGT4") (pin "P$1") (pinfunction "P$1_P$1") (pintype "bidirectional"))
      (node (ref "R48") (pin "2") (pinfunction "2_2") (pintype "passive"))
    )
    (net (code "121") (name "GND") (class "Default")
      (node (ref "ANT1") (pin "GND1") (pinfunction "GND1_GND1") (pintype "bidirectional"))
      (node (ref "ANT1") (pin "GND2") (pinfunction "GND2_GND2") (pintype "bidirectional"))
      (node (ref "ANT2") (pin "GND1") (pinfunction "GND1_GND1") (pintype "bidirectional"))
      (node (ref "ANT2") (pin "GND2") (pinfunction "GND2_GND2") (pintype "bidirectional"))
      (node (ref "C1") (pin "-") (pinfunction "-_-") (pintype "passive"))
      (node (ref "C11") (pin "1") (pinfunction "1_1") (pintype "passive"))
      (node (ref "C16") (pin "1") (pinfunction "1_1") (pintype "passive"))
      (node (ref "C17") (pin "1") (pinfunction "1_1") (pintype "passive"))
      (node (ref "C18") (pin "1") (pinfunction "1_1") (pintype "passive"))
      (node (ref "C2") (pin "2") (pinfunction "2_2") (pintype "passive"))
      (node (ref "C20") (pin "2") (pinfunction "2_2") (pintype "passive"))
      (node (ref "C21") (pin "1") (pinfunction "1_1") (pintype "passive"))
      (node (ref "C22") (pin "1") (pinfunction "1_1") (pintype "passive"))
      (node (ref "C24") (pin "2") (pinfunction "2_2") (pintype "passive"))
      (node (ref "C26") (pin "1") (pinfunction "1_1") (pintype "passive"))
      (node (ref "C29") (pin "1") (pinfunction "1_1") (pintype "passive"))
      (node (ref "C3") (pin "1") (pinfunction "1_1") (pintype "passive"))
      (node (ref "C30") (pin "1") (pinfunction "1_1") (pintype "passive"))
      (node (ref "C31") (pin "2") (pinfunction "2_2") (pintype "passive"))
      (node (ref "C32") (pin "2") (pinfunction "2_2") (pintype "passive"))
      (node (ref "C33") (pin "1") (pinfunction "1_1") (pintype "passive"))
      (node (ref "C34") (pin "2") (pinfunction "2_2") (pintype "passive"))
      (node (ref "C35") (pin "1") (pinfunction "1_1") (pintype "passive"))
      (node (ref "C36") (pin "1") (pinfunction "1_1") (pintype "passive"))
      (node (ref "C37") (pin "1") (pinfunction "1_1") (pintype "passive"))
      (node (ref "C38") (pin "1") (pinfunction "1_1") (pintype "passive"))
      (node (ref "C39") (pin "2") (pinfunction "2_2") (pintype "passive"))
      (node (ref "C4") (pin "2") (pinfunction "2_2") (pintype "passive"))
      (node (ref "C40") (pin "1") (pinfunction "1_1") (pintype "passive"))
      (node (ref "C41") (pin "2") (pinfunction "2_2") (pintype "passive"))
      (node (ref "C42") (pin "2") (pinfunction "2_2") (pintype "passive"))
      (node (ref "C43") (pin "2") (pinfunction "2_2") (pintype "passive"))
      (node (ref "C44") (pin "1") (pinfunction "1_1") (pintype "passive"))
      (node (ref "C45") (pin "2") (pinfunction "2_2") (pintype "passive"))
      (node (ref "C46") (pin "2") (pinfunction "2_2") (pintype "passive"))
      (node (ref "C47") (pin "2") (pinfunction "2_2") (pintype "passive"))
      (node (ref "C48") (pin "-") (pinfunction "-_-") (pintype "passive"))
      (node (ref "C49") (pin "2") (pinfunction "2_2") (pintype "passive"))
      (node (ref "C5") (pin "2") (pinfunction "2_2") (pintype "passive"))
      (node (ref "C50") (pin "2") (pinfunction "2_2") (pintype "passive"))
      (node (ref "C51") (pin "-") (pinfunction "-_-") (pintype "passive"))
      (node (ref "C52") (pin "2") (pinfunction "2_2") (pintype "passive"))
      (node (ref "C53") (pin "2") (pinfunction "2_2") (pintype "passive"))
      (node (ref "C54") (pin "2") (pinfunction "2_2") (pintype "passive"))
      (node (ref "C55") (pin "2") (pinfunction "2_2") (pintype "passive"))
      (node (ref "C57") (pin "2") (pinfunction "2_2") (pintype "passive"))
      (node (ref "C58") (pin "2") (pinfunction "2_2") (pintype "passive"))
      (node (ref "C59") (pin "2") (pinfunction "2_2") (pintype "passive"))
      (node (ref "C6") (pin "2") (pinfunction "2_2") (pintype "passive"))
      (node (ref "C60") (pin "2") (pinfunction "2_2") (pintype "passive"))
      (node (ref "C61") (pin "1") (pinfunction "1_1") (pintype "passive"))
      (node (ref "C62") (pin "1") (pinfunction "1_1") (pintype "passive"))
      (node (ref "C63") (pin "1") (pinfunction "1_1") (pintype "passive"))
      (node (ref "C64") (pin "1") (pinfunction "1_1") (pintype "passive"))
      (node (ref "C65") (pin "1") (pinfunction "1_1") (pintype "passive"))
      (node (ref "C66") (pin "1") (pinfunction "1_1") (pintype "passive"))
      (node (ref "C67") (pin "2") (pinfunction "2_2") (pintype "passive"))
      (node (ref "C69") (pin "1") (pinfunction "1_1") (pintype "passive"))
      (node (ref "C7") (pin "1") (pinfunction "1_1") (pintype "passive"))
      (node (ref "C70") (pin "1") (pinfunction "1_1") (pintype "passive"))
      (node (ref "C71") (pin "1") (pinfunction "1_1") (pintype "passive"))
      (node (ref "C72") (pin "1") (pinfunction "1_1") (pintype "passive"))
      (node (ref "C73") (pin "1") (pinfunction "1_1") (pintype "passive"))
      (node (ref "C74") (pin "1") (pinfunction "1_1") (pintype "passive"))
      (node (ref "C75") (pin "1") (pinfunction "1_1") (pintype "passive"))
      (node (ref "C76") (pin "1") (pinfunction "1_1") (pintype "passive"))
      (node (ref "C77") (pin "1") (pinfunction "1_1") (pintype "passive"))
      (node (ref "C78") (pin "1") (pinfunction "1_1") (pintype "passive"))
      (node (ref "C79") (pin "1") (pinfunction "1_1") (pintype "passive"))
      (node (ref "C8") (pin "2") (pinfunction "2_2") (pintype "passive"))
      (node (ref "C80") (pin "1") (pinfunction "1_1") (pintype "passive"))
      (node (ref "C81") (pin "1") (pinfunction "1_1") (pintype "passive"))
      (node (ref "C82") (pin "1") (pinfunction "1_1") (pintype "passive"))
      (node (ref "C83") (pin "1") (pinfunction "1_1") (pintype "passive"))
      (node (ref "C84") (pin "1") (pinfunction "1_1") (pintype "passive"))
      (node (ref "D10") (pin "2") (pinfunction "1_2") (pintype "bidirectional"))
      (node (ref "D11") (pin "2") (pinfunction "1_2") (pintype "bidirectional"))
      (node (ref "D12") (pin "2") (pinfunction "1_2") (pintype "bidirectional"))
      (node (ref "D13") (pin "2") (pinfunction "1_2") (pintype "bidirectional"))
      (node (ref "D9") (pin "2") (pinfunction "1_2") (pintype "bidirectional"))
      (node (ref "IC1") (pin "4") (pinfunction "GND_4") (pintype "bidirectional"))
      (node (ref "IC2") (pin "4") (pinfunction "GND_4") (pintype "bidirectional"))
      (node (ref "J1") (pin "5") (pinfunction "GND_5") (pintype "bidirectional"))
      (node (ref "J2") (pin "-") (pinfunction "-_-") (pintype "bidirectional"))
      (node (ref "J2") (pin "CDN") (pinfunction "CDN_CDN") (pintype "bidirectional"))
      (node (ref "J3") (pin "6") (pinfunction "VSS_6") (pintype "bidirectional"))
      (node (ref "J4") (pin "1") (pinfunction "1_1") (pintype "bidirectional"))
      (node (ref "J6") (pin "11") (pinfunction "CK_SHIELD_11") (pintype "bidirectional"))
      (node (ref "J6") (pin "17") (pinfunction "GND_17") (pintype "bidirectional"))
      (node (ref "J6") (pin "2") (pinfunction "D2_SHIELD_2") (pintype "bidirectional"))
      (node (ref "J6") (pin "5") (pinfunction "D1_SHIELD_5") (pintype "bidirectional"))
      (node (ref "J6") (pin "8") (pinfunction "D0_SHIELD_8") (pintype "bidirectional"))
      (node (ref "J7") (pin "1") (pinfunction "P$1_1") (pintype "bidirectional"))
      (node (ref "J7") (pin "4") (pinfunction "P$4_4") (pintype "bidirectional"))
      (node (ref "J8") (pin "1") (pinfunction "P$1_1") (pintype "bidirectional"))
      (node (ref "J8") (pin "4") (pinfunction "P$4_4") (pintype "bidirectional"))
      (node (ref "JP2") (pin "4") (pinfunction "GND_4") (pintype "bidirectional"))
      (node (ref "Q1") (pin "2") (pinfunction "S_2") (pintype "passive"))
      (node (ref "Q2") (pin "2") (pinfunction "S_2") (pintype "passive"))
      (node (ref "Q3") (pin "2") (pinfunction "S_2") (pintype "passive"))
      (node (ref "R101") (pin "1") (pinfunction "1_1") (pintype "passive"))
      (node (ref "R107") (pin "1") (pinfunction "1_1") (pintype "passive"))
      (node (ref "R108") (pin "2") (pinfunction "2_2") (pintype "passive"))
      (node (ref "R109") (pin "1") (pinfunction "1_1") (pintype "passive"))
      (node (ref "R110") (pin "1") (pinfunction "1_1") (pintype "passive"))
      (node (ref "R111") (pin "1") (pinfunction "1_1") (pintype "passive"))
      (node (ref "R114") (pin "1") (pinfunction "1_1") (pintype "passive"))
      (node (ref "R119") (pin "2") (pinfunction "2_2") (pintype "passive"))
      (node (ref "R18") (pin "2") (pinfunction "2_2") (pintype "passive"))
      (node (ref "R3") (pin "2") (pinfunction "2_2") (pintype "passive"))
      (node (ref "R32") (pin "1") (pinfunction "1_1") (pintype "passive"))
      (node (ref "R33") (pin "1") (pinfunction "1_1") (pintype "passive"))
      (node (ref "R35") (pin "1") (pinfunction "1_1") (pintype "passive"))
      (node (ref "R36") (pin "1") (pinfunction "1_1") (pintype "passive"))
      (node (ref "R37") (pin "1") (pinfunction "1_1") (pintype "passive"))
      (node (ref "R38") (pin "1") (pinfunction "1_1") (pintype "passive"))
      (node (ref "R39") (pin "1") (pinfunction "1_1") (pintype "passive"))
      (node (ref "R40") (pin "1") (pinfunction "1_1") (pintype "passive"))
      (node (ref "R41") (pin "1") (pinfunction "1_1") (pintype "passive"))
      (node (ref "R42") (pin "1") (pinfunction "1_1") (pintype "passive"))
      (node (ref "R43") (pin "1") (pinfunction "1_1") (pintype "passive"))
      (node (ref "R46") (pin "1") (pinfunction "1_1") (pintype "passive"))
      (node (ref "R48") (pin "1") (pinfunction "1_1") (pintype "passive"))
      (node (ref "R49") (pin "1") (pinfunction "1_1") (pintype "passive"))
      (node (ref "R50") (pin "1") (pinfunction "1_1") (pintype "passive"))
      (node (ref "R51") (pin "2") (pinfunction "2_2") (pintype "passive"))
      (node (ref "R52") (pin "2") (pinfunction "2_2") (pintype "passive"))
      (node (ref "R53") (pin "2") (pinfunction "2_2") (pintype "passive"))
      (node (ref "R54") (pin "2") (pinfunction "2_2") (pintype "passive"))
      (node (ref "R58") (pin "1") (pinfunction "1_1") (pintype "passive"))
      (node (ref "R61") (pin "1") (pinfunction "1_1") (pintype "passive"))
      (node (ref "R62") (pin "2") (pinfunction "2_2") (pintype "passive"))
      (node (ref "R64") (pin "1") (pinfunction "1_1") (pintype "passive"))
      (node (ref "R70") (pin "1") (pinfunction "1_1") (pintype "passive"))
      (node (ref "R77") (pin "1") (pinfunction "1_1") (pintype "passive"))
      (node (ref "R79") (pin "1") (pinfunction "1_1") (pintype "passive"))
      (node (ref "R80") (pin "1") (pinfunction "1_1") (pintype "passive"))
      (node (ref "R94") (pin "2") (pinfunction "2_2") (pintype "passive"))
      (node (ref "R98") (pin "2") (pinfunction "2_2") (pintype "passive"))
      (node (ref "R99") (pin "1") (pinfunction "1_1") (pintype "passive"))
      (node (ref "SW1") (pin "1") (pinfunction "1_1") (pintype "bidirectional"))
      (node (ref "SW1") (pin "2") (pinfunction "2_2") (pintype "bidirectional"))
      (node (ref "SW2") (pin "1") (pinfunction "1_1") (pintype "bidirectional"))
      (node (ref "SW2") (pin "2") (pinfunction "2_2") (pintype "bidirectional"))
      (node (ref "TP8") (pin "P$1") (pinfunction "TP_P$1") (pintype "bidirectional"))
      (node (ref "U1") (pin "D8") (pinfunction "DGND_D8") (pintype "bidirectional"))
      (node (ref "U1") (pin "D9") (pinfunction "DGND_D9") (pintype "bidirectional"))
      (node (ref "U1") (pin "E10") (pinfunction "DGND_E10") (pintype "bidirectional"))
      (node (ref "U1") (pin "E11") (pinfunction "DGND_E11") (pintype "bidirectional"))
      (node (ref "U1") (pin "E12") (pinfunction "DGND_E12") (pintype "bidirectional"))
      (node (ref "U1") (pin "E5") (pinfunction "DGND_E5") (pintype "bidirectional"))
      (node (ref "U1") (pin "E6") (pinfunction "DGND_E6") (pintype "bidirectional"))
      (node (ref "U1") (pin "E7") (pinfunction "DGND_E7") (pintype "bidirectional"))
      (node (ref "U1") (pin "E8") (pinfunction "DGND_E8") (pintype "bidirectional"))
      (node (ref "U1") (pin "E9") (pinfunction "DGND_E9") (pintype "bidirectional"))
      (node (ref "U1") (pin "F12") (pinfunction "DGND_F12") (pintype "bidirectional"))
      (node (ref "U1") (pin "F5") (pinfunction "DGND_F5") (pintype "bidirectional"))
      (node (ref "U1") (pin "G12") (pinfunction "DGND_G12") (pintype "bidirectional"))
      (node (ref "U1") (pin "G5") (pinfunction "DGND_G5") (pintype "bidirectional"))
      (node (ref "U1") (pin "H12") (pinfunction "DGND_H12") (pintype "bidirectional"))
      (node (ref "U1") (pin "H13") (pinfunction "DGND_H13") (pintype "bidirectional"))
      (node (ref "U1") (pin "H4") (pinfunction "DGND_H4") (pintype "bidirectional"))
      (node (ref "U1") (pin "H5") (pinfunction "DGND_H5") (pintype "bidirectional"))
      (node (ref "U1") (pin "J12") (pinfunction "DGND_J12") (pintype "bidirectional"))
      (node (ref "U1") (pin "J13") (pinfunction "DGND_J13") (pintype "bidirectional"))
      (node (ref "U1") (pin "J4") (pinfunction "DGND_J4") (pintype "bidirectional"))
      (node (ref "U1") (pin "J5") (pinfunction "DGND_J5") (pintype "bidirectional"))
      (node (ref "U1") (pin "K12") (pinfunction "DGND_K12") (pintype "bidirectional"))
      (node (ref "U1") (pin "K5") (pinfunction "DGND_K5") (pintype "bidirectional"))
      (node (ref "U1") (pin "L12") (pinfunction "DGND_L12") (pintype "bidirectional"))
      (node (ref "U1") (pin "L5") (pinfunction "DGND_L5") (pintype "bidirectional"))
      (node (ref "U1") (pin "M10") (pinfunction "DGND_M10") (pintype "bidirectional"))
      (node (ref "U1") (pin "M11") (pinfunction "DGND_M11") (pintype "bidirectional"))
      (node (ref "U1") (pin "M12") (pinfunction "DGND_M12") (pintype "bidirectional"))
      (node (ref "U1") (pin "M5") (pinfunction "DGND_M5") (pintype "bidirectional"))
      (node (ref "U1") (pin "M6") (pinfunction "DGND_M6") (pintype "bidirectional"))
      (node (ref "U1") (pin "M7") (pinfunction "DGND_M7") (pintype "bidirectional"))
      (node (ref "U1") (pin "M8") (pinfunction "DGND_M8") (pintype "bidirectional"))
      (node (ref "U1") (pin "M9") (pinfunction "DGND_M9") (pintype "bidirectional"))
      (node (ref "U1") (pin "N8") (pinfunction "DGND_N8") (pintype "bidirectional"))
      (node (ref "U1") (pin "N9") (pinfunction "DGND_N9") (pintype "bidirectional"))
      (node (ref "U10") (pin "1") (pinfunction "*1OE_1") (pintype "input"))
      (node (ref "U10") (pin "4") (pinfunction "GND_4") (pintype "power_in"))
      (node (ref "U11") (pin "41") (pinfunction "D18_41") (pintype "bidirectional"))
      (node (ref "U11") (pin "42") (pinfunction "D17_42") (pintype "bidirectional"))
      (node (ref "U11") (pin "43") (pinfunction "D16_43") (pintype "bidirectional"))
      (node (ref "U11") (pin "50") (pinfunction "D9_50") (pintype "bidirectional"))
      (node (ref "U11") (pin "52") (pinfunction "D8_52") (pintype "bidirectional"))
      (node (ref "U11") (pin "59") (pinfunction "D2_59") (pintype "bidirectional"))
      (node (ref "U11") (pin "60") (pinfunction "D1_60") (pintype "bidirectional"))
      (node (ref "U11") (pin "61") (pinfunction "D0_61") (pintype "bidirectional"))
      (node (ref "U11") (pin "65") (pinfunction "GND_65") (pintype "bidirectional"))
      (node (ref "U12") (pin "18") (pinfunction "GND_18") (pintype "power_in"))
      (node (ref "U12") (pin "3") (pinfunction "GND_3") (pintype "power_in"))
      (node (ref "U12") (pin "PAD") (pinfunction "GND_PAD_PAD") (pintype "power_in"))
      (node (ref "U13") (pin "3") (pinfunction "3_3") (pintype "bidirectional"))
      (node (ref "U13") (pin "8") (pinfunction "8_8") (pintype "bidirectional"))
      (node (ref "U14") (pin "3") (pinfunction "3_3") (pintype "bidirectional"))
      (node (ref "U14") (pin "8") (pinfunction "8_8") (pintype "bidirectional"))
      (node (ref "U16") (pin "2") (pinfunction "GND_2") (pintype "bidirectional"))
      (node (ref "U2") (pin "3") (pinfunction "GND_3") (pintype "bidirectional"))
      (node (ref "U4") (pin "1") (pinfunction "GND1_1") (pintype "bidirectional"))
      (node (ref "U4") (pin "15") (pinfunction "GND4_15") (pintype "bidirectional"))
      (node (ref "U4") (pin "16") (pinfunction "GND5_16") (pintype "bidirectional"))
      (node (ref "U4") (pin "17") (pinfunction "GND6_17") (pintype "bidirectional"))
      (node (ref "U4") (pin "19") (pinfunction "GND7_19") (pintype "bidirectional"))
      (node (ref "U4") (pin "20") (pinfunction "GND8_20") (pintype "bidirectional"))
      (node (ref "U4") (pin "23") (pinfunction "GND9_23") (pintype "bidirectional"))
      (node (ref "U4") (pin "24") (pinfunction "GND10_24") (pintype "bidirectional"))
      (node (ref "U4") (pin "28") (pinfunction "GND11_28") (pintype "bidirectional"))
      (node (ref "U4") (pin "29") (pinfunction "GND12_29") (pintype "bidirectional"))
      (node (ref "U4") (pin "30") (pinfunction "GND13_30") (pintype "bidirectional"))
      (node (ref "U4") (pin "31") (pinfunction "GND14_31") (pintype "bidirectional"))
      (node (ref "U4") (pin "33") (pinfunction "GND15_33") (pintype "bidirectional"))
      (node (ref "U4") (pin "34") (pinfunction "GND16_34") (pintype "bidirectional"))
      (node (ref "U4") (pin "35") (pinfunction "GND17_35") (pintype "bidirectional"))
      (node (ref "U4") (pin "37") (pinfunction "GND18_37") (pintype "bidirectional"))
      (node (ref "U4") (pin "39") (pinfunction "GND19_39") (pintype "bidirectional"))
      (node (ref "U4") (pin "44") (pinfunction "GND20_44") (pintype "bidirectional"))
      (node (ref "U4") (pin "45") (pinfunction "GND21_45") (pintype "bidirectional"))
      (node (ref "U4") (pin "48") (pinfunction "GND22_48") (pintype "bidirectional"))
      (node (ref "U4") (pin "49") (pinfunction "GND23_49") (pintype "bidirectional"))
      (node (ref "U4") (pin "54") (pinfunction "GND24_54") (pintype "bidirectional"))
      (node (ref "U4") (pin "55") (pinfunction "GND25_55") (pintype "bidirectional"))
      (node (ref "U4") (pin "59") (pinfunction "GND26_59") (pintype "bidirectional"))
      (node (ref "U4") (pin "61") (pinfunction "GND27_61") (pintype "bidirectional"))
      (node (ref "U4") (pin "63") (pinfunction "GND28_63") (pintype "bidirectional"))
      (node (ref "U4") (pin "64") (pinfunction "GND29_64") (pintype "bidirectional"))
      (node (ref "U4") (pin "7") (pinfunction "GND2_7") (pintype "bidirectional"))
      (node (ref "U4") (pin "9") (pinfunction "GND3_9") (pintype "bidirectional"))
      (node (ref "U4") (pin "G1") (pinfunction "G1_G1") (pintype "bidirectional"))
      (node (ref "U4") (pin "G10") (pinfunction "G10_G10") (pintype "bidirectional"))
      (node (ref "U4") (pin "G11") (pinfunction "G11_G11") (pintype "bidirectional"))
      (node (ref "U4") (pin "G12") (pinfunction "G12_G12") (pintype "bidirectional"))
      (node (ref "U4") (pin "G13") (pinfunction "G13_G13") (pintype "bidirectional"))
      (node (ref "U4") (pin "G14") (pinfunction "G14_G14") (pintype "bidirectional"))
      (node (ref "U4") (pin "G15") (pinfunction "G15_G15") (pintype "bidirectional"))
      (node (ref "U4") (pin "G16") (pinfunction "G16_G16") (pintype "bidirectional"))
      (node (ref "U4") (pin "G17") (pinfunction "G17_G17") (pintype "bidirectional"))
      (node (ref "U4") (pin "G18") (pinfunction "G18_G18") (pintype "bidirectional"))
      (node (ref "U4") (pin "G19") (pinfunction "G19_G19") (pintype "bidirectional"))
      (node (ref "U4") (pin "G2") (pinfunction "G2_G2") (pintype "bidirectional"))
      (node (ref "U4") (pin "G20") (pinfunction "G20_G20") (pintype "bidirectional"))
      (node (ref "U4") (pin "G21") (pinfunction "G21_G21") (pintype "bidirectional"))
      (node (ref "U4") (pin "G22") (pinfunction "G22_G22") (pintype "bidirectional"))
      (node (ref "U4") (pin "G23") (pinfunction "G23_G23") (pintype "bidirectional"))
      (node (ref "U4") (pin "G24") (pinfunction "G24_G24") (pintype "bidirectional"))
      (node (ref "U4") (pin "G25") (pinfunction "G25_G25") (pintype "bidirectional"))
      (node (ref "U4") (pin "G26") (pinfunction "G26_G26") (pintype "bidirectional"))
      (node (ref "U4") (pin "G27") (pinfunction "G27_G27") (pintype "bidirectional"))
      (node (ref "U4") (pin "G28") (pinfunction "G28_G28") (pintype "bidirectional"))
      (node (ref "U4") (pin "G29") (pinfunction "G29_G29") (pintype "bidirectional"))
      (node (ref "U4") (pin "G3") (pinfunction "G3_G3") (pintype "bidirectional"))
      (node (ref "U4") (pin "G30") (pinfunction "G30_G30") (pintype "bidirectional"))
      (node (ref "U4") (pin "G31") (pinfunction "G31_G31") (pintype "bidirectional"))
      (node (ref "U4") (pin "G32") (pinfunction "G32_G32") (pintype "bidirectional"))
      (node (ref "U4") (pin "G33") (pinfunction "G33_G33") (pintype "bidirectional"))
      (node (ref "U4") (pin "G34") (pinfunction "G34_G34") (pintype "bidirectional"))
      (node (ref "U4") (pin "G35") (pinfunction "G35_G35") (pintype "bidirectional"))
      (node (ref "U4") (pin "G36") (pinfunction "G36_G36") (pintype "bidirectional"))
      (node (ref "U4") (pin "G4") (pinfunction "G4_G4") (pintype "bidirectional"))
      (node (ref "U4") (pin "G5") (pinfunction "G5_G5") (pintype "bidirectional"))
      (node (ref "U4") (pin "G6") (pinfunction "G6_G6") (pintype "bidirectional"))
      (node (ref "U4") (pin "G7") (pinfunction "G7_G7") (pintype "bidirectional"))
      (node (ref "U4") (pin "G8") (pinfunction "G8_G8") (pintype "bidirectional"))
      (node (ref "U4") (pin "G9") (pinfunction "G9_G9") (pintype "bidirectional"))
      (node (ref "U5") (pin "1") (pinfunction "GND_1") (pintype "bidirectional"))
      (node (ref "U6") (pin "1") (pinfunction "GND_1") (pintype "bidirectional"))
      (node (ref "U7") (pin "1") (pinfunction "GND_1") (pintype "bidirectional"))
      (node (ref "U7") (pin "9") (pinfunction "THERMAL_9") (pintype "bidirectional"))
      (node (ref "U8") (pin "2") (pinfunction "GND_2") (pintype "bidirectional"))
      (node (ref "U9") (pin "1") (pinfunction "~{OE}_1") (pintype "bidirectional"))
      (node (ref "U9") (pin "3") (pinfunction "GND_3") (pintype "bidirectional"))
      (node (ref "VR1") (pin "1") (pinfunction "1_1") (pintype "passive"))
    )
    (net (code "122") (name "Net-(ANT1-PadD)") (class "Default")
      (node (ref "ANT1") (pin "D") (pinfunction "D_D") (pintype "bidirectional"))
      (node (ref "C9") (pin "1") (pinfunction "1_1") (pintype "passive"))
    )
    (net (code "123") (name "Net-(ANT2-PadD)") (class "Default")
      (node (ref "ANT2") (pin "D") (pinfunction "D_D") (pintype "bidirectional"))
      (node (ref "C10") (pin "1") (pinfunction "1_1") (pintype "passive"))
    )
    (net (code "124") (name "Net-(C23-Pad1)") (class "Default")
      (node (ref "C23") (pin "1") (pinfunction "1_1") (pintype "passive"))
      (node (ref "R59") (pin "1") (pinfunction "1_1") (pintype "passive"))
      (node (ref "R60") (pin "2") (pinfunction "2_2") (pintype "passive"))
    )
    (net (code "125") (name "Net-(C81-Pad2)") (class "Default")
      (node (ref "C81") (pin "2") (pinfunction "2_2") (pintype "passive"))
      (node (ref "F1") (pin "1") (pinfunction "1_1") (pintype "bidirectional"))
      (node (ref "L9") (pin "2") (pinfunction "2_2") (pintype "passive"))
    )
    (net (code "126") (name "Net-(D1-Pad+)") (class "Default")
      (node (ref "D1") (pin "+") (pinfunction "+_+") (pintype "passive"))
      (node (ref "R5") (pin "1") (pinfunction "1_1") (pintype "passive"))
    )
    (net (code "127") (name "Net-(D2-Pad+)") (class "Default")
      (node (ref "D2") (pin "+") (pinfunction "+_+") (pintype "passive"))
      (node (ref "R11") (pin "1") (pinfunction "1_1") (pintype "passive"))
    )
    (net (code "128") (name "Net-(D3-Pad+)") (class "Default")
      (node (ref "D3") (pin "+") (pinfunction "+_+") (pintype "passive"))
      (node (ref "R12") (pin "1") (pinfunction "1_1") (pintype "passive"))
    )
    (net (code "129") (name "Net-(D4-Pad-)") (class "Default")
      (node (ref "D4") (pin "-") (pinfunction "-_-") (pintype "passive"))
      (node (ref "R18") (pin "1") (pinfunction "1_1") (pintype "passive"))
    )
    (net (code "130") (name "Net-(D5-Pad-)") (class "Default")
      (node (ref "D5") (pin "-") (pinfunction "-_-") (pintype "passive"))
      (node (ref "R51") (pin "1") (pinfunction "1_1") (pintype "passive"))
    )
    (net (code "131") (name "Net-(D6-Pad-)") (class "Default")
      (node (ref "D6") (pin "-") (pinfunction "-_-") (pintype "passive"))
      (node (ref "R52") (pin "1") (pinfunction "1_1") (pintype "passive"))
    )
    (net (code "132") (name "Net-(D7-Pad-)") (class "Default")
      (node (ref "D7") (pin "-") (pinfunction "-_-") (pintype "passive"))
      (node (ref "R53") (pin "1") (pinfunction "1_1") (pintype "passive"))
    )
    (net (code "133") (name "Net-(D8-Pad-)") (class "Default")
      (node (ref "D8") (pin "-") (pinfunction "-_-") (pintype "passive"))
      (node (ref "R54") (pin "1") (pinfunction "1_1") (pintype "passive"))
    )
    (net (code "134") (name "Net-(IC2-VBUS)") (class "Default")
      (node (ref "C31") (pin "1") (pinfunction "1_1") (pintype "passive"))
      (node (ref "IC2") (pin "6") (pinfunction "VBUS_6") (pintype "bidirectional"))
      (node (ref "L4") (pin "1") (pinfunction "1_1") (pintype "passive"))
      (node (ref "L5") (pin "1") (pinfunction "1_1") (pintype "passive"))
      (node (ref "U7") (pin "6") (pinfunction "OUT1_6") (pintype "bidirectional"))
      (node (ref "U7") (pin "7") (pinfunction "OUT2_7") (pintype "bidirectional"))
      (node (ref "U7") (pin "8") (pinfunction "OUT3_8") (pintype "bidirectional"))
    )
    (net (code "135") (name "Net-(J1-VCC)") (class "Default")
      (node (ref "J1") (pin "1") (pinfunction "VCC_1") (pintype "bidirectional"))
      (node (ref "R47") (pin "1") (pinfunction "1_1") (pintype "passive"))
    )
    (net (code "136") (name "Net-(J7-P$2)") (class "Default")
      (node (ref "J7") (pin "2") (pinfunction "P$2_2") (pintype "bidirectional"))
      (node (ref "U9") (pin "4") (pinfunction "Y_4") (pintype "bidirectional"))
    )
    (net (code "137") (name "Net-(JP2-VBUS)") (class "Default")
      (node (ref "JP2") (pin "1") (pinfunction "VBUS_1") (pintype "bidirectional"))
      (node (ref "L5") (pin "2") (pinfunction "2_2") (pintype "passive"))
    )
    (net (code "138") (name "Net-(Q1-D)") (class "Default")
      (node (ref "D1") (pin "-") (pinfunction "-_-") (pintype "passive"))
      (node (ref "Q1") (pin "3") (pinfunction "D_3") (pintype "passive"))
    )
    (net (code "139") (name "Net-(Q2-D)") (class "Default")
      (node (ref "D2") (pin "-") (pinfunction "-_-") (pintype "passive"))
      (node (ref "Q2") (pin "3") (pinfunction "D_3") (pintype "passive"))
    )
    (net (code "140") (name "Net-(Q3-D)") (class "Default")
      (node (ref "D3") (pin "-") (pinfunction "-_-") (pintype "passive"))
      (node (ref "Q3") (pin "3") (pinfunction "D_3") (pintype "passive"))
    )
    (net (code "141") (name "Net-(Q4-B)") (class "Default")
      (node (ref "Q4") (pin "1") (pinfunction "B_1") (pintype "passive"))
      (node (ref "R17") (pin "1") (pinfunction "1_1") (pintype "passive"))
      (node (ref "U3") (pin "2") (pinfunction "K_2") (pintype "bidirectional"))
    )
    (net (code "142") (name "Net-(R23-Pad1)") (class "Default")
      (node (ref "R23") (pin "1") (pinfunction "1_1") (pintype "passive"))
      (node (ref "SW2") (pin "3") (pinfunction "3_3") (pintype "bidirectional"))
      (node (ref "SW2") (pin "4") (pinfunction "4_4") (pintype "bidirectional"))
    )
    (net (code "143") (name "Net-(R76-Pad1)") (class "Default")
      (node (ref "R76") (pin "1") (pinfunction "1_1") (pintype "passive"))
      (node (ref "R77") (pin "2") (pinfunction "2_2") (pintype "passive"))
    )
    (net (code "144") (name "Net-(TP6-TP)") (class "Default")
      (node (ref "TP6") (pin "P$1") (pinfunction "TP_P$1") (pintype "bidirectional"))
      (node (ref "U1") (pin "N7") (pinfunction "PMIC_BAT_SENSE_N7") (pintype "bidirectional"))
    )
    (net (code "145") (name "Net-(TP7-TP)") (class "Default")
      (node (ref "TP7") (pin "P$1") (pinfunction "TP_P$1") (pintype "bidirectional"))
      (node (ref "U1") (pin "N6") (pinfunction "PMIC_TS_N6") (pintype "bidirectional"))
    )
    (net (code "146") (name "Net-(U1A-RTC_KALDO_ENN)") (class "Default")
      (node (ref "R3") (pin "1") (pinfunction "1_1") (pintype "passive"))
      (node (ref "U1") (pin "M16") (pinfunction "RTC_KALDO_ENN_M16") (pintype "bidirectional"))
    )
    (net (code "147") (name "Net-(U1C-MMC0_CLK)") (class "Default")
      (node (ref "R95") (pin "2") (pinfunction "2_2") (pintype "passive"))
      (node (ref "U1") (pin "B15") (pinfunction "MMC0_CLK_B15") (pintype "bidirectional"))
    )
    (net (code "148") (name "Net-(U1C-XDMA_EVENT_INTR1)") (class "Default")
      (node (ref "R96") (pin "1") (pinfunction "1_1") (pintype "passive"))
      (node (ref "U1") (pin "B4") (pinfunction "XDMA_EVENT_INTR1_B4") (pintype "bidirectional"))
    )
    (net (code "149") (name "Net-(U1D-LCD_AC_BIAS_EN)") (class "Default")
      (node (ref "R118") (pin "1") (pinfunction "1_1") (pintype "passive"))
      (node (ref "U1") (pin "E1") (pinfunction "LCD_AC_BIAS_EN_E1") (pintype "bidirectional"))
    )
    (net (code "150") (name "Net-(U1D-LCD_HSYNC)") (class "Default")
      (node (ref "R117") (pin "1") (pinfunction "1_1") (pintype "passive"))
      (node (ref "U1") (pin "F2") (pinfunction "LCD_HSYNC_F2") (pintype "bidirectional"))
    )
    (net (code "151") (name "Net-(U1D-LCD_PCLK)") (class "Default")
      (node (ref "R115") (pin "1") (pinfunction "1_1") (pintype "passive"))
      (node (ref "U1") (pin "F1") (pinfunction "LCD_PCLK_F1") (pintype "bidirectional"))
    )
    (net (code "152") (name "Net-(U1D-LCD_VSYNC)") (class "Default")
      (node (ref "R116") (pin "1") (pinfunction "1_1") (pintype "passive"))
      (node (ref "U1") (pin "F3") (pinfunction "LCD_VSYNC_F3") (pintype "bidirectional"))
    )
    (net (code "153") (name "Net-(U1F-VDDS_DDR)") (class "Default")
      (node (ref "TP9") (pin "TP") (pinfunction "TP_TP") (pintype "input"))
      (node (ref "U1") (pin "F4") (pinfunction "VDDS_DDR_F4") (pintype "bidirectional"))
    )
    (net (code "154") (name "Net-(U1F-VDDS_PLL)") (class "Default")
      (node (ref "TP4") (pin "TP") (pinfunction "TP_TP") (pintype "input"))
      (node (ref "U1") (pin "G13") (pinfunction "VDDS_PLL_G13") (pintype "bidirectional"))
    )
    (net (code "155") (name "Net-(U1F-VDD_CORE)") (class "Default")
      (node (ref "TP2") (pin "TP") (pinfunction "TP_TP") (pintype "input"))
      (node (ref "U1") (pin "G4") (pinfunction "VDD_CORE_G4") (pintype "bidirectional"))
    )
    (net (code "156") (name "Net-(U1F-VDD_MPU)") (class "Default")
      (node (ref "TP3") (pin "TP") (pinfunction "TP_TP") (pintype "input"))
      (node (ref "U1") (pin "F13") (pinfunction "VDD_MPU_F13") (pintype "bidirectional"))
    )
    (net (code "157") (name "Net-(U2-Y)") (class "Default")
      (node (ref "R24") (pin "1") (pinfunction "1_1") (pintype "passive"))
      (node (ref "U2") (pin "4") (pinfunction "Y_4") (pintype "bidirectional"))
    )
    (net (code "158") (name "Net-(U3-R)") (class "Default")
      (node (ref "R20") (pin "2") (pinfunction "2_2") (pintype "passive"))
      (node (ref "R21") (pin "1") (pinfunction "1_1") (pintype "passive"))
      (node (ref "U3") (pin "1") (pinfunction "R_1") (pintype "bidirectional"))
    )
    (net (code "159") (name "Net-(U4-BT_AUD_CLK)") (class "Default")
      (node (ref "TP28") (pin "T") (pinfunction "T_T") (pintype "bidirectional"))
      (node (ref "U4") (pin "60") (pinfunction "BT_AUD_CLK_60") (pintype "bidirectional"))
    )
    (net (code "160") (name "Net-(U4-BT_AUD_FSYNC)") (class "Default")
      (node (ref "TP27") (pin "T") (pinfunction "T_T") (pintype "bidirectional"))
      (node (ref "U4") (pin "58") (pinfunction "BT_AUD_FSYNC_58") (pintype "bidirectional"))
    )
    (net (code "161") (name "Net-(U4-BT_AUD_IN)") (class "Default")
      (node (ref "TP17") (pin "T") (pinfunction "T_T") (pintype "bidirectional"))
      (node (ref "U4") (pin "56") (pinfunction "BT_AUD_IN_56") (pintype "bidirectional"))
    )
    (net (code "162") (name "Net-(U4-BT_AUD_OUT)") (class "Default")
      (node (ref "R119") (pin "1") (pinfunction "1_1") (pintype "passive"))
      (node (ref "TP25") (pin "T") (pinfunction "T_T") (pintype "bidirectional"))
      (node (ref "U4") (pin "57") (pinfunction "BT_AUD_OUT_57") (pintype "bidirectional"))
    )
    (net (code "163") (name "Net-(U4-BT_HCI_CTS)") (class "Default")
      (node (ref "R14") (pin "1") (pinfunction "1_1") (pintype "passive"))
      (node (ref "U4") (pin "51") (pinfunction "BT_HCI_CTS_51") (pintype "bidirectional"))
    )
    (net (code "164") (name "Net-(U4-BT_HCI_RTS)") (class "Default")
      (node (ref "R13") (pin "1") (pinfunction "1_1") (pintype "passive"))
      (node (ref "U4") (pin "50") (pinfunction "BT_HCI_RTS_50") (pintype "bidirectional"))
    )
    (net (code "165") (name "Net-(U4-BT_HCI_RX)") (class "Default")
      (node (ref "R16") (pin "1") (pinfunction "1_1") (pintype "passive"))
      (node (ref "U4") (pin "53") (pinfunction "BT_HCI_RX_53") (pintype "bidirectional"))
    )
    (net (code "166") (name "Net-(U4-BT_HCI_TX)") (class "Default")
      (node (ref "R15") (pin "1") (pinfunction "1_1") (pintype "passive"))
      (node (ref "U4") (pin "52") (pinfunction "BT_HCI_TX_52") (pintype "bidirectional"))
    )
    (net (code "167") (name "Net-(U4-BT_UART_DBG)") (class "Default")
      (node (ref "TP32") (pin "T") (pinfunction "T_T") (pintype "bidirectional"))
      (node (ref "U4") (pin "43") (pinfunction "BT_UART_DBG_43") (pintype "bidirectional"))
    )
    (net (code "168") (name "Net-(U4-GPIO1)") (class "Default")
      (node (ref "TP30") (pin "T") (pinfunction "T_T") (pintype "bidirectional"))
      (node (ref "U4") (pin "27") (pinfunction "GPIO1_27") (pintype "bidirectional"))
    )
    (net (code "169") (name "Net-(U4-GPIO2)") (class "Default")
      (node (ref "TP29") (pin "T") (pinfunction "T_T") (pintype "bidirectional"))
      (node (ref "U4") (pin "26") (pinfunction "GPIO2_26") (pintype "bidirectional"))
    )
    (net (code "170") (name "Net-(U4-RF_ANT1)") (class "Default")
      (node (ref "C9") (pin "2") (pinfunction "2_2") (pintype "passive"))
      (node (ref "U4") (pin "32") (pinfunction "RF_ANT1_32") (pintype "bidirectional"))
    )
    (net (code "171") (name "Net-(U4-RF_ANT2)") (class "Default")
      (node (ref "C10") (pin "2") (pinfunction "2_2") (pintype "passive"))
      (node (ref "U4") (pin "18") (pinfunction "RF_ANT2_18") (pintype "bidirectional"))
    )
    (net (code "172") (name "Net-(U4-WLAN_IRQ)") (class "Default")
      (node (ref "R29") (pin "1") (pinfunction "1_1") (pintype "passive"))
      (node (ref "R30") (pin "2") (pinfunction "2_2") (pintype "passive"))
      (node (ref "U4") (pin "14") (pinfunction "WLAN_IRQ_14") (pintype "bidirectional"))
    )
    (net (code "173") (name "Net-(U4-WL_SDIO_CLK)") (class "Default")
      (node (ref "R22") (pin "1") (pinfunction "1_1") (pintype "passive"))
      (node (ref "U4") (pin "8") (pinfunction "WL_SDIO_CLK_8") (pintype "bidirectional"))
    )
    (net (code "174") (name "Net-(U4-WL_SDIO_CMD)") (class "Default")
      (node (ref "R19") (pin "1") (pinfunction "1_1") (pintype "passive"))
      (node (ref "U4") (pin "6") (pinfunction "WL_SDIO_CMD_6") (pintype "bidirectional"))
    )
    (net (code "175") (name "Net-(U4-WL_SDIO_D0)") (class "Default")
      (node (ref "R25") (pin "1") (pinfunction "1_1") (pintype "passive"))
      (node (ref "U4") (pin "10") (pinfunction "WL_SDIO_D0_10") (pintype "bidirectional"))
    )
    (net (code "176") (name "Net-(U4-WL_SDIO_D1)") (class "Default")
      (node (ref "R26") (pin "1") (pinfunction "1_1") (pintype "passive"))
      (node (ref "U4") (pin "11") (pinfunction "WL_SDIO_D1_11") (pintype "bidirectional"))
    )
    (net (code "177") (name "Net-(U4-WL_SDIO_D2)") (class "Default")
      (node (ref "R27") (pin "1") (pinfunction "1_1") (pintype "passive"))
      (node (ref "U4") (pin "12") (pinfunction "WL_SDIO_D2_12") (pintype "bidirectional"))
    )
    (net (code "178") (name "Net-(U4-WL_SDIO_D3)") (class "Default")
      (node (ref "R28") (pin "1") (pinfunction "1_1") (pintype "passive"))
      (node (ref "U4") (pin "13") (pinfunction "WL_SDIO_D3_13") (pintype "bidirectional"))
    )
    (net (code "179") (name "Net-(U4-WL_UART_DBG)") (class "Default")
      (node (ref "TP31") (pin "T") (pinfunction "T_T") (pintype "bidirectional"))
      (node (ref "U4") (pin "42") (pinfunction "WL_UART_DBG_42") (pintype "bidirectional"))
    )
    (net (code "180") (name "Net-(U5-MR#)") (class "Default")
      (node (ref "R23") (pin "2") (pinfunction "2_2") (pintype "passive"))
      (node (ref "R24") (pin "2") (pinfunction "2_2") (pintype "passive"))
      (node (ref "U5") (pin "3") (pinfunction "MR#_3") (pintype "bidirectional"))
    )
    (net (code "181") (name "Net-(U5-RESET#)") (class "Default")
      (node (ref "R31") (pin "2") (pinfunction "2_2") (pintype "passive"))
      (node (ref "U5") (pin "2") (pinfunction "RESET#_2") (pintype "bidirectional"))
    )
    (net (code "182") (name "Net-(U6-BOOT)") (class "Default")
      (node (ref "C19") (pin "2") (pinfunction "2_2") (pintype "passive"))
      (node (ref "U6") (pin "6") (pinfunction "BOOT_6") (pintype "bidirectional"))
    )
    (net (code "183") (name "Net-(U6-EN)") (class "Default")
      (node (ref "R57") (pin "1") (pinfunction "1_1") (pintype "passive"))
      (node (ref "R58") (pin "2") (pinfunction "2_2") (pintype "passive"))
      (node (ref "U6") (pin "5") (pinfunction "EN_5") (pintype "bidirectional"))
    )
    (net (code "184") (name "Net-(U6-FB)") (class "Default")
      (node (ref "C23") (pin "2") (pinfunction "2_2") (pintype "passive"))
      (node (ref "R60") (pin "1") (pinfunction "1_1") (pintype "passive"))
      (node (ref "R61") (pin "2") (pinfunction "2_2") (pintype "passive"))
      (node (ref "U6") (pin "4") (pinfunction "FB_4") (pintype "bidirectional"))
    )
    (net (code "185") (name "Net-(U6-SW)") (class "Default")
      (node (ref "C19") (pin "1") (pinfunction "1_1") (pintype "passive"))
      (node (ref "L3") (pin "1") (pinfunction "1_1") (pintype "passive"))
      (node (ref "U6") (pin "2") (pinfunction "SW_2") (pintype "bidirectional"))
    )
    (net (code "186") (name "Net-(U8-FB)") (class "Default")
      (node (ref "R76") (pin "2") (pinfunction "2_2") (pintype "passive"))
      (node (ref "R78") (pin "2") (pinfunction "2_2") (pintype "passive"))
      (node (ref "U8") (pin "5") (pinfunction "FB_5") (pintype "bidirectional"))
    )
    (net (code "187") (name "Net-(U8-SW)") (class "Default")
      (node (ref "L6") (pin "1") (pinfunction "1_1") (pintype "passive"))
      (node (ref "U8") (pin "3") (pinfunction "SW_3") (pintype "bidirectional"))
    )
    (net (code "188") (name "Net-(U11-DDCSCL)") (class "Default")
      (node (ref "R102") (pin "1") (pinfunction "1_1") (pintype "passive"))
      (node (ref "U11") (pin "16") (pinfunction "DDCSCL_16") (pintype "bidirectional"))
    )
    (net (code "189") (name "Net-(U11-DDCSDA)") (class "Default")
      (node (ref "R103") (pin "1") (pinfunction "1_1") (pintype "passive"))
      (node (ref "U11") (pin "15") (pinfunction "DDCSDA_15") (pintype "bidirectional"))
    )
    (net (code "190") (name "Net-(U11-ENTEST)") (class "Default")
      (node (ref "R98") (pin "1") (pinfunction "1_1") (pintype "passive"))
      (node (ref "U11") (pin "31") (pinfunction "ENTEST_31") (pintype "bidirectional"))
    )
    (net (code "191") (name "Net-(U11-I2S0)") (class "Default")
      (node (ref "R85") (pin "2") (pinfunction "2_2") (pintype "passive"))
      (node (ref "U11") (pin "5") (pinfunction "I2S0_5") (pintype "bidirectional"))
    )
    (net (code "192") (name "Net-(U11-I2S3{slash}SPDIF)") (class "Default")
      (node (ref "R86") (pin "2") (pinfunction "2_2") (pintype "passive"))
      (node (ref "U11") (pin "2") (pinfunction "I2S3/SPDIF_2") (pintype "bidirectional"))
    )
    (net (code "193") (name "Net-(U11-PCADR)") (class "Default")
      (node (ref "R100") (pin "2") (pinfunction "2_2") (pintype "passive"))
      (node (ref "R101") (pin "2") (pinfunction "2_2") (pintype "passive"))
      (node (ref "U11") (pin "32") (pinfunction "PCADR_32") (pintype "bidirectional"))
    )
    (net (code "194") (name "Net-(U11-REXT)") (class "Default")
      (node (ref "R99") (pin "2") (pinfunction "2_2") (pintype "passive"))
      (node (ref "U11") (pin "20") (pinfunction "REXT_20") (pintype "bidirectional"))
    )
    (net (code "195") (name "Net-(U11-SYSRSTN)") (class "Default")
      (node (ref "C38") (pin "2") (pinfunction "2_2") (pintype "passive"))
      (node (ref "R84") (pin "2") (pinfunction "2_2") (pintype "passive"))
      (node (ref "U11") (pin "33") (pinfunction "SYSRSTN_33") (pintype "bidirectional"))
    )
    (net (code "196") (name "Net-(U12-CP1)") (class "Default")
      (node (ref "C56") (pin "1") (pinfunction "1_1") (pintype "passive"))
      (node (ref "U12") (pin "4") (pinfunction "CP1_4") (pintype "bidirectional"))
    )
    (net (code "197") (name "Net-(U12-CP2)") (class "Default")
      (node (ref "C56") (pin "2") (pinfunction "2_2") (pintype "passive"))
      (node (ref "U12") (pin "5") (pinfunction "CP2_5") (pintype "bidirectional"))
    )
    (net (code "198") (name "Net-(U12-ROSC)") (class "Default")
      (node (ref "R108") (pin "1") (pinfunction "1_1") (pintype "passive"))
      (node (ref "U12") (pin "13") (pinfunction "ROSC_13") (pintype "bidirectional"))
    )
    (net (code "199") (name "Net-(U12-SENSE1)") (class "Default")
      (node (ref "R110") (pin "2") (pinfunction "2_2") (pintype "passive"))
      (node (ref "U12") (pin "23") (pinfunction "SENSE1_23") (pintype "bidirectional"))
    )
    (net (code "200") (name "Net-(U12-SENSE2)") (class "Default")
      (node (ref "R111") (pin "2") (pinfunction "2_2") (pintype "passive"))
      (node (ref "U12") (pin "27") (pinfunction "SENSE2_27") (pintype "bidirectional"))
    )
    (net (code "201") (name "Net-(U12-VCP)") (class "Default")
      (node (ref "C68") (pin "1") (pinfunction "1_1") (pintype "passive"))
      (node (ref "U12") (pin "6") (pinfunction "VCP_6") (pintype "bidirectional"))
    )
    (net (code "202") (name "Net-(U12-VREG)") (class "Default")
      (node (ref "C67") (pin "1") (pinfunction "1_1") (pintype "passive"))
      (node (ref "U12") (pin "8") (pinfunction "VREG_8") (pintype "bidirectional"))
    )
    (net (code "203") (name "Net-(U16-FB)") (class "Default")
      (node (ref "R113") (pin "1") (pinfunction "1_1") (pintype "passive"))
      (node (ref "R114") (pin "2") (pinfunction "2_2") (pintype "passive"))
      (node (ref "U16") (pin "5") (pinfunction "FB_5") (pintype "bidirectional"))
    )
    (net (code "204") (name "Net-(U16-SW)") (class "Default")
      (node (ref "L10") (pin "1") (pinfunction "1_1") (pintype "passive"))
      (node (ref "U16") (pin "3") (pinfunction "SW_3") (pintype "bidirectional"))
    )
    (net (code "205") (name "Net-(VR1-2)") (class "Default")
      (node (ref "R112") (pin "2") (pinfunction "2_2") (pintype "passive"))
      (node (ref "VR1") (pin "3") (pinfunction "2_3") (pintype "passive"))
    )
    (net (code "206") (name "PWR_IN_12V") (class "Default")
      (node (ref "C16") (pin "2") (pinfunction "2_2") (pintype "passive"))
      (node (ref "C17") (pin "2") (pinfunction "2_2") (pintype "passive"))
      (node (ref "C18") (pin "2") (pinfunction "2_2") (pintype "passive"))
      (node (ref "J2") (pin "+") (pinfunction "+_+") (pintype "bidirectional"))
      (node (ref "R57") (pin "2") (pinfunction "2_2") (pintype "passive"))
      (node (ref "R97") (pin "1") (pinfunction "1_1") (pintype "passive"))
      (node (ref "TP1") (pin "T") (pinfunction "T_T") (pintype "bidirectional"))
      (node (ref "U6") (pin "3") (pinfunction "VIN_3") (pintype "bidirectional"))
    )
    (net (code "207") (name "SYS_5V") (class "Default")
      (node (ref "C24") (pin "1") (pinfunction "1_1") (pintype "passive"))
      (node (ref "U7") (pin "2") (pinfunction "IN1_2") (pintype "bidirectional"))
      (node (ref "U7") (pin "3") (pinfunction "IN2_3") (pintype "bidirectional"))
    )
    (net (code "208") (name "SYS_ADC_1P8V") (class "Default")
      (node (ref "C28") (pin "1") (pinfunction "1_1") (pintype "passive"))
      (node (ref "R65") (pin "2") (pinfunction "2_2") (pintype "passive"))
      (node (ref "U1") (pin "A7") (pinfunction "SYS_ADC_1P8V_A7") (pintype "bidirectional"))
    )
    (net (code "209") (name "SYS_RTC_1P8V") (class "Default")
      (node (ref "Q4") (pin "3") (pinfunction "C_3") (pintype "passive"))
      (node (ref "R20") (pin "1") (pinfunction "1_1") (pintype "passive"))
      (node (ref "TP14") (pin "TP") (pinfunction "TP_TP") (pintype "input"))
      (node (ref "U1") (pin "K11") (pinfunction "SYS_RTC_1P8V_K11") (pintype "power_in"))
      (node (ref "U1") (pin "L11") (pinfunction "SYS_RTC_1P8V_L11") (pintype "power_in"))
      (node (ref "U2") (pin "5") (pinfunction "VCC_5") (pintype "bidirectional"))
      (node (ref "U3") (pin "3") (pinfunction "A_3") (pintype "bidirectional"))
    )
    (net (code "210") (name "SYS_VDD1_3P3V") (class "Default")
      (node (ref "C32") (pin "1") (pinfunction "1_1") (pintype "passive"))
      (node (ref "C34") (pin "1") (pinfunction "1_1") (pintype "passive"))
      (node (ref "C44") (pin "2") (pinfunction "2_2") (pintype "passive"))
      (node (ref "C70") (pin "2") (pinfunction "2_2") (pintype "passive"))
      (node (ref "C72") (pin "2") (pinfunction "2_2") (pintype "passive"))
      (node (ref "J3") (pin "4") (pinfunction "VDD_4") (pintype "bidirectional"))
      (node (ref "L8") (pin "1") (pinfunction "1_1") (pintype "passive"))
      (node (ref "R1") (pin "2") (pinfunction "2_2") (pintype "passive"))
      (node (ref "R2") (pin "2") (pinfunction "2_2") (pintype "passive"))
      (node (ref "R34") (pin "2") (pinfunction "2_2") (pintype "passive"))
      (node (ref "R44") (pin "2") (pinfunction "2_2") (pintype "passive"))
      (node (ref "R45") (pin "2") (pinfunction "2_2") (pintype "passive"))
      (node (ref "R63") (pin "1") (pinfunction "1_1") (pintype "passive"))
      (node (ref "R67") (pin "2") (pinfunction "2_2") (pintype "passive"))
      (node (ref "R68") (pin "2") (pinfunction "2_2") (pintype "passive"))
      (node (ref "R69") (pin "2") (pinfunction "2_2") (pintype "passive"))
      (node (ref "R71") (pin "2") (pinfunction "2_2") (pintype "passive"))
      (node (ref "R72") (pin "2") (pinfunction "2_2") (pintype "passive"))
      (node (ref "R73") (pin "2") (pinfunction "2_2") (pintype "passive"))
      (node (ref "R74") (pin "2") (pinfunction "2_2") (pintype "passive"))
      (node (ref "R75") (pin "2") (pinfunction "2_2") (pintype "passive"))
      (node (ref "TP12") (pin "TP") (pinfunction "TP_TP") (pintype "input"))
      (node (ref "U1") (pin "F6") (pinfunction "SYS_VDD1_3P3V_F6") (pintype "power_in"))
      (node (ref "U1") (pin "F7") (pinfunction "SYS_VDD1_3P3V_F7") (pintype "power_in"))
      (node (ref "U1") (pin "G6") (pinfunction "SYS_VDD1_3P3V_G6") (pintype "power_in"))
      (node (ref "U1") (pin "G7") (pinfunction "SYS_VDD1_3P3V_G7") (pintype "power_in"))
      (node (ref "U10") (pin "7") (pinfunction "2OE_7") (pintype "input"))
      (node (ref "U10") (pin "8") (pinfunction "VCC_8") (pintype "power_in"))
      (node (ref "U5") (pin "4") (pinfunction "VCC_4") (pintype "bidirectional"))
      (node (ref "U8") (pin "1") (pinfunction "EN_1") (pintype "bidirectional"))
    )
    (net (code "211") (name "SYS_VDD2_3P3V") (class "Default")
      (node (ref "D4") (pin "+") (pinfunction "+_+") (pintype "passive"))
      (node (ref "TP13") (pin "TP") (pinfunction "TP_TP") (pintype "input"))
      (node (ref "U1") (pin "F11") (pinfunction "SYS_VDD2_3P3V_F11") (pintype "power_in"))
      (node (ref "U1") (pin "G11") (pinfunction "SYS_VDD2_3P3V_G11") (pintype "power_in"))
    )
    (net (code "212") (name "SYS_VDD3_3P3V") (class "Default")
      (node (ref "Q4") (pin "2") (pinfunction "E_2") (pintype "passive"))
      (node (ref "R17") (pin "2") (pinfunction "2_2") (pintype "passive"))
      (node (ref "R21") (pin "2") (pinfunction "2_2") (pintype "passive"))
      (node (ref "TP16") (pin "TP") (pinfunction "TP_TP") (pintype "input"))
      (node (ref "U1") (pin "F8") (pinfunction "SYS_VDD3_3P3V_F8") (pintype "power_in"))
      (node (ref "U1") (pin "F9") (pinfunction "VDDSHV4_F9") (pintype "power_in"))
      (node (ref "U1") (pin "G8") (pinfunction "SYS_VDD3_3P3V_G8") (pintype "power_in"))
      (node (ref "U1") (pin "H7") (pinfunction "SYS_VDD3_3P3V_H7") (pintype "power_in"))
      (node (ref "U1") (pin "H8") (pinfunction "SYS_VDD3_3P3V_H8") (pintype "power_in"))
      (node (ref "U1") (pin "H9") (pinfunction "VDDSHV6_H9") (pintype "power_in"))
      (node (ref "U1") (pin "J7") (pinfunction "SYS_VDD3_3P3V_J7") (pintype "power_in"))
      (node (ref "U1") (pin "J8") (pinfunction "SYS_VDD3_3P3V_J8") (pintype "power_in"))
      (node (ref "U1") (pin "J9") (pinfunction "VDDSHV1_J9") (pintype "power_in"))
      (node (ref "U1") (pin "K8") (pinfunction "SYS_VDD3_3P3V_K8") (pintype "power_in"))
      (node (ref "U1") (pin "K9") (pinfunction "VDDSHV2_K9") (pintype "power_in"))
      (node (ref "U1") (pin "L8") (pinfunction "SYS_VDD3_3P3V_L8") (pintype "power_in"))
      (node (ref "U1") (pin "L9") (pinfunction "VDDSHV3_L9") (pintype "power_in"))
    )
    (net (code "213") (name "SYS_VDD_1P8V") (class "Default")
      (node (ref "L1") (pin "1") (pinfunction "1_1") (pintype "passive"))
      (node (ref "TP15") (pin "TP") (pinfunction "TP_TP") (pintype "input"))
      (node (ref "U1") (pin "F10") (pinfunction "SYS_VDD_1P8V_F10") (pintype "power_in"))
      (node (ref "U1") (pin "G10") (pinfunction "SYS_VDD_1P8V_G10") (pintype "power_in"))
      (node (ref "U1") (pin "G9") (pinfunction "VDDSHV5_G9") (pintype "power_in"))
      (node (ref "U1") (pin "H10") (pinfunction "SYS_VDD_1P8V_H10") (pintype "power_in"))
      (node (ref "U1") (pin "H11") (pinfunction "SYS_VDD_1P8V_H11") (pintype "power_in"))
      (node (ref "U1") (pin "J10") (pinfunction "SYS_VDD_1P8V_J10") (pintype "power_in"))
      (node (ref "U1") (pin "J11") (pinfunction "SYS_VDD_1P8V_J11") (pintype "power_in"))
      (node (ref "U1") (pin "K10") (pinfunction "SYS_VDD_1P8V_K10") (pintype "power_in"))
      (node (ref "U1") (pin "L10") (pinfunction "SYS_VDD_1P8V_L10") (pintype "power_in"))
    )
    (net (code "214") (name "SYS_VOUT") (class "Default")
      (node (ref "C74") (pin "2") (pinfunction "2_2") (pintype "passive"))
      (node (ref "C75") (pin "2") (pinfunction "2_2") (pintype "passive"))
      (node (ref "C79") (pin "2") (pinfunction "2_2") (pintype "passive"))
      (node (ref "C80") (pin "2") (pinfunction "2_2") (pintype "passive"))
      (node (ref "L9") (pin "1") (pinfunction "1_1") (pintype "passive"))
      (node (ref "TP11") (pin "TP") (pinfunction "TP_TP") (pintype "input"))
      (node (ref "U1") (pin "K6") (pinfunction "SYS_VOUT_K6") (pintype "power_in"))
      (node (ref "U1") (pin "K7") (pinfunction "SYS_VOUT_K7") (pintype "power_in"))
      (node (ref "U1") (pin "L6") (pinfunction "SYS_VOUT_L6") (pintype "power_in"))
      (node (ref "U1") (pin "L7") (pinfunction "SYS_VOUT_L7") (pintype "power_in"))
      (node (ref "U16") (pin "4") (pinfunction "VIN_4") (pintype "bidirectional"))
    )
    (net (code "215") (name "VCC") (class "Default")
      (node (ref "C53") (pin "1") (pinfunction "1_1") (pintype "passive"))
      (node (ref "L7") (pin "2") (pinfunction "2_2") (pintype "passive"))
      (node (ref "R112") (pin "1") (pinfunction "1_1") (pintype "passive"))
      (node (ref "R87") (pin "2") (pinfunction "2_2") (pintype "passive"))
      (node (ref "R88") (pin "2") (pinfunction "2_2") (pintype "passive"))
      (node (ref "R89") (pin "2") (pinfunction "2_2") (pintype "passive"))
      (node (ref "R90") (pin "2") (pinfunction "2_2") (pintype "passive"))
      (node (ref "R91") (pin "2") (pinfunction "2_2") (pintype "passive"))
      (node (ref "R92") (pin "2") (pinfunction "2_2") (pintype "passive"))
      (node (ref "R93") (pin "2") (pinfunction "2_2") (pintype "passive"))
      (node (ref "U12") (pin "15") (pinfunction "VDD_15") (pintype "power_in"))
    )
    (net (code "216") (name "VDD_3V3B") (class "Default")
      (node (ref "C35") (pin "2") (pinfunction "2_2") (pintype "passive"))
      (node (ref "C36") (pin "2") (pinfunction "2_2") (pintype "passive"))
      (node (ref "L2") (pin "1") (pinfunction "1_1") (pintype "passive"))
      (node (ref "L6") (pin "2") (pinfunction "2_2") (pintype "passive"))
      (node (ref "L7") (pin "1") (pinfunction "1_1") (pintype "passive"))
      (node (ref "R78") (pin "1") (pinfunction "1_1") (pintype "passive"))
    )
    (net (code "217") (name "VDD_5V") (class "Default")
      (node (ref "C1") (pin "+") (pinfunction "+_+") (pintype "passive"))
      (node (ref "C21") (pin "2") (pinfunction "2_2") (pintype "passive"))
      (node (ref "C22") (pin "2") (pinfunction "2_2") (pintype "passive"))
      (node (ref "C26") (pin "2") (pinfunction "2_2") (pintype "passive"))
      (node (ref "C29") (pin "2") (pinfunction "2_2") (pintype "passive"))
      (node (ref "C30") (pin "2") (pinfunction "2_2") (pintype "passive"))
      (node (ref "C33") (pin "2") (pinfunction "2_2") (pintype "passive"))
      (node (ref "J7") (pin "3") (pinfunction "P$3_3") (pintype "bidirectional"))
      (node (ref "J8") (pin "2") (pinfunction "P$2_2") (pintype "bidirectional"))
      (node (ref "J8") (pin "3") (pinfunction "P$3_3") (pintype "bidirectional"))
      (node (ref "L3") (pin "2") (pinfunction "2_2") (pintype "passive"))
      (node (ref "R59") (pin "2") (pinfunction "2_2") (pintype "passive"))
      (node (ref "U1") (pin "P10") (pinfunction "VIN_AC_P10") (pintype "power_in"))
      (node (ref "U1") (pin "R10") (pinfunction "VIN_AC_R10") (pintype "power_in"))
      (node (ref "U1") (pin "T10") (pinfunction "VIN_AC_T10") (pintype "power_in"))
      (node (ref "U8") (pin "4") (pinfunction "VIN_4") (pintype "bidirectional"))
      (node (ref "U9") (pin "5") (pinfunction "VCC_5") (pintype "bidirectional"))
    )
    (net (code "218") (name "VDD_BAT") (class "Default")
      (node (ref "TP5") (pin "P$1") (pinfunction "TP_P$1") (pintype "bidirectional"))
      (node (ref "U1") (pin "P8") (pinfunction "VIN_BAT_P8") (pintype "power_in"))
      (node (ref "U1") (pin "R8") (pinfunction "VIN_BAT_R8") (pintype "power_in"))
      (node (ref "U1") (pin "T8") (pinfunction "VIN_BAT_T8") (pintype "power_in"))
    )
    (net (code "219") (name "VDD_USB_5V") (class "Default")
      (node (ref "C20") (pin "1") (pinfunction "1_1") (pintype "passive"))
      (node (ref "IC1") (pin "6") (pinfunction "VBUS_6") (pintype "bidirectional"))
      (node (ref "R47") (pin "2") (pinfunction "2_2") (pintype "passive"))
      (node (ref "U1") (pin "J16") (pinfunction "USB0_VBUS_J16") (pintype "bidirectional"))
      (node (ref "U1") (pin "P9") (pinfunction "VIN_USB_P9") (pintype "power_in"))
      (node (ref "U1") (pin "R9") (pinfunction "VIN_USB_R9") (pintype "power_in"))
      (node (ref "U1") (pin "T9") (pinfunction "VIN_USB_T9") (pintype "power_in"))
    )
    (net (code "220") (name "unconnected-(FUD1-PadP$1)") (class "Default")
      (node (ref "FUD1") (pin "P$1") (pinfunction "P$1_P$1") (pintype "no_connect"))
    )
    (net (code "221") (name "unconnected-(FUD2-PadP$1)") (class "Default")
      (node (ref "FUD2") (pin "P$1") (pinfunction "P$1_P$1") (pintype "no_connect"))
    )
    (net (code "222") (name "unconnected-(FUD3-PadP$1)") (class "Default")
      (node (ref "FUD3") (pin "P$1") (pinfunction "P$1_P$1") (pintype "no_connect"))
    )
    (net (code "223") (name "unconnected-(FUD4-PadP$1)") (class "Default")
      (node (ref "FUD4") (pin "P$1") (pinfunction "P$1_P$1") (pintype "no_connect"))
    )
    (net (code "224") (name "unconnected-(FUD5-PadP$1)") (class "Default")
      (node (ref "FUD5") (pin "P$1") (pinfunction "P$1_P$1") (pintype "no_connect"))
    )
    (net (code "225") (name "unconnected-(FUD6-PadP$1)") (class "Default")
      (node (ref "FUD6") (pin "P$1") (pinfunction "P$1_P$1") (pintype "no_connect"))
    )
    (net (code "226") (name "unconnected-(IC1-NC-Pad5)") (class "Default")
      (node (ref "IC1") (pin "5") (pinfunction "NC_5") (pintype "bidirectional"))
    )
    (net (code "227") (name "unconnected-(IC2-ID-Pad3)") (class "Default")
      (node (ref "IC2") (pin "3") (pinfunction "ID_3") (pintype "bidirectional"))
    )
    (net (code "228") (name "unconnected-(IC2-NC-Pad5)") (class "Default")
      (node (ref "IC2") (pin "5") (pinfunction "NC_5") (pintype "bidirectional"))
    )
    (net (code "229") (name "unconnected-(J3-PadG1)") (class "Default")
      (node (ref "J3") (pin "G1") (pinfunction "G1_G1") (pintype "bidirectional"))
    )
    (net (code "230") (name "unconnected-(J4-Pad2)") (class "Default")
      (node (ref "J4") (pin "2") (pinfunction "2_2") (pintype "bidirectional"))
    )
    (net (code "231") (name "unconnected-(J4-Pad3)") (class "Default")
      (node (ref "J4") (pin "3") (pinfunction "3_3") (pintype "bidirectional"))
    )
    (net (code "232") (name "unconnected-(J4-Pad6)") (class "Default")
      (node (ref "J4") (pin "6") (pinfunction "6_6") (pintype "bidirectional"))
    )
    (net (code "233") (name "unconnected-(J6-NC-Pad14)") (class "Default")
      (node (ref "J6") (pin "14") (pinfunction "NC_14") (pintype "bidirectional"))
    )
    (net (code "234") (name "unconnected-(U1B-AIN0-PadA8)") (class "Default")
      (node (ref "U1") (pin "A8") (pinfunction "AIN0_A8") (pintype "bidirectional"))
    )
    (net (code "235") (name "unconnected-(U1B-AIN1-PadB8)") (class "Default")
      (node (ref "U1") (pin "B8") (pinfunction "AIN1_B8") (pintype "bidirectional"))
    )
    (net (code "236") (name "unconnected-(U1B-AIN2-PadB6)") (class "Default")
      (node (ref "U1") (pin "B6") (pinfunction "AIN2_B6") (pintype "bidirectional"))
    )
    (net (code "237") (name "unconnected-(U1B-AIN3-PadC6)") (class "Default")
      (node (ref "U1") (pin "C6") (pinfunction "AIN3_C6") (pintype "bidirectional"))
    )
    (net (code "238") (name "unconnected-(U1B-AIN4-PadC7)") (class "Default")
      (node (ref "U1") (pin "C7") (pinfunction "AIN4_C7") (pintype "bidirectional"))
    )
    (net (code "239") (name "unconnected-(U1B-AIN5-PadC8)") (class "Default")
      (node (ref "U1") (pin "C8") (pinfunction "AIN5_C8") (pintype "bidirectional"))
    )
    (net (code "240") (name "unconnected-(U1B-AIN6-PadC9)") (class "Default")
      (node (ref "U1") (pin "C9") (pinfunction "AIN6_C9") (pintype "bidirectional"))
    )
    (net (code "241") (name "unconnected-(U1B-EMU0-PadE2)") (class "Default")
      (node (ref "U1") (pin "E2") (pinfunction "EMU0_E2") (pintype "bidirectional"))
    )
    (net (code "242") (name "unconnected-(U1B-EMU1-PadE3)") (class "Default")
      (node (ref "U1") (pin "E3") (pinfunction "EMU1_E3") (pintype "bidirectional"))
    )
    (net (code "243") (name "unconnected-(U1B-TCK-PadD1)") (class "Default")
      (node (ref "U1") (pin "D1") (pinfunction "TCK_D1") (pintype "bidirectional"))
    )
    (net (code "244") (name "unconnected-(U1B-TDI-PadC1)") (class "Default")
      (node (ref "U1") (pin "C1") (pinfunction "TDI_C1") (pintype "bidirectional"))
    )
    (net (code "245") (name "unconnected-(U1B-TDO-PadC2)") (class "Default")
      (node (ref "U1") (pin "C2") (pinfunction "TDO_C2") (pintype "bidirectional"))
    )
    (net (code "246") (name "unconnected-(U1B-TMS-PadD2)") (class "Default")
      (node (ref "U1") (pin "D2") (pinfunction "TMS_D2") (pintype "bidirectional"))
    )
    (net (code "247") (name "unconnected-(U1B-TRSTN-PadD3)") (class "Default")
      (node (ref "U1") (pin "D3") (pinfunction "TRSTN_D3") (pintype "bidirectional"))
    )
    (net (code "248") (name "unconnected-(U1B-USB0_CE-PadK13)") (class "Default")
      (node (ref "U1") (pin "K13") (pinfunction "USB0_CE_K13") (pintype "bidirectional"))
    )
    (net (code "249") (name "unconnected-(U1B-USB0_DRVVBUS-PadJ15)") (class "Default")
      (node (ref "U1") (pin "J15") (pinfunction "USB0_DRVVBUS_J15") (pintype "bidirectional"))
    )
    (net (code "250") (name "unconnected-(U1B-USB1_CE-PadL13)") (class "Default")
      (node (ref "U1") (pin "L13") (pinfunction "USB1_CE_L13") (pintype "bidirectional"))
    )
    (net (code "251") (name "unconnected-(U1C-ECAP0_IN_PWM0_OUT-PadC5)") (class "Default")
      (node (ref "U1") (pin "C5") (pinfunction "ECAP0_IN_PWM0_OUT_C5") (pintype "bidirectional"))
    )
    (net (code "252") (name "unconnected-(U1C-GPMC_A0-PadT12)") (class "Default")
      (node (ref "U1") (pin "T12") (pinfunction "GPMC_A0_T12") (pintype "bidirectional"))
    )
    (net (code "253") (name "unconnected-(U1C-GPMC_A1-PadR12)") (class "Default")
      (node (ref "U1") (pin "R12") (pinfunction "GPMC_A1_R12") (pintype "bidirectional"))
    )
    (net (code "254") (name "unconnected-(U1C-GPMC_A2-PadP12)") (class "Default")
      (node (ref "U1") (pin "P12") (pinfunction "GPMC_A2_P12") (pintype "bidirectional"))
    )
    (net (code "255") (name "unconnected-(U1C-GPMC_A3-PadT13)") (class "Default")
      (node (ref "U1") (pin "T13") (pinfunction "GPMC_A3_T13") (pintype "bidirectional"))
    )
    (net (code "256") (name "unconnected-(U1C-GPMC_A4-PadR13)") (class "Default")
      (node (ref "U1") (pin "R13") (pinfunction "GPMC_A4_R13") (pintype "bidirectional"))
    )
    (net (code "257") (name "unconnected-(U1C-GPMC_A10-PadR15)") (class "Default")
      (node (ref "U1") (pin "R15") (pinfunction "GPMC_A10_R15") (pintype "bidirectional"))
    )
    (net (code "258") (name "unconnected-(U1C-GPMC_A11-PadT16)") (class "Default")
      (node (ref "U1") (pin "T16") (pinfunction "GPMC_A11_T16") (pintype "bidirectional"))
    )
    (net (code "259") (name "unconnected-(U1C-GPMC_AD0-PadR3)") (class "Default")
      (node (ref "U1") (pin "R3") (pinfunction "GPMC_AD0_R3") (pintype "bidirectional"))
    )
    (net (code "260") (name "unconnected-(U1C-GPMC_AD1-PadR2)") (class "Default")
      (node (ref "U1") (pin "R2") (pinfunction "GPMC_AD1_R2") (pintype "bidirectional"))
    )
    (net (code "261") (name "unconnected-(U1C-GPMC_AD2-PadR1)") (class "Default")
      (node (ref "U1") (pin "R1") (pinfunction "GPMC_AD2_R1") (pintype "bidirectional"))
    )
    (net (code "262") (name "unconnected-(U1C-GPMC_AD3-PadT3)") (class "Default")
      (node (ref "U1") (pin "T3") (pinfunction "GPMC_AD3_T3") (pintype "bidirectional"))
    )
    (net (code "263") (name "unconnected-(U1C-GPMC_AD4-PadT2)") (class "Default")
      (node (ref "U1") (pin "T2") (pinfunction "GPMC_AD4_T2") (pintype "bidirectional"))
    )
    (net (code "264") (name "unconnected-(U1C-GPMC_AD5-PadT1)") (class "Default")
      (node (ref "U1") (pin "T1") (pinfunction "GPMC_AD5_T1") (pintype "bidirectional"))
    )
    (net (code "265") (name "unconnected-(U1C-GPMC_AD6-PadP4)") (class "Default")
      (node (ref "U1") (pin "P4") (pinfunction "GPMC_AD6_P4") (pintype "bidirectional"))
    )
    (net (code "266") (name "unconnected-(U1C-GPMC_AD7-PadR4)") (class "Default")
      (node (ref "U1") (pin "R4") (pinfunction "GPMC_AD7_R4") (pintype "bidirectional"))
    )
    (net (code "267") (name "unconnected-(U1C-GPMC_ADVN_ALE-PadM1)") (class "Default")
      (node (ref "U1") (pin "M1") (pinfunction "GPMC_ADVN_ALE_M1") (pintype "bidirectional"))
    )
    (net (code "268") (name "unconnected-(U1C-GPMC_BEN1-PadN14)") (class "Default")
      (node (ref "U1") (pin "N14") (pinfunction "GPMC_BEN1_N14") (pintype "bidirectional"))
    )
    (net (code "269") (name "unconnected-(U1C-GPMC_CLK-PadT7)") (class "Default")
      (node (ref "U1") (pin "T7") (pinfunction "GPMC_CLK_T7") (pintype "bidirectional"))
    )
    (net (code "270") (name "unconnected-(U1C-GPMC_CSN0-PadP3)") (class "Default")
      (node (ref "U1") (pin "P3") (pinfunction "GPMC_CSN0_P3") (pintype "bidirectional"))
    )
    (net (code "271") (name "unconnected-(U1C-GPMC_CSN1-PadP2)") (class "Default")
      (node (ref "U1") (pin "P2") (pinfunction "GPMC_CSN1_P2") (pintype "bidirectional"))
    )
    (net (code "272") (name "unconnected-(U1C-GPMC_CSN2-PadP1)") (class "Default")
      (node (ref "U1") (pin "P1") (pinfunction "GPMC_CSN2_P1") (pintype "bidirectional"))
    )
    (net (code "273") (name "unconnected-(U1C-GPMC_CSN3-PadR7)") (class "Default")
      (node (ref "U1") (pin "R7") (pinfunction "GPMC_CSN3_R7") (pintype "bidirectional"))
    )
    (net (code "274") (name "unconnected-(U1C-GPMC_OEN_REN-PadN1)") (class "Default")
      (node (ref "U1") (pin "N1") (pinfunction "GPMC_OEN_REN_N1") (pintype "bidirectional"))
    )
    (net (code "275") (name "unconnected-(U1C-GPMC_WAIT0-PadP15)") (class "Default")
      (node (ref "U1") (pin "P15") (pinfunction "GPMC_WAIT0_P15") (pintype "bidirectional"))
    )
    (net (code "276") (name "unconnected-(U1C-GPMC_WEN-PadN2)") (class "Default")
      (node (ref "U1") (pin "N2") (pinfunction "GPMC_WEN_N2") (pintype "bidirectional"))
    )
    (net (code "277") (name "unconnected-(U1C-GPMC_WPN-PadR16)") (class "Default")
      (node (ref "U1") (pin "R16") (pinfunction "GPMC_WPN_R16") (pintype "bidirectional"))
    )
    (net (code "278") (name "unconnected-(U1C-MCASP0_ACLKR-PadA3)") (class "Default")
      (node (ref "U1") (pin "A3") (pinfunction "MCASP0_ACLKR_A3") (pintype "bidirectional"))
    )
    (net (code "279") (name "unconnected-(U1C-MCASP0_AHCLKX-PadC4)") (class "Default")
      (node (ref "U1") (pin "C4") (pinfunction "MCASP0_AHCLKX_C4") (pintype "bidirectional"))
    )
    (net (code "280") (name "unconnected-(U1C-MCASP0_AXR1-PadC3)") (class "Default")
      (node (ref "U1") (pin "C3") (pinfunction "MCASP0_AXR1_C3") (pintype "bidirectional"))
    )
    (net (code "281") (name "unconnected-(U1C-MCASP0_FSR-PadB3)") (class "Default")
      (node (ref "U1") (pin "B3") (pinfunction "MCASP0_FSR_B3") (pintype "bidirectional"))
    )
    (net (code "282") (name "unconnected-(U1C-SPI0_CS0-PadA14)") (class "Default")
      (node (ref "U1") (pin "A14") (pinfunction "SPI0_CS0_A14") (pintype "bidirectional"))
    )
    (net (code "283") (name "unconnected-(U1C-SPI0_D0-PadB13)") (class "Default")
      (node (ref "U1") (pin "B13") (pinfunction "SPI0_D0_B13") (pintype "bidirectional"))
    )
    (net (code "284") (name "unconnected-(U1C-SPI0_D1-PadB14)") (class "Default")
      (node (ref "U1") (pin "B14") (pinfunction "SPI0_D1_B14") (pintype "bidirectional"))
    )
    (net (code "285") (name "unconnected-(U1C-SPI0_SCLK-PadA13)") (class "Default")
      (node (ref "U1") (pin "A13") (pinfunction "SPI0_SCLK_A13") (pintype "bidirectional"))
    )
    (net (code "286") (name "unconnected-(U1C-UART0_CTSN-PadC12)") (class "Default")
      (node (ref "U1") (pin "C12") (pinfunction "UART0_CTSN_C12") (pintype "bidirectional"))
    )
    (net (code "287") (name "unconnected-(U1C-UART0_RTSN-PadC13)") (class "Default")
      (node (ref "U1") (pin "C13") (pinfunction "UART0_RTSN_C13") (pintype "bidirectional"))
    )
    (net (code "288") (name "unconnected-(U1C-UART1_RXD-PadA11)") (class "Default")
      (node (ref "U1") (pin "A11") (pinfunction "UART1_RXD_A11") (pintype "bidirectional"))
    )
    (net (code "289") (name "unconnected-(U1C-UART1_TXD-PadB11)") (class "Default")
      (node (ref "U1") (pin "B11") (pinfunction "UART1_TXD_B11") (pintype "bidirectional"))
    )
    (net (code "290") (name "unconnected-(U1C-XDMA_EVENT_INTR0-PadA4)") (class "Default")
      (node (ref "U1") (pin "A4") (pinfunction "XDMA_EVENT_INTR0_A4") (pintype "bidirectional"))
    )
    (net (code "291") (name "unconnected-(U1D-MII1_RXD0-PadE14)") (class "Default")
      (node (ref "U1") (pin "E14") (pinfunction "MII1_RXD0_E14") (pintype "bidirectional"))
    )
    (net (code "292") (name "unconnected-(U1D-MII1_RX_CLK-PadE16)") (class "Default")
      (node (ref "U1") (pin "E16") (pinfunction "MII1_RX_CLK_E16") (pintype "bidirectional"))
    )
    (net (code "293") (name "unconnected-(U1D-MII1_RX_ER-PadE15)") (class "Default")
      (node (ref "U1") (pin "E15") (pinfunction "MII1_RX_ER_E15") (pintype "bidirectional"))
    )
    (net (code "294") (name "unconnected-(U1D-RMII1_REF_CLK-PadJ14)") (class "Default")
      (node (ref "U1") (pin "J14") (pinfunction "RMII1_REF_CLK_J14") (pintype "bidirectional"))
    )
    (net (code "295") (name "unconnected-(U1F-CAP_VDD_RTC-PadD5)") (class "Default")
      (node (ref "U1") (pin "D5") (pinfunction "CAP_VDD_RTC_D5") (pintype "bidirectional"))
    )
    (net (code "296") (name "unconnected-(U1F-NC-PadD12)") (class "Default")
      (node (ref "U1") (pin "D12") (pinfunction "NC_D12") (pintype "bidirectional"))
    )
    (net (code "297") (name "unconnected-(U1F-NC-PadJ6)") (class "Default")
      (node (ref "U1") (pin "J6") (pinfunction "NC_J6") (pintype "bidirectional"))
    )
    (net (code "298") (name "unconnected-(U1F-NC-PadK4)") (class "Default")
      (node (ref "U1") (pin "K4") (pinfunction "NC_K4") (pintype "bidirectional"))
    )
    (net (code "299") (name "unconnected-(U1F-VPP-PadH6)") (class "Default")
      (node (ref "U1") (pin "H6") (pinfunction "VPP_H6") (pintype "bidirectional"))
    )
    (net (code "300") (name "unconnected-(U2-NC-Pad1)") (class "Default")
      (node (ref "U2") (pin "1") (pinfunction "NC_1") (pintype "bidirectional"))
    )
    (net (code "301") (name "unconnected-(U4-GPIO4-Pad25)") (class "Default")
      (node (ref "U4") (pin "25") (pinfunction "GPIO4_25") (pintype "bidirectional"))
    )
    (net (code "302") (name "unconnected-(U4-GPIO9-Pad3)") (class "Default")
      (node (ref "U4") (pin "3") (pinfunction "GPIO9_3") (pintype "bidirectional"))
    )
    (net (code "303") (name "unconnected-(U4-GPIO10-Pad4)") (class "Default")
      (node (ref "U4") (pin "4") (pinfunction "GPIO10_4") (pintype "bidirectional"))
    )
    (net (code "304") (name "unconnected-(U4-GPIO11-Pad2)") (class "Default")
      (node (ref "U4") (pin "2") (pinfunction "GPIO11_2") (pintype "bidirectional"))
    )
    (net (code "305") (name "unconnected-(U4-GPIO12-Pad5)") (class "Default")
      (node (ref "U4") (pin "5") (pinfunction "GPIO12_5") (pintype "bidirectional"))
    )
    (net (code "306") (name "unconnected-(U4-RESERVED1-Pad21)") (class "Default")
      (node (ref "U4") (pin "21") (pinfunction "RESERVED1_21") (pintype "bidirectional"))
    )
    (net (code "307") (name "unconnected-(U4-RESERVED2-Pad22)") (class "Default")
      (node (ref "U4") (pin "22") (pinfunction "RESERVED2_22") (pintype "bidirectional"))
    )
    (net (code "308") (name "unconnected-(U4-RESERVED3-Pad62)") (class "Default")
      (node (ref "U4") (pin "62") (pinfunction "RESERVED3_62") (pintype "bidirectional"))
    )
    (net (code "309") (name "unconnected-(U11-I2S1-Pad4)") (class "Default")
      (node (ref "U11") (pin "4") (pinfunction "I2S1_4") (pintype "bidirectional"))
    )
    (net (code "310") (name "unconnected-(U11-I2S2-Pad3)") (class "Default")
      (node (ref "U11") (pin "3") (pinfunction "I2S2_3") (pintype "bidirectional"))
    )
    (net (code "311") (name "unconnected-(U12-NC-Pad7)") (class "Default")
      (node (ref "U12") (pin "7") (pinfunction "NC_7") (pintype "no_connect"))
    )
    (net (code "312") (name "unconnected-(U12-NC-Pad20)") (class "Default")
      (node (ref "U12") (pin "20") (pinfunction "NC_20") (pintype "no_connect"))
    )
    (net (code "313") (name "unconnected-(U12-NC-Pad25)") (class "Default")
      (node (ref "U12") (pin "25") (pinfunction "NC_25") (pintype "no_connect"))
    )
  )
)
